# Main_DIY_board.net
KiCad netlist of a schematic drawn in EAGLE
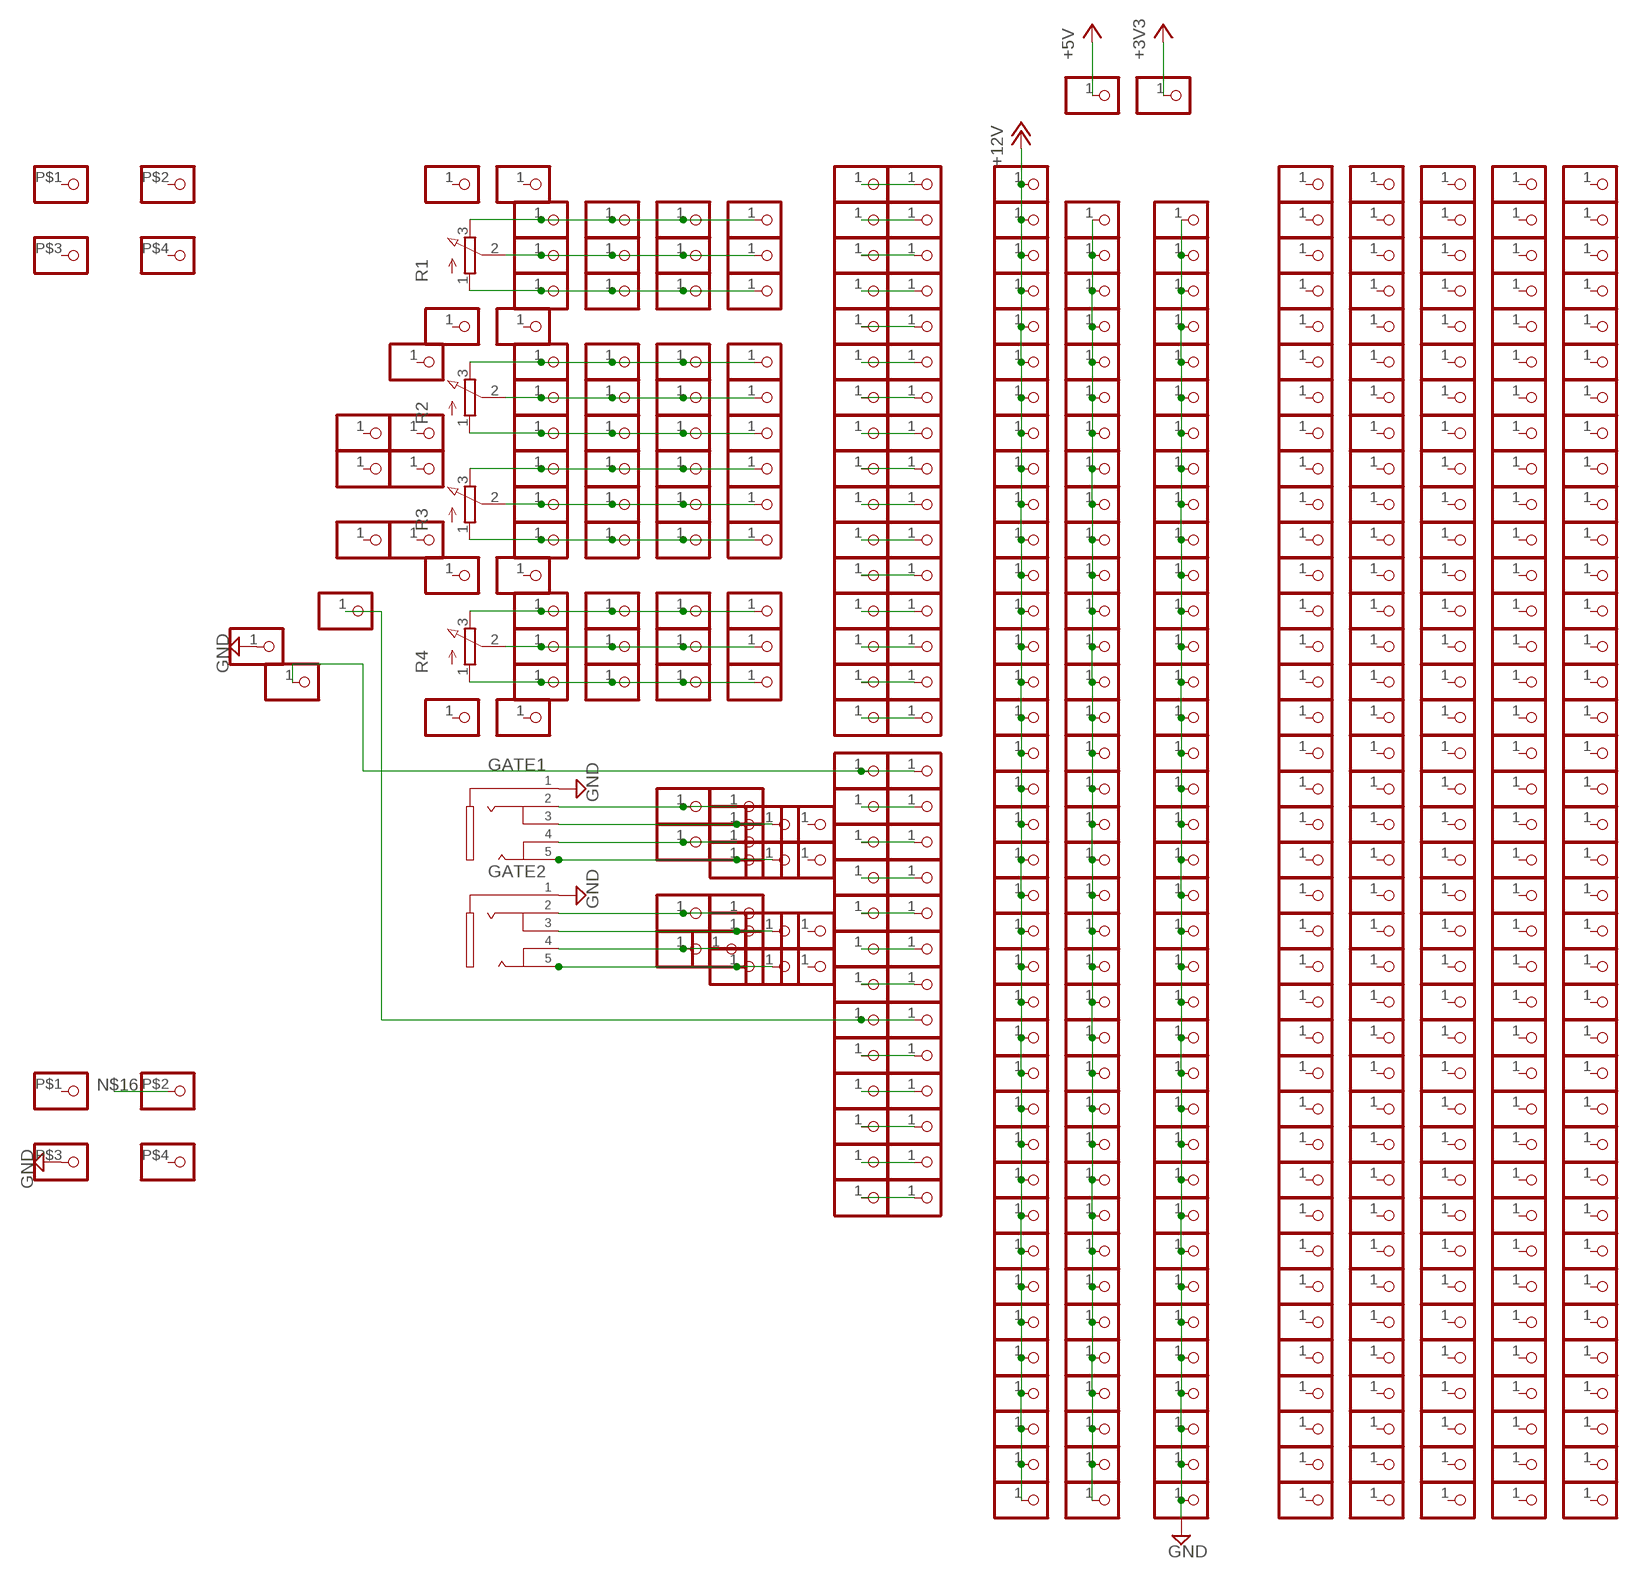
[diagram p0: schematic, sheet 1, part 1 of 2]
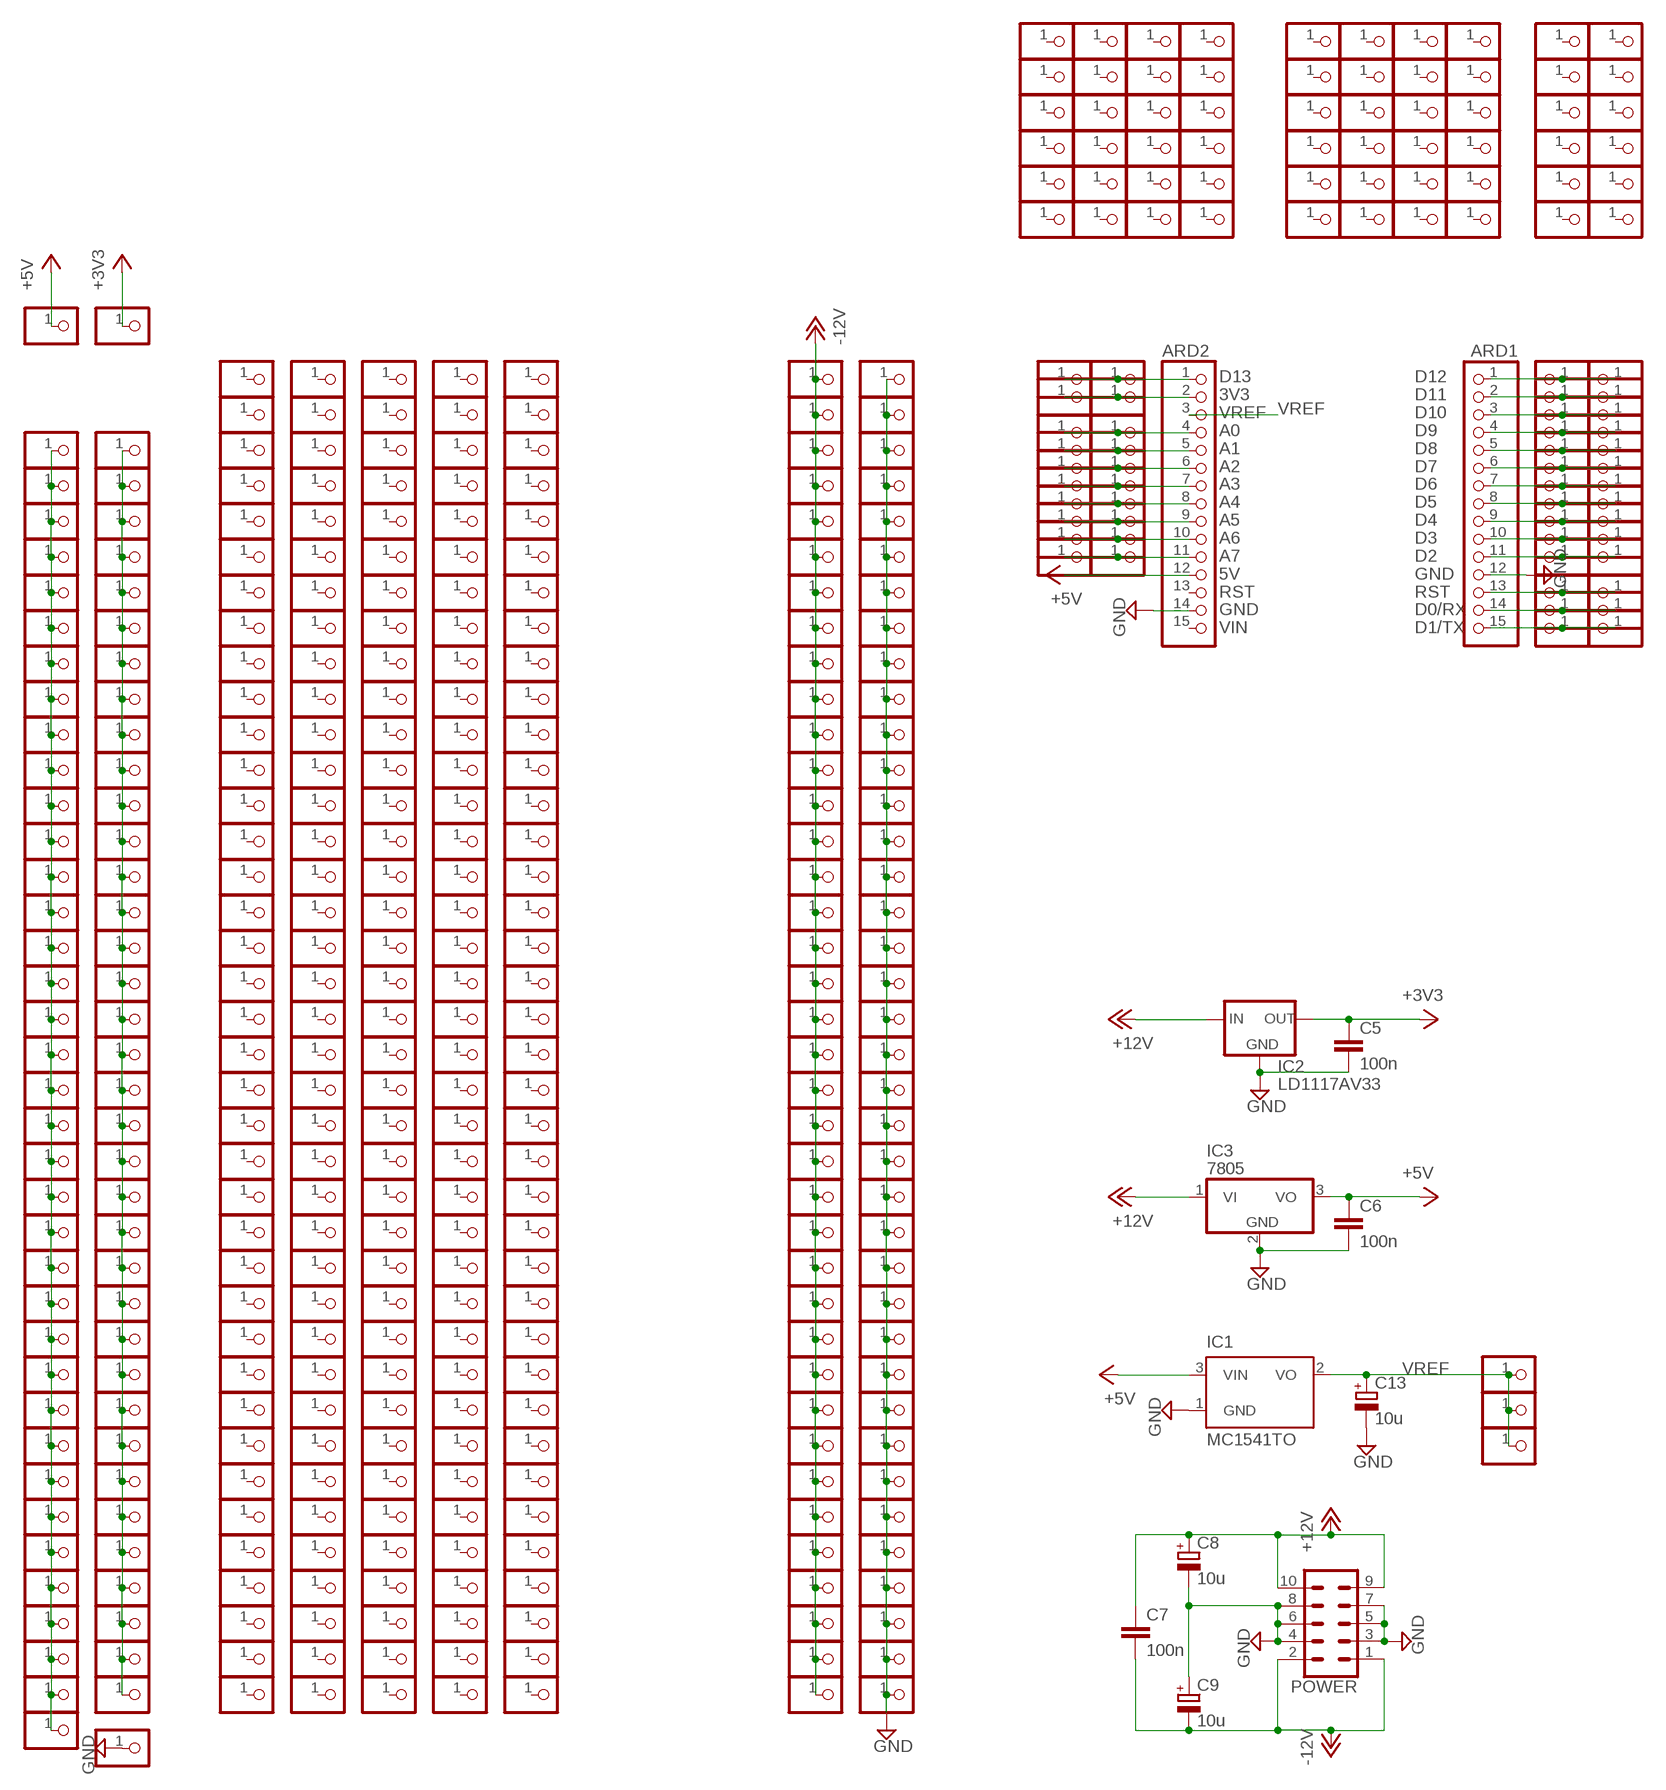
[diagram p1: schematic, sheet 1, part 2 of 2]

(export (version "E")
  (design (tool "Eeschema 10.0.6"))
  (components
    (comp (ref "ARD1")
      (value "PINHD-1X15")
      (footprint "eagle-import:1X15")
      (libsource (lib "eagle-import") (part "PINHD-1X15"))
    )
    (comp (ref "ARD2")
      (value "PINHD-1X15")
      (footprint "eagle-import:1X15")
      (libsource (lib "eagle-import") (part "PINHD-1X15"))
    )
    (comp (ref "C5")
      (value "100n")
      (footprint "eagle-import:C050-025X075")
      (libsource (lib "eagle-import") (part "C-EU050-025X075"))
    )
    (comp (ref "C6")
      (value "100n")
      (footprint "eagle-import:C050-025X075")
      (libsource (lib "eagle-import") (part "C-EU050-025X075"))
    )
    (comp (ref "C7")
      (value "100n")
      (footprint "eagle-import:C050-025X075")
      (libsource (lib "eagle-import") (part "C-EU050-025X075"))
    )
    (comp (ref "C8")
      (value "10u")
      (footprint "eagle-import:E2,5-5")
      (libsource (lib "eagle-import") (part "CPOL"))
    )
    (comp (ref "C9")
      (value "10u")
      (footprint "eagle-import:E2,5-5")
      (libsource (lib "eagle-import") (part "CPOL"))
    )
    (comp (ref "C13")
      (value "10u")
      (footprint "eagle-import:E2,5-5")
      (libsource (lib "eagle-import") (part "CPOL"))
    )
    (comp (ref "GATE1")
      (value "PJ-324MH")
      (footprint "eagle-import:PJ-324MH")
      (libsource (lib "eagle-import") (part "PJ-324MH"))
    )
    (comp (ref "GATE2")
      (value "PJ-324MH")
      (footprint "eagle-import:PJ-324MH")
      (libsource (lib "eagle-import") (part "PJ-324MH"))
    )
    (comp (ref "IC1")
      (value "MC1541TO")
      (footprint "eagle-import:TO92")
      (libsource (lib "eagle-import") (part "MC15TO41"))
    )
    (comp (ref "IC2")
      (value "LD1117AV33")
      (footprint "eagle-import:78XXL")
      (libsource (lib "eagle-import") (part "V_REG_LD1117VXX"))
    )
    (comp (ref "IC3")
      (value "7805")
      (footprint "eagle-import:TO220H")
      (libsource (lib "eagle-import") (part "78T05"))
    )
    (comp (ref "JP1")
      (value "1X01")
      (footprint "eagle-import:1X01")
      (libsource (lib "eagle-import") (part "1X01"))
    )
    (comp (ref "JP2")
      (value "1X01")
      (footprint "eagle-import:1X01")
      (libsource (lib "eagle-import") (part "1X01"))
    )
    (comp (ref "JP3")
      (value "1X01")
      (footprint "eagle-import:1X01")
      (libsource (lib "eagle-import") (part "1X01"))
    )
    (comp (ref "JP4")
      (value "1X01")
      (footprint "eagle-import:1X01")
      (libsource (lib "eagle-import") (part "1X01"))
    )
    (comp (ref "JP5")
      (value "1X01")
      (footprint "eagle-import:1X01")
      (libsource (lib "eagle-import") (part "1X01"))
    )
    (comp (ref "JP6")
      (value "1X01")
      (footprint "eagle-import:1X01")
      (libsource (lib "eagle-import") (part "1X01"))
    )
    (comp (ref "JP7")
      (value "1X01")
      (footprint "eagle-import:1X01")
      (libsource (lib "eagle-import") (part "1X01"))
    )
    (comp (ref "JP8")
      (value "1X01")
      (footprint "eagle-import:1X01")
      (libsource (lib "eagle-import") (part "1X01"))
    )
    (comp (ref "JP9")
      (value "1X01")
      (footprint "eagle-import:1X01")
      (libsource (lib "eagle-import") (part "1X01"))
    )
    (comp (ref "JP10")
      (value "1X01")
      (footprint "eagle-import:1X01")
      (libsource (lib "eagle-import") (part "1X01"))
    )
    (comp (ref "JP11")
      (value "1X01")
      (footprint "eagle-import:1X01")
      (libsource (lib "eagle-import") (part "1X01"))
    )
    (comp (ref "JP12")
      (value "1X01")
      (footprint "eagle-import:1X01")
      (libsource (lib "eagle-import") (part "1X01"))
    )
    (comp (ref "JP13")
      (value "1X01")
      (footprint "eagle-import:1X01")
      (libsource (lib "eagle-import") (part "1X01"))
    )
    (comp (ref "JP14")
      (value "1X01")
      (footprint "eagle-import:1X01")
      (libsource (lib "eagle-import") (part "1X01"))
    )
    (comp (ref "JP15")
      (value "1X01")
      (footprint "eagle-import:1X01")
      (libsource (lib "eagle-import") (part "1X01"))
    )
    (comp (ref "JP16")
      (value "1X01")
      (footprint "eagle-import:1X01")
      (libsource (lib "eagle-import") (part "1X01"))
    )
    (comp (ref "JP17")
      (value "1X01")
      (footprint "eagle-import:1X01")
      (libsource (lib "eagle-import") (part "1X01"))
    )
    (comp (ref "JP18")
      (value "1X01")
      (footprint "eagle-import:1X01")
      (libsource (lib "eagle-import") (part "1X01"))
    )
    (comp (ref "JP19")
      (value "1X01")
      (footprint "eagle-import:1X01")
      (libsource (lib "eagle-import") (part "1X01"))
    )
    (comp (ref "JP20")
      (value "1X01")
      (footprint "eagle-import:1X01")
      (libsource (lib "eagle-import") (part "1X01"))
    )
    (comp (ref "JP21")
      (value "1X01")
      (footprint "eagle-import:1X01")
      (libsource (lib "eagle-import") (part "1X01"))
    )
    (comp (ref "JP22")
      (value "1X01")
      (footprint "eagle-import:1X01")
      (libsource (lib "eagle-import") (part "1X01"))
    )
    (comp (ref "JP23")
      (value "1X01")
      (footprint "eagle-import:1X01")
      (libsource (lib "eagle-import") (part "1X01"))
    )
    (comp (ref "JP24")
      (value "1X01")
      (footprint "eagle-import:1X01")
      (libsource (lib "eagle-import") (part "1X01"))
    )
    (comp (ref "JP25")
      (value "1X01")
      (footprint "eagle-import:1X01")
      (libsource (lib "eagle-import") (part "1X01"))
    )
    (comp (ref "JP26")
      (value "1X01")
      (footprint "eagle-import:1X01")
      (libsource (lib "eagle-import") (part "1X01"))
    )
    (comp (ref "JP27")
      (value "1X01")
      (footprint "eagle-import:1X01")
      (libsource (lib "eagle-import") (part "1X01"))
    )
    (comp (ref "JP28")
      (value "1X01")
      (footprint "eagle-import:1X01")
      (libsource (lib "eagle-import") (part "1X01"))
    )
    (comp (ref "JP29")
      (value "1X01")
      (footprint "eagle-import:1X01")
      (libsource (lib "eagle-import") (part "1X01"))
    )
    (comp (ref "JP30")
      (value "1X01")
      (footprint "eagle-import:1X01")
      (libsource (lib "eagle-import") (part "1X01"))
    )
    (comp (ref "JP31")
      (value "1X01")
      (footprint "eagle-import:1X01")
      (libsource (lib "eagle-import") (part "1X01"))
    )
    (comp (ref "JP32")
      (value "1X01")
      (footprint "eagle-import:1X01")
      (libsource (lib "eagle-import") (part "1X01"))
    )
    (comp (ref "JP33")
      (value "1X01")
      (footprint "eagle-import:1X01")
      (libsource (lib "eagle-import") (part "1X01"))
    )
    (comp (ref "JP34")
      (value "1X01")
      (footprint "eagle-import:1X01")
      (libsource (lib "eagle-import") (part "1X01"))
    )
    (comp (ref "JP35")
      (value "1X01")
      (footprint "eagle-import:1X01")
      (libsource (lib "eagle-import") (part "1X01"))
    )
    (comp (ref "JP36")
      (value "1X01")
      (footprint "eagle-import:1X01")
      (libsource (lib "eagle-import") (part "1X01"))
    )
    (comp (ref "JP37")
      (value "1X01")
      (footprint "eagle-import:1X01")
      (libsource (lib "eagle-import") (part "1X01"))
    )
    (comp (ref "JP38")
      (value "1X01")
      (footprint "eagle-import:1X01")
      (libsource (lib "eagle-import") (part "1X01"))
    )
    (comp (ref "JP39")
      (value "1X01")
      (footprint "eagle-import:1X01")
      (libsource (lib "eagle-import") (part "1X01"))
    )
    (comp (ref "JP40")
      (value "1X01")
      (footprint "eagle-import:1X01")
      (libsource (lib "eagle-import") (part "1X01"))
    )
    (comp (ref "JP41")
      (value "1X01")
      (footprint "eagle-import:1X01")
      (libsource (lib "eagle-import") (part "1X01"))
    )
    (comp (ref "JP42")
      (value "1X01")
      (footprint "eagle-import:1X01")
      (libsource (lib "eagle-import") (part "1X01"))
    )
    (comp (ref "JP43")
      (value "1X01")
      (footprint "eagle-import:1X01")
      (libsource (lib "eagle-import") (part "1X01"))
    )
    (comp (ref "JP44")
      (value "1X01")
      (footprint "eagle-import:1X01")
      (libsource (lib "eagle-import") (part "1X01"))
    )
    (comp (ref "JP45")
      (value "1X01")
      (footprint "eagle-import:1X01")
      (libsource (lib "eagle-import") (part "1X01"))
    )
    (comp (ref "JP46")
      (value "1X01")
      (footprint "eagle-import:1X01")
      (libsource (lib "eagle-import") (part "1X01"))
    )
    (comp (ref "JP47")
      (value "1X01")
      (footprint "eagle-import:1X01")
      (libsource (lib "eagle-import") (part "1X01"))
    )
    (comp (ref "JP48")
      (value "1X01")
      (footprint "eagle-import:1X01")
      (libsource (lib "eagle-import") (part "1X01"))
    )
    (comp (ref "JP49")
      (value "1X01")
      (footprint "eagle-import:1X01")
      (libsource (lib "eagle-import") (part "1X01"))
    )
    (comp (ref "JP50")
      (value "1X01")
      (footprint "eagle-import:1X01")
      (libsource (lib "eagle-import") (part "1X01"))
    )
    (comp (ref "JP51")
      (value "1X01")
      (footprint "eagle-import:1X01")
      (libsource (lib "eagle-import") (part "1X01"))
    )
    (comp (ref "JP52")
      (value "1X01")
      (footprint "eagle-import:1X01")
      (libsource (lib "eagle-import") (part "1X01"))
    )
    (comp (ref "JP53")
      (value "1X01")
      (footprint "eagle-import:1X01")
      (libsource (lib "eagle-import") (part "1X01"))
    )
    (comp (ref "JP54")
      (value "1X01")
      (footprint "eagle-import:1X01")
      (libsource (lib "eagle-import") (part "1X01"))
    )
    (comp (ref "JP55")
      (value "1X01")
      (footprint "eagle-import:1X01")
      (libsource (lib "eagle-import") (part "1X01"))
    )
    (comp (ref "JP56")
      (value "1X01")
      (footprint "eagle-import:1X01")
      (libsource (lib "eagle-import") (part "1X01"))
    )
    (comp (ref "JP57")
      (value "1X01")
      (footprint "eagle-import:1X01")
      (libsource (lib "eagle-import") (part "1X01"))
    )
    (comp (ref "JP58")
      (value "1X01")
      (footprint "eagle-import:1X01")
      (libsource (lib "eagle-import") (part "1X01"))
    )
    (comp (ref "JP59")
      (value "1X01")
      (footprint "eagle-import:1X01")
      (libsource (lib "eagle-import") (part "1X01"))
    )
    (comp (ref "JP60")
      (value "1X01")
      (footprint "eagle-import:1X01")
      (libsource (lib "eagle-import") (part "1X01"))
    )
    (comp (ref "JP61")
      (value "1X01")
      (footprint "eagle-import:1X01")
      (libsource (lib "eagle-import") (part "1X01"))
    )
    (comp (ref "JP62")
      (value "1X01")
      (footprint "eagle-import:1X01")
      (libsource (lib "eagle-import") (part "1X01"))
    )
    (comp (ref "JP63")
      (value "1X01")
      (footprint "eagle-import:1X01")
      (libsource (lib "eagle-import") (part "1X01"))
    )
    (comp (ref "JP64")
      (value "1X01")
      (footprint "eagle-import:1X01")
      (libsource (lib "eagle-import") (part "1X01"))
    )
    (comp (ref "JP65")
      (value "1X01")
      (footprint "eagle-import:1X01")
      (libsource (lib "eagle-import") (part "1X01"))
    )
    (comp (ref "JP66")
      (value "1X01")
      (footprint "eagle-import:1X01")
      (libsource (lib "eagle-import") (part "1X01"))
    )
    (comp (ref "JP67")
      (value "1X01")
      (footprint "eagle-import:1X01")
      (libsource (lib "eagle-import") (part "1X01"))
    )
    (comp (ref "JP68")
      (value "1X01")
      (footprint "eagle-import:1X01")
      (libsource (lib "eagle-import") (part "1X01"))
    )
    (comp (ref "JP69")
      (value "1X01")
      (footprint "eagle-import:1X01")
      (libsource (lib "eagle-import") (part "1X01"))
    )
    (comp (ref "JP70")
      (value "1X01")
      (footprint "eagle-import:1X01")
      (libsource (lib "eagle-import") (part "1X01"))
    )
    (comp (ref "JP71")
      (value "1X01")
      (footprint "eagle-import:1X01")
      (libsource (lib "eagle-import") (part "1X01"))
    )
    (comp (ref "JP72")
      (value "1X01")
      (footprint "eagle-import:1X01")
      (libsource (lib "eagle-import") (part "1X01"))
    )
    (comp (ref "JP73")
      (value "1X01")
      (footprint "eagle-import:1X01")
      (libsource (lib "eagle-import") (part "1X01"))
    )
    (comp (ref "JP74")
      (value "1X01")
      (footprint "eagle-import:1X01")
      (libsource (lib "eagle-import") (part "1X01"))
    )
    (comp (ref "JP75")
      (value "1X01")
      (footprint "eagle-import:1X01")
      (libsource (lib "eagle-import") (part "1X01"))
    )
    (comp (ref "JP76")
      (value "1X01")
      (footprint "eagle-import:1X01")
      (libsource (lib "eagle-import") (part "1X01"))
    )
    (comp (ref "JP77")
      (value "1X01")
      (footprint "eagle-import:1X01")
      (libsource (lib "eagle-import") (part "1X01"))
    )
    (comp (ref "JP78")
      (value "1X01")
      (footprint "eagle-import:1X01")
      (libsource (lib "eagle-import") (part "1X01"))
    )
    (comp (ref "JP79")
      (value "1X01")
      (footprint "eagle-import:1X01")
      (libsource (lib "eagle-import") (part "1X01"))
    )
    (comp (ref "JP80")
      (value "1X01")
      (footprint "eagle-import:1X01")
      (libsource (lib "eagle-import") (part "1X01"))
    )
    (comp (ref "JP81")
      (value "1X01")
      (footprint "eagle-import:1X01")
      (libsource (lib "eagle-import") (part "1X01"))
    )
    (comp (ref "JP82")
      (value "1X01")
      (footprint "eagle-import:1X01")
      (libsource (lib "eagle-import") (part "1X01"))
    )
    (comp (ref "JP83")
      (value "1X01")
      (footprint "eagle-import:1X01")
      (libsource (lib "eagle-import") (part "1X01"))
    )
    (comp (ref "JP84")
      (value "1X01")
      (footprint "eagle-import:1X01")
      (libsource (lib "eagle-import") (part "1X01"))
    )
    (comp (ref "JP85")
      (value "1X01")
      (footprint "eagle-import:1X01")
      (libsource (lib "eagle-import") (part "1X01"))
    )
    (comp (ref "JP86")
      (value "1X01")
      (footprint "eagle-import:1X01")
      (libsource (lib "eagle-import") (part "1X01"))
    )
    (comp (ref "JP87")
      (value "1X01")
      (footprint "eagle-import:1X01")
      (libsource (lib "eagle-import") (part "1X01"))
    )
    (comp (ref "JP88")
      (value "1X01")
      (footprint "eagle-import:1X01")
      (libsource (lib "eagle-import") (part "1X01"))
    )
    (comp (ref "JP89")
      (value "1X01")
      (footprint "eagle-import:1X01")
      (libsource (lib "eagle-import") (part "1X01"))
    )
    (comp (ref "JP90")
      (value "1X01")
      (footprint "eagle-import:1X01")
      (libsource (lib "eagle-import") (part "1X01"))
    )
    (comp (ref "JP91")
      (value "1X01")
      (footprint "eagle-import:1X01")
      (libsource (lib "eagle-import") (part "1X01"))
    )
    (comp (ref "JP92")
      (value "1X01")
      (footprint "eagle-import:1X01")
      (libsource (lib "eagle-import") (part "1X01"))
    )
    (comp (ref "JP93")
      (value "1X01")
      (footprint "eagle-import:1X01")
      (libsource (lib "eagle-import") (part "1X01"))
    )
    (comp (ref "JP94")
      (value "1X01")
      (footprint "eagle-import:1X01")
      (libsource (lib "eagle-import") (part "1X01"))
    )
    (comp (ref "JP95")
      (value "1X01")
      (footprint "eagle-import:1X01")
      (libsource (lib "eagle-import") (part "1X01"))
    )
    (comp (ref "JP96")
      (value "1X01")
      (footprint "eagle-import:1X01")
      (libsource (lib "eagle-import") (part "1X01"))
    )
    (comp (ref "JP97")
      (value "1X01")
      (footprint "eagle-import:1X01")
      (libsource (lib "eagle-import") (part "1X01"))
    )
    (comp (ref "JP98")
      (value "1X01")
      (footprint "eagle-import:1X01")
      (libsource (lib "eagle-import") (part "1X01"))
    )
    (comp (ref "JP99")
      (value "1X01")
      (footprint "eagle-import:1X01")
      (libsource (lib "eagle-import") (part "1X01"))
    )
    (comp (ref "JP100")
      (value "1X01")
      (footprint "eagle-import:1X01")
      (libsource (lib "eagle-import") (part "1X01"))
    )
    (comp (ref "JP101")
      (value "1X01")
      (footprint "eagle-import:1X01")
      (libsource (lib "eagle-import") (part "1X01"))
    )
    (comp (ref "JP102")
      (value "1X01")
      (footprint "eagle-import:1X01")
      (libsource (lib "eagle-import") (part "1X01"))
    )
    (comp (ref "JP103")
      (value "1X01")
      (footprint "eagle-import:1X01")
      (libsource (lib "eagle-import") (part "1X01"))
    )
    (comp (ref "JP104")
      (value "1X01")
      (footprint "eagle-import:1X01")
      (libsource (lib "eagle-import") (part "1X01"))
    )
    (comp (ref "JP105")
      (value "1X01")
      (footprint "eagle-import:1X01")
      (libsource (lib "eagle-import") (part "1X01"))
    )
    (comp (ref "JP106")
      (value "1X01")
      (footprint "eagle-import:1X01")
      (libsource (lib "eagle-import") (part "1X01"))
    )
    (comp (ref "JP107")
      (value "1X01")
      (footprint "eagle-import:1X01")
      (libsource (lib "eagle-import") (part "1X01"))
    )
    (comp (ref "JP108")
      (value "1X01")
      (footprint "eagle-import:1X01")
      (libsource (lib "eagle-import") (part "1X01"))
    )
    (comp (ref "JP109")
      (value "1X01")
      (footprint "eagle-import:1X01")
      (libsource (lib "eagle-import") (part "1X01"))
    )
    (comp (ref "JP110")
      (value "1X01")
      (footprint "eagle-import:1X01")
      (libsource (lib "eagle-import") (part "1X01"))
    )
    (comp (ref "JP111")
      (value "1X01")
      (footprint "eagle-import:1X01")
      (libsource (lib "eagle-import") (part "1X01"))
    )
    (comp (ref "JP112")
      (value "1X01")
      (footprint "eagle-import:1X01")
      (libsource (lib "eagle-import") (part "1X01"))
    )
    (comp (ref "JP113")
      (value "1X01")
      (footprint "eagle-import:1X01")
      (libsource (lib "eagle-import") (part "1X01"))
    )
    (comp (ref "JP114")
      (value "1X01")
      (footprint "eagle-import:1X01")
      (libsource (lib "eagle-import") (part "1X01"))
    )
    (comp (ref "JP115")
      (value "1X01")
      (footprint "eagle-import:1X01")
      (libsource (lib "eagle-import") (part "1X01"))
    )
    (comp (ref "JP116")
      (value "1X01")
      (footprint "eagle-import:1X01")
      (libsource (lib "eagle-import") (part "1X01"))
    )
    (comp (ref "JP117")
      (value "1X01")
      (footprint "eagle-import:1X01")
      (libsource (lib "eagle-import") (part "1X01"))
    )
    (comp (ref "JP118")
      (value "1X01")
      (footprint "eagle-import:1X01")
      (libsource (lib "eagle-import") (part "1X01"))
    )
    (comp (ref "JP119")
      (value "1X01")
      (footprint "eagle-import:1X01")
      (libsource (lib "eagle-import") (part "1X01"))
    )
    (comp (ref "JP120")
      (value "1X01")
      (footprint "eagle-import:1X01")
      (libsource (lib "eagle-import") (part "1X01"))
    )
    (comp (ref "JP121")
      (value "1X01")
      (footprint "eagle-import:1X01")
      (libsource (lib "eagle-import") (part "1X01"))
    )
    (comp (ref "JP122")
      (value "1X01")
      (footprint "eagle-import:1X01")
      (libsource (lib "eagle-import") (part "1X01"))
    )
    (comp (ref "JP123")
      (value "1X01")
      (footprint "eagle-import:1X01")
      (libsource (lib "eagle-import") (part "1X01"))
    )
    (comp (ref "JP124")
      (value "1X01")
      (footprint "eagle-import:1X01")
      (libsource (lib "eagle-import") (part "1X01"))
    )
    (comp (ref "JP125")
      (value "1X01")
      (footprint "eagle-import:1X01")
      (libsource (lib "eagle-import") (part "1X01"))
    )
    (comp (ref "JP126")
      (value "1X01")
      (footprint "eagle-import:1X01")
      (libsource (lib "eagle-import") (part "1X01"))
    )
    (comp (ref "JP127")
      (value "1X01")
      (footprint "eagle-import:1X01")
      (libsource (lib "eagle-import") (part "1X01"))
    )
    (comp (ref "JP128")
      (value "1X01")
      (footprint "eagle-import:1X01")
      (libsource (lib "eagle-import") (part "1X01"))
    )
    (comp (ref "JP129")
      (value "1X01")
      (footprint "eagle-import:1X01")
      (libsource (lib "eagle-import") (part "1X01"))
    )
    (comp (ref "JP130")
      (value "1X01")
      (footprint "eagle-import:1X01")
      (libsource (lib "eagle-import") (part "1X01"))
    )
    (comp (ref "JP131")
      (value "1X01")
      (footprint "eagle-import:1X01")
      (libsource (lib "eagle-import") (part "1X01"))
    )
    (comp (ref "JP132")
      (value "1X01")
      (footprint "eagle-import:1X01")
      (libsource (lib "eagle-import") (part "1X01"))
    )
    (comp (ref "JP133")
      (value "1X01")
      (footprint "eagle-import:1X01")
      (libsource (lib "eagle-import") (part "1X01"))
    )
    (comp (ref "JP134")
      (value "1X01")
      (footprint "eagle-import:1X01")
      (libsource (lib "eagle-import") (part "1X01"))
    )
    (comp (ref "JP135")
      (value "1X01")
      (footprint "eagle-import:1X01")
      (libsource (lib "eagle-import") (part "1X01"))
    )
    (comp (ref "JP136")
      (value "1X01")
      (footprint "eagle-import:1X01")
      (libsource (lib "eagle-import") (part "1X01"))
    )
    (comp (ref "JP137")
      (value "1X01")
      (footprint "eagle-import:1X01")
      (libsource (lib "eagle-import") (part "1X01"))
    )
    (comp (ref "JP138")
      (value "1X01")
      (footprint "eagle-import:1X01")
      (libsource (lib "eagle-import") (part "1X01"))
    )
    (comp (ref "JP139")
      (value "1X01")
      (footprint "eagle-import:1X01")
      (libsource (lib "eagle-import") (part "1X01"))
    )
    (comp (ref "JP140")
      (value "1X01")
      (footprint "eagle-import:1X01")
      (libsource (lib "eagle-import") (part "1X01"))
    )
    (comp (ref "JP141")
      (value "1X01")
      (footprint "eagle-import:1X01")
      (libsource (lib "eagle-import") (part "1X01"))
    )
    (comp (ref "JP142")
      (value "1X01")
      (footprint "eagle-import:1X01")
      (libsource (lib "eagle-import") (part "1X01"))
    )
    (comp (ref "JP143")
      (value "1X01")
      (footprint "eagle-import:1X01")
      (libsource (lib "eagle-import") (part "1X01"))
    )
    (comp (ref "JP144")
      (value "1X01")
      (footprint "eagle-import:1X01")
      (libsource (lib "eagle-import") (part "1X01"))
    )
    (comp (ref "JP145")
      (value "1X01")
      (footprint "eagle-import:1X01")
      (libsource (lib "eagle-import") (part "1X01"))
    )
    (comp (ref "JP146")
      (value "1X01")
      (footprint "eagle-import:1X01")
      (libsource (lib "eagle-import") (part "1X01"))
    )
    (comp (ref "JP147")
      (value "1X01")
      (footprint "eagle-import:1X01")
      (libsource (lib "eagle-import") (part "1X01"))
    )
    (comp (ref "JP148")
      (value "1X01")
      (footprint "eagle-import:1X01")
      (libsource (lib "eagle-import") (part "1X01"))
    )
    (comp (ref "JP149")
      (value "1X01")
      (footprint "eagle-import:1X01")
      (libsource (lib "eagle-import") (part "1X01"))
    )
    (comp (ref "JP150")
      (value "1X01")
      (footprint "eagle-import:1X01")
      (libsource (lib "eagle-import") (part "1X01"))
    )
    (comp (ref "JP151")
      (value "1X01")
      (footprint "eagle-import:1X01")
      (libsource (lib "eagle-import") (part "1X01"))
    )
    (comp (ref "JP152")
      (value "1X01")
      (footprint "eagle-import:1X01")
      (libsource (lib "eagle-import") (part "1X01"))
    )
    (comp (ref "JP153")
      (value "1X01")
      (footprint "eagle-import:1X01")
      (libsource (lib "eagle-import") (part "1X01"))
    )
    (comp (ref "JP154")
      (value "1X01")
      (footprint "eagle-import:1X01")
      (libsource (lib "eagle-import") (part "1X01"))
    )
    (comp (ref "JP155")
      (value "1X01")
      (footprint "eagle-import:1X01")
      (libsource (lib "eagle-import") (part "1X01"))
    )
    (comp (ref "JP156")
      (value "1X01")
      (footprint "eagle-import:1X01")
      (libsource (lib "eagle-import") (part "1X01"))
    )
    (comp (ref "JP157")
      (value "1X01")
      (footprint "eagle-import:1X01")
      (libsource (lib "eagle-import") (part "1X01"))
    )
    (comp (ref "JP158")
      (value "1X01")
      (footprint "eagle-import:1X01")
      (libsource (lib "eagle-import") (part "1X01"))
    )
    (comp (ref "JP159")
      (value "1X01")
      (footprint "eagle-import:1X01")
      (libsource (lib "eagle-import") (part "1X01"))
    )
    (comp (ref "JP160")
      (value "1X01")
      (footprint "eagle-import:1X01")
      (libsource (lib "eagle-import") (part "1X01"))
    )
    (comp (ref "JP161")
      (value "1X01")
      (footprint "eagle-import:1X01")
      (libsource (lib "eagle-import") (part "1X01"))
    )
    (comp (ref "JP162")
      (value "1X01")
      (footprint "eagle-import:1X01")
      (libsource (lib "eagle-import") (part "1X01"))
    )
    (comp (ref "JP163")
      (value "1X01")
      (footprint "eagle-import:1X01")
      (libsource (lib "eagle-import") (part "1X01"))
    )
    (comp (ref "JP164")
      (value "1X01")
      (footprint "eagle-import:1X01")
      (libsource (lib "eagle-import") (part "1X01"))
    )
    (comp (ref "JP165")
      (value "1X01")
      (footprint "eagle-import:1X01")
      (libsource (lib "eagle-import") (part "1X01"))
    )
    (comp (ref "JP166")
      (value "1X01")
      (footprint "eagle-import:1X01")
      (libsource (lib "eagle-import") (part "1X01"))
    )
    (comp (ref "JP167")
      (value "1X01")
      (footprint "eagle-import:1X01")
      (libsource (lib "eagle-import") (part "1X01"))
    )
    (comp (ref "JP168")
      (value "1X01")
      (footprint "eagle-import:1X01")
      (libsource (lib "eagle-import") (part "1X01"))
    )
    (comp (ref "JP169")
      (value "1X01")
      (footprint "eagle-import:1X01")
      (libsource (lib "eagle-import") (part "1X01"))
    )
    (comp (ref "JP170")
      (value "1X01")
      (footprint "eagle-import:1X01")
      (libsource (lib "eagle-import") (part "1X01"))
    )
    (comp (ref "JP171")
      (value "1X01")
      (footprint "eagle-import:1X01")
      (libsource (lib "eagle-import") (part "1X01"))
    )
    (comp (ref "JP172")
      (value "1X01")
      (footprint "eagle-import:1X01")
      (libsource (lib "eagle-import") (part "1X01"))
    )
    (comp (ref "JP173")
      (value "1X01")
      (footprint "eagle-import:1X01")
      (libsource (lib "eagle-import") (part "1X01"))
    )
    (comp (ref "JP174")
      (value "1X01")
      (footprint "eagle-import:1X01")
      (libsource (lib "eagle-import") (part "1X01"))
    )
    (comp (ref "JP175")
      (value "1X01")
      (footprint "eagle-import:1X01")
      (libsource (lib "eagle-import") (part "1X01"))
    )
    (comp (ref "JP176")
      (value "1X01")
      (footprint "eagle-import:1X01")
      (libsource (lib "eagle-import") (part "1X01"))
    )
    (comp (ref "JP177")
      (value "1X01")
      (footprint "eagle-import:1X01")
      (libsource (lib "eagle-import") (part "1X01"))
    )
    (comp (ref "JP178")
      (value "1X01")
      (footprint "eagle-import:1X01")
      (libsource (lib "eagle-import") (part "1X01"))
    )
    (comp (ref "JP179")
      (value "1X01")
      (footprint "eagle-import:1X01")
      (libsource (lib "eagle-import") (part "1X01"))
    )
    (comp (ref "JP180")
      (value "1X01")
      (footprint "eagle-import:1X01")
      (libsource (lib "eagle-import") (part "1X01"))
    )
    (comp (ref "JP181")
      (value "1X01")
      (footprint "eagle-import:1X01")
      (libsource (lib "eagle-import") (part "1X01"))
    )
    (comp (ref "JP182")
      (value "1X01")
      (footprint "eagle-import:1X01")
      (libsource (lib "eagle-import") (part "1X01"))
    )
    (comp (ref "JP183")
      (value "1X01")
      (footprint "eagle-import:1X01")
      (libsource (lib "eagle-import") (part "1X01"))
    )
    (comp (ref "JP184")
      (value "1X01")
      (footprint "eagle-import:1X01")
      (libsource (lib "eagle-import") (part "1X01"))
    )
    (comp (ref "JP185")
      (value "1X01")
      (footprint "eagle-import:1X01")
      (libsource (lib "eagle-import") (part "1X01"))
    )
    (comp (ref "JP186")
      (value "1X01")
      (footprint "eagle-import:1X01")
      (libsource (lib "eagle-import") (part "1X01"))
    )
    (comp (ref "JP187")
      (value "1X01")
      (footprint "eagle-import:1X01")
      (libsource (lib "eagle-import") (part "1X01"))
    )
    (comp (ref "JP188")
      (value "1X01")
      (footprint "eagle-import:1X01")
      (libsource (lib "eagle-import") (part "1X01"))
    )
    (comp (ref "JP189")
      (value "1X01")
      (footprint "eagle-import:1X01")
      (libsource (lib "eagle-import") (part "1X01"))
    )
    (comp (ref "JP190")
      (value "1X01")
      (footprint "eagle-import:1X01")
      (libsource (lib "eagle-import") (part "1X01"))
    )
    (comp (ref "JP191")
      (value "1X01")
      (footprint "eagle-import:1X01")
      (libsource (lib "eagle-import") (part "1X01"))
    )
    (comp (ref "JP192")
      (value "1X01")
      (footprint "eagle-import:1X01")
      (libsource (lib "eagle-import") (part "1X01"))
    )
    (comp (ref "JP193")
      (value "1X01")
      (footprint "eagle-import:1X01")
      (libsource (lib "eagle-import") (part "1X01"))
    )
    (comp (ref "JP194")
      (value "1X01")
      (footprint "eagle-import:1X01")
      (libsource (lib "eagle-import") (part "1X01"))
    )
    (comp (ref "JP195")
      (value "1X01")
      (footprint "eagle-import:1X01")
      (libsource (lib "eagle-import") (part "1X01"))
    )
    (comp (ref "JP196")
      (value "1X01")
      (footprint "eagle-import:1X01")
      (libsource (lib "eagle-import") (part "1X01"))
    )
    (comp (ref "JP197")
      (value "1X01")
      (footprint "eagle-import:1X01")
      (libsource (lib "eagle-import") (part "1X01"))
    )
    (comp (ref "JP198")
      (value "1X01")
      (footprint "eagle-import:1X01")
      (libsource (lib "eagle-import") (part "1X01"))
    )
    (comp (ref "JP199")
      (value "1X01")
      (footprint "eagle-import:1X01")
      (libsource (lib "eagle-import") (part "1X01"))
    )
    (comp (ref "JP200")
      (value "1X01")
      (footprint "eagle-import:1X01")
      (libsource (lib "eagle-import") (part "1X01"))
    )
    (comp (ref "JP201")
      (value "1X01")
      (footprint "eagle-import:1X01")
      (libsource (lib "eagle-import") (part "1X01"))
    )
    (comp (ref "JP202")
      (value "1X01")
      (footprint "eagle-import:1X01")
      (libsource (lib "eagle-import") (part "1X01"))
    )
    (comp (ref "JP203")
      (value "1X01")
      (footprint "eagle-import:1X01")
      (libsource (lib "eagle-import") (part "1X01"))
    )
    (comp (ref "JP204")
      (value "1X01")
      (footprint "eagle-import:1X01")
      (libsource (lib "eagle-import") (part "1X01"))
    )
    (comp (ref "JP205")
      (value "1X01")
      (footprint "eagle-import:1X01")
      (libsource (lib "eagle-import") (part "1X01"))
    )
    (comp (ref "JP206")
      (value "1X01")
      (footprint "eagle-import:1X01")
      (libsource (lib "eagle-import") (part "1X01"))
    )
    (comp (ref "JP207")
      (value "1X01")
      (footprint "eagle-import:1X01")
      (libsource (lib "eagle-import") (part "1X01"))
    )
    (comp (ref "JP208")
      (value "1X01")
      (footprint "eagle-import:1X01")
      (libsource (lib "eagle-import") (part "1X01"))
    )
    (comp (ref "JP209")
      (value "1X01")
      (footprint "eagle-import:1X01")
      (libsource (lib "eagle-import") (part "1X01"))
    )
    (comp (ref "JP210")
      (value "1X01")
      (footprint "eagle-import:1X01")
      (libsource (lib "eagle-import") (part "1X01"))
    )
    (comp (ref "JP211")
      (value "1X01")
      (footprint "eagle-import:1X01")
      (libsource (lib "eagle-import") (part "1X01"))
    )
    (comp (ref "JP212")
      (value "1X01")
      (footprint "eagle-import:1X01")
      (libsource (lib "eagle-import") (part "1X01"))
    )
    (comp (ref "JP213")
      (value "1X01")
      (footprint "eagle-import:1X01")
      (libsource (lib "eagle-import") (part "1X01"))
    )
    (comp (ref "JP214")
      (value "1X01")
      (footprint "eagle-import:1X01")
      (libsource (lib "eagle-import") (part "1X01"))
    )
    (comp (ref "JP215")
      (value "1X01")
      (footprint "eagle-import:1X01")
      (libsource (lib "eagle-import") (part "1X01"))
    )
    (comp (ref "JP216")
      (value "1X01")
      (footprint "eagle-import:1X01")
      (libsource (lib "eagle-import") (part "1X01"))
    )
    (comp (ref "JP217")
      (value "1X01")
      (footprint "eagle-import:1X01")
      (libsource (lib "eagle-import") (part "1X01"))
    )
    (comp (ref "JP218")
      (value "1X01")
      (footprint "eagle-import:1X01")
      (libsource (lib "eagle-import") (part "1X01"))
    )
    (comp (ref "JP219")
      (value "1X01")
      (footprint "eagle-import:1X01")
      (libsource (lib "eagle-import") (part "1X01"))
    )
    (comp (ref "JP220")
      (value "1X01")
      (footprint "eagle-import:1X01")
      (libsource (lib "eagle-import") (part "1X01"))
    )
    (comp (ref "JP221")
      (value "1X01")
      (footprint "eagle-import:1X01")
      (libsource (lib "eagle-import") (part "1X01"))
    )
    (comp (ref "JP222")
      (value "1X01")
      (footprint "eagle-import:1X01")
      (libsource (lib "eagle-import") (part "1X01"))
    )
    (comp (ref "JP223")
      (value "1X01")
      (footprint "eagle-import:1X01")
      (libsource (lib "eagle-import") (part "1X01"))
    )
    (comp (ref "JP224")
      (value "1X01")
      (footprint "eagle-import:1X01")
      (libsource (lib "eagle-import") (part "1X01"))
    )
    (comp (ref "JP225")
      (value "1X01")
      (footprint "eagle-import:1X01")
      (libsource (lib "eagle-import") (part "1X01"))
    )
    (comp (ref "JP226")
      (value "1X01")
      (footprint "eagle-import:1X01")
      (libsource (lib "eagle-import") (part "1X01"))
    )
    (comp (ref "JP227")
      (value "1X01")
      (footprint "eagle-import:1X01")
      (libsource (lib "eagle-import") (part "1X01"))
    )
    (comp (ref "JP228")
      (value "1X01")
      (footprint "eagle-import:1X01")
      (libsource (lib "eagle-import") (part "1X01"))
    )
    (comp (ref "JP229")
      (value "1X01")
      (footprint "eagle-import:1X01")
      (libsource (lib "eagle-import") (part "1X01"))
    )
    (comp (ref "JP230")
      (value "1X01")
      (footprint "eagle-import:1X01")
      (libsource (lib "eagle-import") (part "1X01"))
    )
    (comp (ref "JP231")
      (value "1X01")
      (footprint "eagle-import:1X01")
      (libsource (lib "eagle-import") (part "1X01"))
    )
    (comp (ref "JP232")
      (value "1X01")
      (footprint "eagle-import:1X01")
      (libsource (lib "eagle-import") (part "1X01"))
    )
    (comp (ref "JP233")
      (value "1X01")
      (footprint "eagle-import:1X01")
      (libsource (lib "eagle-import") (part "1X01"))
    )
    (comp (ref "JP234")
      (value "1X01")
      (footprint "eagle-import:1X01")
      (libsource (lib "eagle-import") (part "1X01"))
    )
    (comp (ref "JP235")
      (value "1X01")
      (footprint "eagle-import:1X01")
      (libsource (lib "eagle-import") (part "1X01"))
    )
    (comp (ref "JP236")
      (value "1X01")
      (footprint "eagle-import:1X01")
      (libsource (lib "eagle-import") (part "1X01"))
    )
    (comp (ref "JP237")
      (value "1X01")
      (footprint "eagle-import:1X01")
      (libsource (lib "eagle-import") (part "1X01"))
    )
    (comp (ref "JP238")
      (value "1X01")
      (footprint "eagle-import:1X01")
      (libsource (lib "eagle-import") (part "1X01"))
    )
    (comp (ref "JP239")
      (value "1X01")
      (footprint "eagle-import:1X01")
      (libsource (lib "eagle-import") (part "1X01"))
    )
    (comp (ref "JP240")
      (value "1X01")
      (footprint "eagle-import:1X01")
      (libsource (lib "eagle-import") (part "1X01"))
    )
    (comp (ref "JP241")
      (value "1X01")
      (footprint "eagle-import:1X01")
      (libsource (lib "eagle-import") (part "1X01"))
    )
    (comp (ref "JP242")
      (value "1X01")
      (footprint "eagle-import:1X01")
      (libsource (lib "eagle-import") (part "1X01"))
    )
    (comp (ref "JP243")
      (value "1X01")
      (footprint "eagle-import:1X01")
      (libsource (lib "eagle-import") (part "1X01"))
    )
    (comp (ref "JP244")
      (value "1X01")
      (footprint "eagle-import:1X01")
      (libsource (lib "eagle-import") (part "1X01"))
    )
    (comp (ref "JP245")
      (value "1X01")
      (footprint "eagle-import:1X01")
      (libsource (lib "eagle-import") (part "1X01"))
    )
    (comp (ref "JP246")
      (value "1X01")
      (footprint "eagle-import:1X01")
      (libsource (lib "eagle-import") (part "1X01"))
    )
    (comp (ref "JP247")
      (value "1X01")
      (footprint "eagle-import:1X01")
      (libsource (lib "eagle-import") (part "1X01"))
    )
    (comp (ref "JP248")
      (value "1X01")
      (footprint "eagle-import:1X01")
      (libsource (lib "eagle-import") (part "1X01"))
    )
    (comp (ref "JP249")
      (value "1X01")
      (footprint "eagle-import:1X01")
      (libsource (lib "eagle-import") (part "1X01"))
    )
    (comp (ref "JP250")
      (value "1X01")
      (footprint "eagle-import:1X01")
      (libsource (lib "eagle-import") (part "1X01"))
    )
    (comp (ref "JP251")
      (value "1X01")
      (footprint "eagle-import:1X01")
      (libsource (lib "eagle-import") (part "1X01"))
    )
    (comp (ref "JP252")
      (value "1X01")
      (footprint "eagle-import:1X01")
      (libsource (lib "eagle-import") (part "1X01"))
    )
    (comp (ref "JP253")
      (value "1X01")
      (footprint "eagle-import:1X01")
      (libsource (lib "eagle-import") (part "1X01"))
    )
    (comp (ref "JP254")
      (value "1X01")
      (footprint "eagle-import:1X01")
      (libsource (lib "eagle-import") (part "1X01"))
    )
    (comp (ref "JP255")
      (value "1X01")
      (footprint "eagle-import:1X01")
      (libsource (lib "eagle-import") (part "1X01"))
    )
    (comp (ref "JP256")
      (value "1X01")
      (footprint "eagle-import:1X01")
      (libsource (lib "eagle-import") (part "1X01"))
    )
    (comp (ref "JP257")
      (value "1X01")
      (footprint "eagle-import:1X01")
      (libsource (lib "eagle-import") (part "1X01"))
    )
    (comp (ref "JP258")
      (value "1X01")
      (footprint "eagle-import:1X01")
      (libsource (lib "eagle-import") (part "1X01"))
    )
    (comp (ref "JP259")
      (value "1X01")
      (footprint "eagle-import:1X01")
      (libsource (lib "eagle-import") (part "1X01"))
    )
    (comp (ref "JP260")
      (value "1X01")
      (footprint "eagle-import:1X01")
      (libsource (lib "eagle-import") (part "1X01"))
    )
    (comp (ref "JP261")
      (value "1X01")
      (footprint "eagle-import:1X01")
      (libsource (lib "eagle-import") (part "1X01"))
    )
    (comp (ref "JP262")
      (value "1X01")
      (footprint "eagle-import:1X01")
      (libsource (lib "eagle-import") (part "1X01"))
    )
    (comp (ref "JP263")
      (value "1X01")
      (footprint "eagle-import:1X01")
      (libsource (lib "eagle-import") (part "1X01"))
    )
    (comp (ref "JP264")
      (value "1X01")
      (footprint "eagle-import:1X01")
      (libsource (lib "eagle-import") (part "1X01"))
    )
    (comp (ref "JP265")
      (value "1X01")
      (footprint "eagle-import:1X01")
      (libsource (lib "eagle-import") (part "1X01"))
    )
    (comp (ref "JP266")
      (value "1X01")
      (footprint "eagle-import:1X01")
      (libsource (lib "eagle-import") (part "1X01"))
    )
    (comp (ref "JP267")
      (value "1X01")
      (footprint "eagle-import:1X01")
      (libsource (lib "eagle-import") (part "1X01"))
    )
    (comp (ref "JP268")
      (value "1X01")
      (footprint "eagle-import:1X01")
      (libsource (lib "eagle-import") (part "1X01"))
    )
    (comp (ref "JP269")
      (value "1X01")
      (footprint "eagle-import:1X01")
      (libsource (lib "eagle-import") (part "1X01"))
    )
    (comp (ref "JP270")
      (value "1X01")
      (footprint "eagle-import:1X01")
      (libsource (lib "eagle-import") (part "1X01"))
    )
    (comp (ref "JP271")
      (value "1X01")
      (footprint "eagle-import:1X01")
      (libsource (lib "eagle-import") (part "1X01"))
    )
    (comp (ref "JP272")
      (value "1X01")
      (footprint "eagle-import:1X01")
      (libsource (lib "eagle-import") (part "1X01"))
    )
    (comp (ref "JP273")
      (value "1X01")
      (footprint "eagle-import:1X01")
      (libsource (lib "eagle-import") (part "1X01"))
    )
    (comp (ref "JP274")
      (value "1X01")
      (footprint "eagle-import:1X01")
      (libsource (lib "eagle-import") (part "1X01"))
    )
    (comp (ref "JP275")
      (value "1X01")
      (footprint "eagle-import:1X01")
      (libsource (lib "eagle-import") (part "1X01"))
    )
    (comp (ref "JP276")
      (value "1X01")
      (footprint "eagle-import:1X01")
      (libsource (lib "eagle-import") (part "1X01"))
    )
    (comp (ref "JP277")
      (value "1X01")
      (footprint "eagle-import:1X01")
      (libsource (lib "eagle-import") (part "1X01"))
    )
    (comp (ref "JP278")
      (value "1X01")
      (footprint "eagle-import:1X01")
      (libsource (lib "eagle-import") (part "1X01"))
    )
    (comp (ref "JP279")
      (value "1X01")
      (footprint "eagle-import:1X01")
      (libsource (lib "eagle-import") (part "1X01"))
    )
    (comp (ref "JP280")
      (value "1X01")
      (footprint "eagle-import:1X01")
      (libsource (lib "eagle-import") (part "1X01"))
    )
    (comp (ref "JP281")
      (value "1X01")
      (footprint "eagle-import:1X01")
      (libsource (lib "eagle-import") (part "1X01"))
    )
    (comp (ref "JP282")
      (value "1X01")
      (footprint "eagle-import:1X01")
      (libsource (lib "eagle-import") (part "1X01"))
    )
    (comp (ref "JP283")
      (value "1X01")
      (footprint "eagle-import:1X01")
      (libsource (lib "eagle-import") (part "1X01"))
    )
    (comp (ref "JP284")
      (value "1X01")
      (footprint "eagle-import:1X01")
      (libsource (lib "eagle-import") (part "1X01"))
    )
    (comp (ref "JP285")
      (value "1X01")
      (footprint "eagle-import:1X01")
      (libsource (lib "eagle-import") (part "1X01"))
    )
    (comp (ref "JP286")
      (value "1X01")
      (footprint "eagle-import:1X01")
      (libsource (lib "eagle-import") (part "1X01"))
    )
    (comp (ref "JP287")
      (value "1X01")
      (footprint "eagle-import:1X01")
      (libsource (lib "eagle-import") (part "1X01"))
    )
    (comp (ref "JP288")
      (value "1X01")
      (footprint "eagle-import:1X01")
      (libsource (lib "eagle-import") (part "1X01"))
    )
    (comp (ref "JP289")
      (value "1X01")
      (footprint "eagle-import:1X01")
      (libsource (lib "eagle-import") (part "1X01"))
    )
    (comp (ref "JP290")
      (value "1X01")
      (footprint "eagle-import:1X01")
      (libsource (lib "eagle-import") (part "1X01"))
    )
    (comp (ref "JP291")
      (value "1X01")
      (footprint "eagle-import:1X01")
      (libsource (lib "eagle-import") (part "1X01"))
    )
    (comp (ref "JP292")
      (value "1X01")
      (footprint "eagle-import:1X01")
      (libsource (lib "eagle-import") (part "1X01"))
    )
    (comp (ref "JP293")
      (value "1X01")
      (footprint "eagle-import:1X01")
      (libsource (lib "eagle-import") (part "1X01"))
    )
    (comp (ref "JP294")
      (value "1X01")
      (footprint "eagle-import:1X01")
      (libsource (lib "eagle-import") (part "1X01"))
    )
    (comp (ref "JP295")
      (value "1X01")
      (footprint "eagle-import:1X01")
      (libsource (lib "eagle-import") (part "1X01"))
    )
    (comp (ref "JP296")
      (value "1X01")
      (footprint "eagle-import:1X01")
      (libsource (lib "eagle-import") (part "1X01"))
    )
    (comp (ref "JP297")
      (value "1X01")
      (footprint "eagle-import:1X01")
      (libsource (lib "eagle-import") (part "1X01"))
    )
    (comp (ref "JP298")
      (value "1X01")
      (footprint "eagle-import:1X01")
      (libsource (lib "eagle-import") (part "1X01"))
    )
    (comp (ref "JP299")
      (value "1X01")
      (footprint "eagle-import:1X01")
      (libsource (lib "eagle-import") (part "1X01"))
    )
    (comp (ref "JP300")
      (value "1X01")
      (footprint "eagle-import:1X01")
      (libsource (lib "eagle-import") (part "1X01"))
    )
    (comp (ref "JP301")
      (value "1X01")
      (footprint "eagle-import:1X01")
      (libsource (lib "eagle-import") (part "1X01"))
    )
    (comp (ref "JP302")
      (value "1X01")
      (footprint "eagle-import:1X01")
      (libsource (lib "eagle-import") (part "1X01"))
    )
    (comp (ref "JP303")
      (value "1X01")
      (footprint "eagle-import:1X01")
      (libsource (lib "eagle-import") (part "1X01"))
    )
    (comp (ref "JP304")
      (value "1X01")
      (footprint "eagle-import:1X01")
      (libsource (lib "eagle-import") (part "1X01"))
    )
    (comp (ref "JP305")
      (value "1X01")
      (footprint "eagle-import:1X01")
      (libsource (lib "eagle-import") (part "1X01"))
    )
    (comp (ref "JP306")
      (value "1X01")
      (footprint "eagle-import:1X01")
      (libsource (lib "eagle-import") (part "1X01"))
    )
    (comp (ref "JP307")
      (value "1X01")
      (footprint "eagle-import:1X01")
      (libsource (lib "eagle-import") (part "1X01"))
    )
    (comp (ref "JP308")
      (value "1X01")
      (footprint "eagle-import:1X01")
      (libsource (lib "eagle-import") (part "1X01"))
    )
    (comp (ref "JP309")
      (value "1X01")
      (footprint "eagle-import:1X01")
      (libsource (lib "eagle-import") (part "1X01"))
    )
    (comp (ref "JP310")
      (value "1X01")
      (footprint "eagle-import:1X01")
      (libsource (lib "eagle-import") (part "1X01"))
    )
    (comp (ref "JP311")
      (value "1X01")
      (footprint "eagle-import:1X01")
      (libsource (lib "eagle-import") (part "1X01"))
    )
    (comp (ref "JP312")
      (value "1X01")
      (footprint "eagle-import:1X01")
      (libsource (lib "eagle-import") (part "1X01"))
    )
    (comp (ref "JP313")
      (value "1X01")
      (footprint "eagle-import:1X01")
      (libsource (lib "eagle-import") (part "1X01"))
    )
    (comp (ref "JP314")
      (value "1X01")
      (footprint "eagle-import:1X01")
      (libsource (lib "eagle-import") (part "1X01"))
    )
    (comp (ref "JP315")
      (value "1X01")
      (footprint "eagle-import:1X01")
      (libsource (lib "eagle-import") (part "1X01"))
    )
    (comp (ref "JP316")
      (value "1X01")
      (footprint "eagle-import:1X01")
      (libsource (lib "eagle-import") (part "1X01"))
    )
    (comp (ref "JP317")
      (value "1X01")
      (footprint "eagle-import:1X01")
      (libsource (lib "eagle-import") (part "1X01"))
    )
    (comp (ref "JP318")
      (value "1X01")
      (footprint "eagle-import:1X01")
      (libsource (lib "eagle-import") (part "1X01"))
    )
    (comp (ref "JP319")
      (value "1X01")
      (footprint "eagle-import:1X01")
      (libsource (lib "eagle-import") (part "1X01"))
    )
    (comp (ref "JP320")
      (value "1X01")
      (footprint "eagle-import:1X01")
      (libsource (lib "eagle-import") (part "1X01"))
    )
    (comp (ref "JP321")
      (value "1X01")
      (footprint "eagle-import:1X01")
      (libsource (lib "eagle-import") (part "1X01"))
    )
    (comp (ref "JP322")
      (value "1X01")
      (footprint "eagle-import:1X01")
      (libsource (lib "eagle-import") (part "1X01"))
    )
    (comp (ref "JP323")
      (value "1X01")
      (footprint "eagle-import:1X01")
      (libsource (lib "eagle-import") (part "1X01"))
    )
    (comp (ref "JP324")
      (value "1X01")
      (footprint "eagle-import:1X01")
      (libsource (lib "eagle-import") (part "1X01"))
    )
    (comp (ref "JP325")
      (value "1X01")
      (footprint "eagle-import:1X01")
      (libsource (lib "eagle-import") (part "1X01"))
    )
    (comp (ref "JP326")
      (value "1X01")
      (footprint "eagle-import:1X01")
      (libsource (lib "eagle-import") (part "1X01"))
    )
    (comp (ref "JP327")
      (value "1X01")
      (footprint "eagle-import:1X01")
      (libsource (lib "eagle-import") (part "1X01"))
    )
    (comp (ref "JP328")
      (value "1X01")
      (footprint "eagle-import:1X01")
      (libsource (lib "eagle-import") (part "1X01"))
    )
    (comp (ref "JP329")
      (value "1X01")
      (footprint "eagle-import:1X01")
      (libsource (lib "eagle-import") (part "1X01"))
    )
    (comp (ref "JP330")
      (value "1X01")
      (footprint "eagle-import:1X01")
      (libsource (lib "eagle-import") (part "1X01"))
    )
    (comp (ref "JP331")
      (value "1X01")
      (footprint "eagle-import:1X01")
      (libsource (lib "eagle-import") (part "1X01"))
    )
    (comp (ref "JP332")
      (value "1X01")
      (footprint "eagle-import:1X01")
      (libsource (lib "eagle-import") (part "1X01"))
    )
    (comp (ref "JP333")
      (value "1X01")
      (footprint "eagle-import:1X01")
      (libsource (lib "eagle-import") (part "1X01"))
    )
    (comp (ref "JP334")
      (value "1X01")
      (footprint "eagle-import:1X01")
      (libsource (lib "eagle-import") (part "1X01"))
    )
    (comp (ref "JP335")
      (value "1X01")
      (footprint "eagle-import:1X01")
      (libsource (lib "eagle-import") (part "1X01"))
    )
    (comp (ref "JP336")
      (value "1X01")
      (footprint "eagle-import:1X01")
      (libsource (lib "eagle-import") (part "1X01"))
    )
    (comp (ref "JP337")
      (value "1X01")
      (footprint "eagle-import:1X01")
      (libsource (lib "eagle-import") (part "1X01"))
    )
    (comp (ref "JP338")
      (value "1X01")
      (footprint "eagle-import:1X01")
      (libsource (lib "eagle-import") (part "1X01"))
    )
    (comp (ref "JP339")
      (value "1X01")
      (footprint "eagle-import:1X01")
      (libsource (lib "eagle-import") (part "1X01"))
    )
    (comp (ref "JP340")
      (value "1X01")
      (footprint "eagle-import:1X01")
      (libsource (lib "eagle-import") (part "1X01"))
    )
    (comp (ref "JP341")
      (value "1X01")
      (footprint "eagle-import:1X01")
      (libsource (lib "eagle-import") (part "1X01"))
    )
    (comp (ref "JP342")
      (value "1X01")
      (footprint "eagle-import:1X01")
      (libsource (lib "eagle-import") (part "1X01"))
    )
    (comp (ref "JP343")
      (value "1X01")
      (footprint "eagle-import:1X01")
      (libsource (lib "eagle-import") (part "1X01"))
    )
    (comp (ref "JP344")
      (value "1X01")
      (footprint "eagle-import:1X01")
      (libsource (lib "eagle-import") (part "1X01"))
    )
    (comp (ref "JP345")
      (value "1X01")
      (footprint "eagle-import:1X01")
      (libsource (lib "eagle-import") (part "1X01"))
    )
    (comp (ref "JP346")
      (value "1X01")
      (footprint "eagle-import:1X01")
      (libsource (lib "eagle-import") (part "1X01"))
    )
    (comp (ref "JP347")
      (value "1X01")
      (footprint "eagle-import:1X01")
      (libsource (lib "eagle-import") (part "1X01"))
    )
    (comp (ref "JP348")
      (value "1X01")
      (footprint "eagle-import:1X01")
      (libsource (lib "eagle-import") (part "1X01"))
    )
    (comp (ref "JP349")
      (value "1X01")
      (footprint "eagle-import:1X01")
      (libsource (lib "eagle-import") (part "1X01"))
    )
    (comp (ref "JP350")
      (value "1X01")
      (footprint "eagle-import:1X01")
      (libsource (lib "eagle-import") (part "1X01"))
    )
    (comp (ref "JP351")
      (value "1X01")
      (footprint "eagle-import:1X01")
      (libsource (lib "eagle-import") (part "1X01"))
    )
    (comp (ref "JP352")
      (value "1X01")
      (footprint "eagle-import:1X01")
      (libsource (lib "eagle-import") (part "1X01"))
    )
    (comp (ref "JP353")
      (value "1X01")
      (footprint "eagle-import:1X01")
      (libsource (lib "eagle-import") (part "1X01"))
    )
    (comp (ref "JP354")
      (value "1X01")
      (footprint "eagle-import:1X01")
      (libsource (lib "eagle-import") (part "1X01"))
    )
    (comp (ref "JP355")
      (value "1X01")
      (footprint "eagle-import:1X01")
      (libsource (lib "eagle-import") (part "1X01"))
    )
    (comp (ref "JP356")
      (value "1X01")
      (footprint "eagle-import:1X01")
      (libsource (lib "eagle-import") (part "1X01"))
    )
    (comp (ref "JP357")
      (value "1X01")
      (footprint "eagle-import:1X01")
      (libsource (lib "eagle-import") (part "1X01"))
    )
    (comp (ref "JP358")
      (value "1X01")
      (footprint "eagle-import:1X01")
      (libsource (lib "eagle-import") (part "1X01"))
    )
    (comp (ref "JP359")
      (value "1X01")
      (footprint "eagle-import:1X01")
      (libsource (lib "eagle-import") (part "1X01"))
    )
    (comp (ref "JP360")
      (value "1X01")
      (footprint "eagle-import:1X01")
      (libsource (lib "eagle-import") (part "1X01"))
    )
    (comp (ref "JP361")
      (value "1X01")
      (footprint "eagle-import:1X01")
      (libsource (lib "eagle-import") (part "1X01"))
    )
    (comp (ref "JP362")
      (value "1X01")
      (footprint "eagle-import:1X01")
      (libsource (lib "eagle-import") (part "1X01"))
    )
    (comp (ref "JP363")
      (value "1X01")
      (footprint "eagle-import:1X01")
      (libsource (lib "eagle-import") (part "1X01"))
    )
    (comp (ref "JP364")
      (value "1X01")
      (footprint "eagle-import:1X01")
      (libsource (lib "eagle-import") (part "1X01"))
    )
    (comp (ref "JP365")
      (value "1X01")
      (footprint "eagle-import:1X01")
      (libsource (lib "eagle-import") (part "1X01"))
    )
    (comp (ref "JP366")
      (value "1X01")
      (footprint "eagle-import:1X01")
      (libsource (lib "eagle-import") (part "1X01"))
    )
    (comp (ref "JP367")
      (value "1X01")
      (footprint "eagle-import:1X01")
      (libsource (lib "eagle-import") (part "1X01"))
    )
    (comp (ref "JP368")
      (value "1X01")
      (footprint "eagle-import:1X01")
      (libsource (lib "eagle-import") (part "1X01"))
    )
    (comp (ref "JP369")
      (value "1X01")
      (footprint "eagle-import:1X01")
      (libsource (lib "eagle-import") (part "1X01"))
    )
    (comp (ref "JP370")
      (value "1X01")
      (footprint "eagle-import:1X01")
      (libsource (lib "eagle-import") (part "1X01"))
    )
    (comp (ref "JP371")
      (value "1X01")
      (footprint "eagle-import:1X01")
      (libsource (lib "eagle-import") (part "1X01"))
    )
    (comp (ref "JP372")
      (value "1X01")
      (footprint "eagle-import:1X01")
      (libsource (lib "eagle-import") (part "1X01"))
    )
    (comp (ref "JP373")
      (value "1X01")
      (footprint "eagle-import:1X01")
      (libsource (lib "eagle-import") (part "1X01"))
    )
    (comp (ref "JP374")
      (value "1X01")
      (footprint "eagle-import:1X01")
      (libsource (lib "eagle-import") (part "1X01"))
    )
    (comp (ref "JP375")
      (value "1X01")
      (footprint "eagle-import:1X01")
      (libsource (lib "eagle-import") (part "1X01"))
    )
    (comp (ref "JP376")
      (value "1X01")
      (footprint "eagle-import:1X01")
      (libsource (lib "eagle-import") (part "1X01"))
    )
    (comp (ref "JP377")
      (value "1X01")
      (footprint "eagle-import:1X01")
      (libsource (lib "eagle-import") (part "1X01"))
    )
    (comp (ref "JP378")
      (value "1X01")
      (footprint "eagle-import:1X01")
      (libsource (lib "eagle-import") (part "1X01"))
    )
    (comp (ref "JP379")
      (value "1X01")
      (footprint "eagle-import:1X01")
      (libsource (lib "eagle-import") (part "1X01"))
    )
    (comp (ref "JP380")
      (value "1X01")
      (footprint "eagle-import:1X01")
      (libsource (lib "eagle-import") (part "1X01"))
    )
    (comp (ref "JP381")
      (value "1X01")
      (footprint "eagle-import:1X01")
      (libsource (lib "eagle-import") (part "1X01"))
    )
    (comp (ref "JP382")
      (value "1X01")
      (footprint "eagle-import:1X01")
      (libsource (lib "eagle-import") (part "1X01"))
    )
    (comp (ref "JP383")
      (value "1X01")
      (footprint "eagle-import:1X01")
      (libsource (lib "eagle-import") (part "1X01"))
    )
    (comp (ref "JP384")
      (value "1X01")
      (footprint "eagle-import:1X01")
      (libsource (lib "eagle-import") (part "1X01"))
    )
    (comp (ref "JP385")
      (value "1X01")
      (footprint "eagle-import:1X01")
      (libsource (lib "eagle-import") (part "1X01"))
    )
    (comp (ref "JP386")
      (value "1X01")
      (footprint "eagle-import:1X01")
      (libsource (lib "eagle-import") (part "1X01"))
    )
    (comp (ref "JP387")
      (value "1X01")
      (footprint "eagle-import:1X01")
      (libsource (lib "eagle-import") (part "1X01"))
    )
    (comp (ref "JP388")
      (value "1X01")
      (footprint "eagle-import:1X01")
      (libsource (lib "eagle-import") (part "1X01"))
    )
    (comp (ref "JP389")
      (value "1X01")
      (footprint "eagle-import:1X01")
      (libsource (lib "eagle-import") (part "1X01"))
    )
    (comp (ref "JP390")
      (value "1X01")
      (footprint "eagle-import:1X01")
      (libsource (lib "eagle-import") (part "1X01"))
    )
    (comp (ref "JP391")
      (value "1X01")
      (footprint "eagle-import:1X01")
      (libsource (lib "eagle-import") (part "1X01"))
    )
    (comp (ref "JP392")
      (value "1X01")
      (footprint "eagle-import:1X01")
      (libsource (lib "eagle-import") (part "1X01"))
    )
    (comp (ref "JP393")
      (value "1X01")
      (footprint "eagle-import:1X01")
      (libsource (lib "eagle-import") (part "1X01"))
    )
    (comp (ref "JP394")
      (value "1X01")
      (footprint "eagle-import:1X01")
      (libsource (lib "eagle-import") (part "1X01"))
    )
    (comp (ref "JP395")
      (value "1X01")
      (footprint "eagle-import:1X01")
      (libsource (lib "eagle-import") (part "1X01"))
    )
    (comp (ref "JP396")
      (value "1X01")
      (footprint "eagle-import:1X01")
      (libsource (lib "eagle-import") (part "1X01"))
    )
    (comp (ref "JP397")
      (value "1X01")
      (footprint "eagle-import:1X01")
      (libsource (lib "eagle-import") (part "1X01"))
    )
    (comp (ref "JP398")
      (value "1X01")
      (footprint "eagle-import:1X01")
      (libsource (lib "eagle-import") (part "1X01"))
    )
    (comp (ref "JP399")
      (value "1X01")
      (footprint "eagle-import:1X01")
      (libsource (lib "eagle-import") (part "1X01"))
    )
    (comp (ref "JP400")
      (value "1X01")
      (footprint "eagle-import:1X01")
      (libsource (lib "eagle-import") (part "1X01"))
    )
    (comp (ref "JP401")
      (value "1X01")
      (footprint "eagle-import:1X01")
      (libsource (lib "eagle-import") (part "1X01"))
    )
    (comp (ref "JP402")
      (value "1X01")
      (footprint "eagle-import:1X01")
      (libsource (lib "eagle-import") (part "1X01"))
    )
    (comp (ref "JP403")
      (value "1X01")
      (footprint "eagle-import:1X01")
      (libsource (lib "eagle-import") (part "1X01"))
    )
    (comp (ref "JP404")
      (value "1X01")
      (footprint "eagle-import:1X01")
      (libsource (lib "eagle-import") (part "1X01"))
    )
    (comp (ref "JP405")
      (value "1X01")
      (footprint "eagle-import:1X01")
      (libsource (lib "eagle-import") (part "1X01"))
    )
    (comp (ref "JP406")
      (value "1X01")
      (footprint "eagle-import:1X01")
      (libsource (lib "eagle-import") (part "1X01"))
    )
    (comp (ref "JP407")
      (value "1X01")
      (footprint "eagle-import:1X01")
      (libsource (lib "eagle-import") (part "1X01"))
    )
    (comp (ref "JP408")
      (value "1X01")
      (footprint "eagle-import:1X01")
      (libsource (lib "eagle-import") (part "1X01"))
    )
    (comp (ref "JP409")
      (value "1X01")
      (footprint "eagle-import:1X01")
      (libsource (lib "eagle-import") (part "1X01"))
    )
    (comp (ref "JP410")
      (value "1X01")
      (footprint "eagle-import:1X01")
      (libsource (lib "eagle-import") (part "1X01"))
    )
    (comp (ref "JP411")
      (value "1X01")
      (footprint "eagle-import:1X01")
      (libsource (lib "eagle-import") (part "1X01"))
    )
    (comp (ref "JP412")
      (value "1X01")
      (footprint "eagle-import:1X01")
      (libsource (lib "eagle-import") (part "1X01"))
    )
    (comp (ref "JP413")
      (value "1X01")
      (footprint "eagle-import:1X01")
      (libsource (lib "eagle-import") (part "1X01"))
    )
    (comp (ref "JP414")
      (value "1X01")
      (footprint "eagle-import:1X01")
      (libsource (lib "eagle-import") (part "1X01"))
    )
    (comp (ref "JP415")
      (value "1X01")
      (footprint "eagle-import:1X01")
      (libsource (lib "eagle-import") (part "1X01"))
    )
    (comp (ref "JP416")
      (value "1X01")
      (footprint "eagle-import:1X01")
      (libsource (lib "eagle-import") (part "1X01"))
    )
    (comp (ref "JP417")
      (value "1X01")
      (footprint "eagle-import:1X01")
      (libsource (lib "eagle-import") (part "1X01"))
    )
    (comp (ref "JP418")
      (value "1X01")
      (footprint "eagle-import:1X01")
      (libsource (lib "eagle-import") (part "1X01"))
    )
    (comp (ref "JP419")
      (value "1X01")
      (footprint "eagle-import:1X01")
      (libsource (lib "eagle-import") (part "1X01"))
    )
    (comp (ref "JP420")
      (value "1X01")
      (footprint "eagle-import:1X01")
      (libsource (lib "eagle-import") (part "1X01"))
    )
    (comp (ref "JP421")
      (value "1X01")
      (footprint "eagle-import:1X01")
      (libsource (lib "eagle-import") (part "1X01"))
    )
    (comp (ref "JP422")
      (value "1X01")
      (footprint "eagle-import:1X01")
      (libsource (lib "eagle-import") (part "1X01"))
    )
    (comp (ref "JP423")
      (value "1X01")
      (footprint "eagle-import:1X01")
      (libsource (lib "eagle-import") (part "1X01"))
    )
    (comp (ref "JP424")
      (value "1X01")
      (footprint "eagle-import:1X01")
      (libsource (lib "eagle-import") (part "1X01"))
    )
    (comp (ref "JP425")
      (value "1X01")
      (footprint "eagle-import:1X01")
      (libsource (lib "eagle-import") (part "1X01"))
    )
    (comp (ref "JP426")
      (value "1X01")
      (footprint "eagle-import:1X01")
      (libsource (lib "eagle-import") (part "1X01"))
    )
    (comp (ref "JP427")
      (value "1X01")
      (footprint "eagle-import:1X01")
      (libsource (lib "eagle-import") (part "1X01"))
    )
    (comp (ref "JP428")
      (value "1X01")
      (footprint "eagle-import:1X01")
      (libsource (lib "eagle-import") (part "1X01"))
    )
    (comp (ref "JP429")
      (value "1X01")
      (footprint "eagle-import:1X01")
      (libsource (lib "eagle-import") (part "1X01"))
    )
    (comp (ref "JP430")
      (value "1X01")
      (footprint "eagle-import:1X01")
      (libsource (lib "eagle-import") (part "1X01"))
    )
    (comp (ref "JP431")
      (value "1X01")
      (footprint "eagle-import:1X01")
      (libsource (lib "eagle-import") (part "1X01"))
    )
    (comp (ref "JP432")
      (value "1X01")
      (footprint "eagle-import:1X01")
      (libsource (lib "eagle-import") (part "1X01"))
    )
    (comp (ref "JP433")
      (value "1X01")
      (footprint "eagle-import:1X01")
      (libsource (lib "eagle-import") (part "1X01"))
    )
    (comp (ref "JP434")
      (value "1X01")
      (footprint "eagle-import:1X01")
      (libsource (lib "eagle-import") (part "1X01"))
    )
    (comp (ref "JP435")
      (value "1X01")
      (footprint "eagle-import:1X01")
      (libsource (lib "eagle-import") (part "1X01"))
    )
    (comp (ref "JP436")
      (value "1X01")
      (footprint "eagle-import:1X01")
      (libsource (lib "eagle-import") (part "1X01"))
    )
    (comp (ref "JP437")
      (value "1X01")
      (footprint "eagle-import:1X01")
      (libsource (lib "eagle-import") (part "1X01"))
    )
    (comp (ref "JP438")
      (value "1X01")
      (footprint "eagle-import:1X01")
      (libsource (lib "eagle-import") (part "1X01"))
    )
    (comp (ref "JP439")
      (value "1X01")
      (footprint "eagle-import:1X01")
      (libsource (lib "eagle-import") (part "1X01"))
    )
    (comp (ref "JP440")
      (value "1X01")
      (footprint "eagle-import:1X01")
      (libsource (lib "eagle-import") (part "1X01"))
    )
    (comp (ref "JP441")
      (value "1X01")
      (footprint "eagle-import:1X01")
      (libsource (lib "eagle-import") (part "1X01"))
    )
    (comp (ref "JP442")
      (value "1X01")
      (footprint "eagle-import:1X01")
      (libsource (lib "eagle-import") (part "1X01"))
    )
    (comp (ref "JP443")
      (value "1X01")
      (footprint "eagle-import:1X01")
      (libsource (lib "eagle-import") (part "1X01"))
    )
    (comp (ref "JP444")
      (value "1X01")
      (footprint "eagle-import:1X01")
      (libsource (lib "eagle-import") (part "1X01"))
    )
    (comp (ref "JP445")
      (value "1X01")
      (footprint "eagle-import:1X01")
      (libsource (lib "eagle-import") (part "1X01"))
    )
    (comp (ref "JP446")
      (value "1X01")
      (footprint "eagle-import:1X01")
      (libsource (lib "eagle-import") (part "1X01"))
    )
    (comp (ref "JP447")
      (value "1X01")
      (footprint "eagle-import:1X01")
      (libsource (lib "eagle-import") (part "1X01"))
    )
    (comp (ref "JP448")
      (value "1X01")
      (footprint "eagle-import:1X01")
      (libsource (lib "eagle-import") (part "1X01"))
    )
    (comp (ref "JP449")
      (value "1X01")
      (footprint "eagle-import:1X01")
      (libsource (lib "eagle-import") (part "1X01"))
    )
    (comp (ref "JP450")
      (value "1X01")
      (footprint "eagle-import:1X01")
      (libsource (lib "eagle-import") (part "1X01"))
    )
    (comp (ref "JP451")
      (value "1X01")
      (footprint "eagle-import:1X01")
      (libsource (lib "eagle-import") (part "1X01"))
    )
    (comp (ref "JP452")
      (value "1X01")
      (footprint "eagle-import:1X01")
      (libsource (lib "eagle-import") (part "1X01"))
    )
    (comp (ref "JP453")
      (value "1X01")
      (footprint "eagle-import:1X01")
      (libsource (lib "eagle-import") (part "1X01"))
    )
    (comp (ref "JP454")
      (value "1X01")
      (footprint "eagle-import:1X01")
      (libsource (lib "eagle-import") (part "1X01"))
    )
    (comp (ref "JP455")
      (value "1X01")
      (footprint "eagle-import:1X01")
      (libsource (lib "eagle-import") (part "1X01"))
    )
    (comp (ref "JP456")
      (value "1X01")
      (footprint "eagle-import:1X01")
      (libsource (lib "eagle-import") (part "1X01"))
    )
    (comp (ref "JP457")
      (value "1X01")
      (footprint "eagle-import:1X01")
      (libsource (lib "eagle-import") (part "1X01"))
    )
    (comp (ref "JP458")
      (value "1X01")
      (footprint "eagle-import:1X01")
      (libsource (lib "eagle-import") (part "1X01"))
    )
    (comp (ref "JP459")
      (value "1X01")
      (footprint "eagle-import:1X01")
      (libsource (lib "eagle-import") (part "1X01"))
    )
    (comp (ref "JP460")
      (value "1X01")
      (footprint "eagle-import:1X01")
      (libsource (lib "eagle-import") (part "1X01"))
    )
    (comp (ref "JP461")
      (value "1X01")
      (footprint "eagle-import:1X01")
      (libsource (lib "eagle-import") (part "1X01"))
    )
    (comp (ref "JP462")
      (value "1X01")
      (footprint "eagle-import:1X01")
      (libsource (lib "eagle-import") (part "1X01"))
    )
    (comp (ref "JP463")
      (value "1X01")
      (footprint "eagle-import:1X01")
      (libsource (lib "eagle-import") (part "1X01"))
    )
    (comp (ref "JP464")
      (value "1X01")
      (footprint "eagle-import:1X01")
      (libsource (lib "eagle-import") (part "1X01"))
    )
    (comp (ref "JP465")
      (value "1X01")
      (footprint "eagle-import:1X01")
      (libsource (lib "eagle-import") (part "1X01"))
    )
    (comp (ref "JP466")
      (value "1X01")
      (footprint "eagle-import:1X01")
      (libsource (lib "eagle-import") (part "1X01"))
    )
    (comp (ref "JP467")
      (value "1X01")
      (footprint "eagle-import:1X01")
      (libsource (lib "eagle-import") (part "1X01"))
    )
    (comp (ref "JP468")
      (value "1X01")
      (footprint "eagle-import:1X01")
      (libsource (lib "eagle-import") (part "1X01"))
    )
    (comp (ref "JP469")
      (value "1X01")
      (footprint "eagle-import:1X01")
      (libsource (lib "eagle-import") (part "1X01"))
    )
    (comp (ref "JP470")
      (value "1X01")
      (footprint "eagle-import:1X01")
      (libsource (lib "eagle-import") (part "1X01"))
    )
    (comp (ref "JP471")
      (value "1X01")
      (footprint "eagle-import:1X01")
      (libsource (lib "eagle-import") (part "1X01"))
    )
    (comp (ref "JP472")
      (value "1X01")
      (footprint "eagle-import:1X01")
      (libsource (lib "eagle-import") (part "1X01"))
    )
    (comp (ref "JP473")
      (value "1X01")
      (footprint "eagle-import:1X01")
      (libsource (lib "eagle-import") (part "1X01"))
    )
    (comp (ref "JP474")
      (value "1X01")
      (footprint "eagle-import:1X01")
      (libsource (lib "eagle-import") (part "1X01"))
    )
    (comp (ref "JP475")
      (value "1X01")
      (footprint "eagle-import:1X01")
      (libsource (lib "eagle-import") (part "1X01"))
    )
    (comp (ref "JP476")
      (value "1X01")
      (footprint "eagle-import:1X01")
      (libsource (lib "eagle-import") (part "1X01"))
    )
    (comp (ref "JP477")
      (value "1X01")
      (footprint "eagle-import:1X01")
      (libsource (lib "eagle-import") (part "1X01"))
    )
    (comp (ref "JP478")
      (value "1X01")
      (footprint "eagle-import:1X01")
      (libsource (lib "eagle-import") (part "1X01"))
    )
    (comp (ref "JP479")
      (value "1X01")
      (footprint "eagle-import:1X01")
      (libsource (lib "eagle-import") (part "1X01"))
    )
    (comp (ref "JP480")
      (value "1X01")
      (footprint "eagle-import:1X01")
      (libsource (lib "eagle-import") (part "1X01"))
    )
    (comp (ref "JP481")
      (value "1X01")
      (footprint "eagle-import:1X01")
      (libsource (lib "eagle-import") (part "1X01"))
    )
    (comp (ref "JP482")
      (value "1X01")
      (footprint "eagle-import:1X01")
      (libsource (lib "eagle-import") (part "1X01"))
    )
    (comp (ref "JP483")
      (value "1X01")
      (footprint "eagle-import:1X01")
      (libsource (lib "eagle-import") (part "1X01"))
    )
    (comp (ref "JP484")
      (value "1X01")
      (footprint "eagle-import:1X01")
      (libsource (lib "eagle-import") (part "1X01"))
    )
    (comp (ref "JP485")
      (value "1X01")
      (footprint "eagle-import:1X01")
      (libsource (lib "eagle-import") (part "1X01"))
    )
    (comp (ref "JP486")
      (value "1X01")
      (footprint "eagle-import:1X01")
      (libsource (lib "eagle-import") (part "1X01"))
    )
    (comp (ref "JP487")
      (value "1X01")
      (footprint "eagle-import:1X01")
      (libsource (lib "eagle-import") (part "1X01"))
    )
    (comp (ref "JP488")
      (value "1X01")
      (footprint "eagle-import:1X01")
      (libsource (lib "eagle-import") (part "1X01"))
    )
    (comp (ref "JP489")
      (value "1X01")
      (footprint "eagle-import:1X01")
      (libsource (lib "eagle-import") (part "1X01"))
    )
    (comp (ref "JP490")
      (value "1X01")
      (footprint "eagle-import:1X01")
      (libsource (lib "eagle-import") (part "1X01"))
    )
    (comp (ref "JP491")
      (value "1X01")
      (footprint "eagle-import:1X01")
      (libsource (lib "eagle-import") (part "1X01"))
    )
    (comp (ref "JP492")
      (value "1X01")
      (footprint "eagle-import:1X01")
      (libsource (lib "eagle-import") (part "1X01"))
    )
    (comp (ref "JP493")
      (value "1X01")
      (footprint "eagle-import:1X01")
      (libsource (lib "eagle-import") (part "1X01"))
    )
    (comp (ref "JP494")
      (value "1X01")
      (footprint "eagle-import:1X01")
      (libsource (lib "eagle-import") (part "1X01"))
    )
    (comp (ref "JP495")
      (value "1X01")
      (footprint "eagle-import:1X01")
      (libsource (lib "eagle-import") (part "1X01"))
    )
    (comp (ref "JP496")
      (value "1X01")
      (footprint "eagle-import:1X01")
      (libsource (lib "eagle-import") (part "1X01"))
    )
    (comp (ref "JP497")
      (value "1X01")
      (footprint "eagle-import:1X01")
      (libsource (lib "eagle-import") (part "1X01"))
    )
    (comp (ref "JP498")
      (value "1X01")
      (footprint "eagle-import:1X01")
      (libsource (lib "eagle-import") (part "1X01"))
    )
    (comp (ref "JP499")
      (value "1X01")
      (footprint "eagle-import:1X01")
      (libsource (lib "eagle-import") (part "1X01"))
    )
    (comp (ref "JP500")
      (value "1X01")
      (footprint "eagle-import:1X01")
      (libsource (lib "eagle-import") (part "1X01"))
    )
    (comp (ref "JP501")
      (value "1X01")
      (footprint "eagle-import:1X01")
      (libsource (lib "eagle-import") (part "1X01"))
    )
    (comp (ref "JP502")
      (value "1X01")
      (footprint "eagle-import:1X01")
      (libsource (lib "eagle-import") (part "1X01"))
    )
    (comp (ref "JP503")
      (value "1X01")
      (footprint "eagle-import:1X01")
      (libsource (lib "eagle-import") (part "1X01"))
    )
    (comp (ref "JP504")
      (value "1X01")
      (footprint "eagle-import:1X01")
      (libsource (lib "eagle-import") (part "1X01"))
    )
    (comp (ref "JP505")
      (value "1X01")
      (footprint "eagle-import:1X01")
      (libsource (lib "eagle-import") (part "1X01"))
    )
    (comp (ref "JP506")
      (value "1X01")
      (footprint "eagle-import:1X01")
      (libsource (lib "eagle-import") (part "1X01"))
    )
    (comp (ref "JP507")
      (value "1X01")
      (footprint "eagle-import:1X01")
      (libsource (lib "eagle-import") (part "1X01"))
    )
    (comp (ref "JP508")
      (value "1X01")
      (footprint "eagle-import:1X01")
      (libsource (lib "eagle-import") (part "1X01"))
    )
    (comp (ref "JP509")
      (value "1X01")
      (footprint "eagle-import:1X01")
      (libsource (lib "eagle-import") (part "1X01"))
    )
    (comp (ref "JP510")
      (value "1X01")
      (footprint "eagle-import:1X01")
      (libsource (lib "eagle-import") (part "1X01"))
    )
    (comp (ref "JP511")
      (value "1X01")
      (footprint "eagle-import:1X01")
      (libsource (lib "eagle-import") (part "1X01"))
    )
    (comp (ref "JP512")
      (value "1X01")
      (footprint "eagle-import:1X01")
      (libsource (lib "eagle-import") (part "1X01"))
    )
    (comp (ref "JP513")
      (value "1X01")
      (footprint "eagle-import:1X01")
      (libsource (lib "eagle-import") (part "1X01"))
    )
    (comp (ref "JP514")
      (value "1X01")
      (footprint "eagle-import:1X01")
      (libsource (lib "eagle-import") (part "1X01"))
    )
    (comp (ref "JP515")
      (value "1X01")
      (footprint "eagle-import:1X01")
      (libsource (lib "eagle-import") (part "1X01"))
    )
    (comp (ref "JP516")
      (value "1X01")
      (footprint "eagle-import:1X01")
      (libsource (lib "eagle-import") (part "1X01"))
    )
    (comp (ref "JP517")
      (value "1X01")
      (footprint "eagle-import:1X01")
      (libsource (lib "eagle-import") (part "1X01"))
    )
    (comp (ref "JP518")
      (value "1X01")
      (footprint "eagle-import:1X01")
      (libsource (lib "eagle-import") (part "1X01"))
    )
    (comp (ref "JP519")
      (value "1X01")
      (footprint "eagle-import:1X01")
      (libsource (lib "eagle-import") (part "1X01"))
    )
    (comp (ref "JP520")
      (value "1X01")
      (footprint "eagle-import:1X01")
      (libsource (lib "eagle-import") (part "1X01"))
    )
    (comp (ref "JP521")
      (value "1X01")
      (footprint "eagle-import:1X01")
      (libsource (lib "eagle-import") (part "1X01"))
    )
    (comp (ref "JP522")
      (value "1X01")
      (footprint "eagle-import:1X01")
      (libsource (lib "eagle-import") (part "1X01"))
    )
    (comp (ref "JP523")
      (value "1X01")
      (footprint "eagle-import:1X01")
      (libsource (lib "eagle-import") (part "1X01"))
    )
    (comp (ref "JP524")
      (value "1X01")
      (footprint "eagle-import:1X01")
      (libsource (lib "eagle-import") (part "1X01"))
    )
    (comp (ref "JP525")
      (value "1X01")
      (footprint "eagle-import:1X01")
      (libsource (lib "eagle-import") (part "1X01"))
    )
    (comp (ref "JP526")
      (value "1X01")
      (footprint "eagle-import:1X01")
      (libsource (lib "eagle-import") (part "1X01"))
    )
    (comp (ref "JP527")
      (value "1X01")
      (footprint "eagle-import:1X01")
      (libsource (lib "eagle-import") (part "1X01"))
    )
    (comp (ref "JP528")
      (value "1X01")
      (footprint "eagle-import:1X01")
      (libsource (lib "eagle-import") (part "1X01"))
    )
    (comp (ref "JP529")
      (value "1X01")
      (footprint "eagle-import:1X01")
      (libsource (lib "eagle-import") (part "1X01"))
    )
    (comp (ref "JP530")
      (value "1X01")
      (footprint "eagle-import:1X01")
      (libsource (lib "eagle-import") (part "1X01"))
    )
    (comp (ref "JP531")
      (value "1X01")
      (footprint "eagle-import:1X01")
      (libsource (lib "eagle-import") (part "1X01"))
    )
    (comp (ref "JP532")
      (value "1X01")
      (footprint "eagle-import:1X01")
      (libsource (lib "eagle-import") (part "1X01"))
    )
    (comp (ref "JP533")
      (value "1X01")
      (footprint "eagle-import:1X01")
      (libsource (lib "eagle-import") (part "1X01"))
    )
    (comp (ref "JP534")
      (value "1X01")
      (footprint "eagle-import:1X01")
      (libsource (lib "eagle-import") (part "1X01"))
    )
    (comp (ref "JP535")
      (value "1X01")
      (footprint "eagle-import:1X01")
      (libsource (lib "eagle-import") (part "1X01"))
    )
    (comp (ref "JP536")
      (value "1X01")
      (footprint "eagle-import:1X01")
      (libsource (lib "eagle-import") (part "1X01"))
    )
    (comp (ref "JP537")
      (value "1X01")
      (footprint "eagle-import:1X01")
      (libsource (lib "eagle-import") (part "1X01"))
    )
    (comp (ref "JP538")
      (value "1X01")
      (footprint "eagle-import:1X01")
      (libsource (lib "eagle-import") (part "1X01"))
    )
    (comp (ref "JP539")
      (value "1X01")
      (footprint "eagle-import:1X01")
      (libsource (lib "eagle-import") (part "1X01"))
    )
    (comp (ref "JP540")
      (value "1X01")
      (footprint "eagle-import:1X01")
      (libsource (lib "eagle-import") (part "1X01"))
    )
    (comp (ref "JP541")
      (value "1X01")
      (footprint "eagle-import:1X01")
      (libsource (lib "eagle-import") (part "1X01"))
    )
    (comp (ref "JP542")
      (value "1X01")
      (footprint "eagle-import:1X01")
      (libsource (lib "eagle-import") (part "1X01"))
    )
    (comp (ref "JP543")
      (value "1X01")
      (footprint "eagle-import:1X01")
      (libsource (lib "eagle-import") (part "1X01"))
    )
    (comp (ref "JP544")
      (value "1X01")
      (footprint "eagle-import:1X01")
      (libsource (lib "eagle-import") (part "1X01"))
    )
    (comp (ref "JP545")
      (value "1X01")
      (footprint "eagle-import:1X01")
      (libsource (lib "eagle-import") (part "1X01"))
    )
    (comp (ref "JP546")
      (value "1X01")
      (footprint "eagle-import:1X01")
      (libsource (lib "eagle-import") (part "1X01"))
    )
    (comp (ref "JP547")
      (value "1X01")
      (footprint "eagle-import:1X01")
      (libsource (lib "eagle-import") (part "1X01"))
    )
    (comp (ref "JP548")
      (value "1X01")
      (footprint "eagle-import:1X01")
      (libsource (lib "eagle-import") (part "1X01"))
    )
    (comp (ref "JP549")
      (value "1X01")
      (footprint "eagle-import:1X01")
      (libsource (lib "eagle-import") (part "1X01"))
    )
    (comp (ref "JP550")
      (value "1X01")
      (footprint "eagle-import:1X01")
      (libsource (lib "eagle-import") (part "1X01"))
    )
    (comp (ref "JP551")
      (value "1X01")
      (footprint "eagle-import:1X01")
      (libsource (lib "eagle-import") (part "1X01"))
    )
    (comp (ref "JP552")
      (value "1X01")
      (footprint "eagle-import:1X01")
      (libsource (lib "eagle-import") (part "1X01"))
    )
    (comp (ref "JP553")
      (value "1X01")
      (footprint "eagle-import:1X01")
      (libsource (lib "eagle-import") (part "1X01"))
    )
    (comp (ref "JP554")
      (value "1X01")
      (footprint "eagle-import:1X01")
      (libsource (lib "eagle-import") (part "1X01"))
    )
    (comp (ref "JP555")
      (value "1X01")
      (footprint "eagle-import:1X01")
      (libsource (lib "eagle-import") (part "1X01"))
    )
    (comp (ref "JP556")
      (value "1X01")
      (footprint "eagle-import:1X01")
      (libsource (lib "eagle-import") (part "1X01"))
    )
    (comp (ref "JP557")
      (value "1X01")
      (footprint "eagle-import:1X01")
      (libsource (lib "eagle-import") (part "1X01"))
    )
    (comp (ref "JP558")
      (value "1X01")
      (footprint "eagle-import:1X01")
      (libsource (lib "eagle-import") (part "1X01"))
    )
    (comp (ref "JP559")
      (value "1X01")
      (footprint "eagle-import:1X01")
      (libsource (lib "eagle-import") (part "1X01"))
    )
    (comp (ref "JP560")
      (value "1X01")
      (footprint "eagle-import:1X01")
      (libsource (lib "eagle-import") (part "1X01"))
    )
    (comp (ref "JP561")
      (value "1X01")
      (footprint "eagle-import:1X01")
      (libsource (lib "eagle-import") (part "1X01"))
    )
    (comp (ref "JP562")
      (value "1X01")
      (footprint "eagle-import:1X01")
      (libsource (lib "eagle-import") (part "1X01"))
    )
    (comp (ref "JP563")
      (value "1X01")
      (footprint "eagle-import:1X01")
      (libsource (lib "eagle-import") (part "1X01"))
    )
    (comp (ref "JP564")
      (value "1X01")
      (footprint "eagle-import:1X01")
      (libsource (lib "eagle-import") (part "1X01"))
    )
    (comp (ref "JP565")
      (value "1X01")
      (footprint "eagle-import:1X01")
      (libsource (lib "eagle-import") (part "1X01"))
    )
    (comp (ref "JP566")
      (value "1X01")
      (footprint "eagle-import:1X01")
      (libsource (lib "eagle-import") (part "1X01"))
    )
    (comp (ref "JP567")
      (value "1X01")
      (footprint "eagle-import:1X01")
      (libsource (lib "eagle-import") (part "1X01"))
    )
    (comp (ref "JP568")
      (value "1X01")
      (footprint "eagle-import:1X01")
      (libsource (lib "eagle-import") (part "1X01"))
    )
    (comp (ref "JP569")
      (value "1X01")
      (footprint "eagle-import:1X01")
      (libsource (lib "eagle-import") (part "1X01"))
    )
    (comp (ref "JP570")
      (value "1X01")
      (footprint "eagle-import:1X01")
      (libsource (lib "eagle-import") (part "1X01"))
    )
    (comp (ref "JP571")
      (value "1X01")
      (footprint "eagle-import:1X01")
      (libsource (lib "eagle-import") (part "1X01"))
    )
    (comp (ref "JP572")
      (value "1X01")
      (footprint "eagle-import:1X01")
      (libsource (lib "eagle-import") (part "1X01"))
    )
    (comp (ref "JP573")
      (value "1X01")
      (footprint "eagle-import:1X01")
      (libsource (lib "eagle-import") (part "1X01"))
    )
    (comp (ref "JP574")
      (value "1X01")
      (footprint "eagle-import:1X01")
      (libsource (lib "eagle-import") (part "1X01"))
    )
    (comp (ref "JP575")
      (value "1X01")
      (footprint "eagle-import:1X01")
      (libsource (lib "eagle-import") (part "1X01"))
    )
    (comp (ref "JP576")
      (value "1X01")
      (footprint "eagle-import:1X01")
      (libsource (lib "eagle-import") (part "1X01"))
    )
    (comp (ref "JP577")
      (value "1X01")
      (footprint "eagle-import:1X01")
      (libsource (lib "eagle-import") (part "1X01"))
    )
    (comp (ref "JP578")
      (value "1X01")
      (footprint "eagle-import:1X01")
      (libsource (lib "eagle-import") (part "1X01"))
    )
    (comp (ref "JP579")
      (value "1X01")
      (footprint "eagle-import:1X01")
      (libsource (lib "eagle-import") (part "1X01"))
    )
    (comp (ref "JP580")
      (value "1X01")
      (footprint "eagle-import:1X01")
      (libsource (lib "eagle-import") (part "1X01"))
    )
    (comp (ref "JP581")
      (value "1X01")
      (footprint "eagle-import:1X01")
      (libsource (lib "eagle-import") (part "1X01"))
    )
    (comp (ref "JP582")
      (value "1X01")
      (footprint "eagle-import:1X01")
      (libsource (lib "eagle-import") (part "1X01"))
    )
    (comp (ref "JP583")
      (value "1X01")
      (footprint "eagle-import:1X01")
      (libsource (lib "eagle-import") (part "1X01"))
    )
    (comp (ref "JP584")
      (value "1X01")
      (footprint "eagle-import:1X01")
      (libsource (lib "eagle-import") (part "1X01"))
    )
    (comp (ref "JP585")
      (value "1X01")
      (footprint "eagle-import:1X01")
      (libsource (lib "eagle-import") (part "1X01"))
    )
    (comp (ref "JP586")
      (value "1X01")
      (footprint "eagle-import:1X01")
      (libsource (lib "eagle-import") (part "1X01"))
    )
    (comp (ref "JP587")
      (value "1X01")
      (footprint "eagle-import:1X01")
      (libsource (lib "eagle-import") (part "1X01"))
    )
    (comp (ref "JP588")
      (value "1X01")
      (footprint "eagle-import:1X01")
      (libsource (lib "eagle-import") (part "1X01"))
    )
    (comp (ref "JP589")
      (value "1X01")
      (footprint "eagle-import:1X01")
      (libsource (lib "eagle-import") (part "1X01"))
    )
    (comp (ref "JP590")
      (value "1X01")
      (footprint "eagle-import:1X01")
      (libsource (lib "eagle-import") (part "1X01"))
    )
    (comp (ref "JP591")
      (value "1X01")
      (footprint "eagle-import:1X01")
      (libsource (lib "eagle-import") (part "1X01"))
    )
    (comp (ref "JP592")
      (value "1X01")
      (footprint "eagle-import:1X01")
      (libsource (lib "eagle-import") (part "1X01"))
    )
    (comp (ref "JP593")
      (value "1X01")
      (footprint "eagle-import:1X01")
      (libsource (lib "eagle-import") (part "1X01"))
    )
    (comp (ref "JP594")
      (value "1X01")
      (footprint "eagle-import:1X01")
      (libsource (lib "eagle-import") (part "1X01"))
    )
    (comp (ref "JP595")
      (value "1X01")
      (footprint "eagle-import:1X01")
      (libsource (lib "eagle-import") (part "1X01"))
    )
    (comp (ref "JP596")
      (value "1X01")
      (footprint "eagle-import:1X01")
      (libsource (lib "eagle-import") (part "1X01"))
    )
    (comp (ref "JP597")
      (value "1X01")
      (footprint "eagle-import:1X01")
      (libsource (lib "eagle-import") (part "1X01"))
    )
    (comp (ref "JP598")
      (value "1X01")
      (footprint "eagle-import:1X01")
      (libsource (lib "eagle-import") (part "1X01"))
    )
    (comp (ref "JP599")
      (value "1X01")
      (footprint "eagle-import:1X01")
      (libsource (lib "eagle-import") (part "1X01"))
    )
    (comp (ref "JP600")
      (value "1X01")
      (footprint "eagle-import:1X01")
      (libsource (lib "eagle-import") (part "1X01"))
    )
    (comp (ref "JP601")
      (value "1X01")
      (footprint "eagle-import:1X01")
      (libsource (lib "eagle-import") (part "1X01"))
    )
    (comp (ref "JP602")
      (value "1X01")
      (footprint "eagle-import:1X01")
      (libsource (lib "eagle-import") (part "1X01"))
    )
    (comp (ref "JP603")
      (value "1X01")
      (footprint "eagle-import:1X01")
      (libsource (lib "eagle-import") (part "1X01"))
    )
    (comp (ref "JP604")
      (value "1X01")
      (footprint "eagle-import:1X01")
      (libsource (lib "eagle-import") (part "1X01"))
    )
    (comp (ref "JP605")
      (value "1X01")
      (footprint "eagle-import:1X01")
      (libsource (lib "eagle-import") (part "1X01"))
    )
    (comp (ref "JP606")
      (value "1X01")
      (footprint "eagle-import:1X01")
      (libsource (lib "eagle-import") (part "1X01"))
    )
    (comp (ref "JP607")
      (value "1X01")
      (footprint "eagle-import:1X01")
      (libsource (lib "eagle-import") (part "1X01"))
    )
    (comp (ref "JP608")
      (value "1X01")
      (footprint "eagle-import:1X01")
      (libsource (lib "eagle-import") (part "1X01"))
    )
    (comp (ref "JP609")
      (value "1X01")
      (footprint "eagle-import:1X01")
      (libsource (lib "eagle-import") (part "1X01"))
    )
    (comp (ref "JP610")
      (value "1X01")
      (footprint "eagle-import:1X01")
      (libsource (lib "eagle-import") (part "1X01"))
    )
    (comp (ref "JP611")
      (value "1X01")
      (footprint "eagle-import:1X01")
      (libsource (lib "eagle-import") (part "1X01"))
    )
    (comp (ref "JP612")
      (value "1X01")
      (footprint "eagle-import:1X01")
      (libsource (lib "eagle-import") (part "1X01"))
    )
    (comp (ref "JP613")
      (value "1X01")
      (footprint "eagle-import:1X01")
      (libsource (lib "eagle-import") (part "1X01"))
    )
    (comp (ref "JP614")
      (value "1X01")
      (footprint "eagle-import:1X01")
      (libsource (lib "eagle-import") (part "1X01"))
    )
    (comp (ref "JP615")
      (value "1X01")
      (footprint "eagle-import:1X01")
      (libsource (lib "eagle-import") (part "1X01"))
    )
    (comp (ref "JP616")
      (value "1X01")
      (footprint "eagle-import:1X01")
      (libsource (lib "eagle-import") (part "1X01"))
    )
    (comp (ref "JP617")
      (value "1X01")
      (footprint "eagle-import:1X01")
      (libsource (lib "eagle-import") (part "1X01"))
    )
    (comp (ref "JP618")
      (value "1X01")
      (footprint "eagle-import:1X01")
      (libsource (lib "eagle-import") (part "1X01"))
    )
    (comp (ref "JP619")
      (value "1X01")
      (footprint "eagle-import:1X01")
      (libsource (lib "eagle-import") (part "1X01"))
    )
    (comp (ref "JP620")
      (value "1X01")
      (footprint "eagle-import:1X01")
      (libsource (lib "eagle-import") (part "1X01"))
    )
    (comp (ref "JP621")
      (value "1X01")
      (footprint "eagle-import:1X01")
      (libsource (lib "eagle-import") (part "1X01"))
    )
    (comp (ref "JP622")
      (value "1X01")
      (footprint "eagle-import:1X01")
      (libsource (lib "eagle-import") (part "1X01"))
    )
    (comp (ref "JP623")
      (value "1X01")
      (footprint "eagle-import:1X01")
      (libsource (lib "eagle-import") (part "1X01"))
    )
    (comp (ref "JP624")
      (value "1X01")
      (footprint "eagle-import:1X01")
      (libsource (lib "eagle-import") (part "1X01"))
    )
    (comp (ref "JP625")
      (value "1X01")
      (footprint "eagle-import:1X01")
      (libsource (lib "eagle-import") (part "1X01"))
    )
    (comp (ref "JP626")
      (value "1X01")
      (footprint "eagle-import:1X01")
      (libsource (lib "eagle-import") (part "1X01"))
    )
    (comp (ref "JP627")
      (value "1X01")
      (footprint "eagle-import:1X01")
      (libsource (lib "eagle-import") (part "1X01"))
    )
    (comp (ref "JP628")
      (value "1X01")
      (footprint "eagle-import:1X01")
      (libsource (lib "eagle-import") (part "1X01"))
    )
    (comp (ref "JP629")
      (value "1X01")
      (footprint "eagle-import:1X01")
      (libsource (lib "eagle-import") (part "1X01"))
    )
    (comp (ref "JP630")
      (value "1X01")
      (footprint "eagle-import:1X01")
      (libsource (lib "eagle-import") (part "1X01"))
    )
    (comp (ref "JP631")
      (value "1X01")
      (footprint "eagle-import:1X01")
      (libsource (lib "eagle-import") (part "1X01"))
    )
    (comp (ref "JP632")
      (value "1X01")
      (footprint "eagle-import:1X01")
      (libsource (lib "eagle-import") (part "1X01"))
    )
    (comp (ref "JP633")
      (value "1X01")
      (footprint "eagle-import:1X01")
      (libsource (lib "eagle-import") (part "1X01"))
    )
    (comp (ref "JP634")
      (value "1X01")
      (footprint "eagle-import:1X01")
      (libsource (lib "eagle-import") (part "1X01"))
    )
    (comp (ref "JP635")
      (value "1X01")
      (footprint "eagle-import:1X01")
      (libsource (lib "eagle-import") (part "1X01"))
    )
    (comp (ref "JP636")
      (value "1X01")
      (footprint "eagle-import:1X01")
      (libsource (lib "eagle-import") (part "1X01"))
    )
    (comp (ref "JP637")
      (value "1X01")
      (footprint "eagle-import:1X01")
      (libsource (lib "eagle-import") (part "1X01"))
    )
    (comp (ref "JP638")
      (value "1X01")
      (footprint "eagle-import:1X01")
      (libsource (lib "eagle-import") (part "1X01"))
    )
    (comp (ref "JP639")
      (value "1X01")
      (footprint "eagle-import:1X01")
      (libsource (lib "eagle-import") (part "1X01"))
    )
    (comp (ref "JP640")
      (value "1X01")
      (footprint "eagle-import:1X01")
      (libsource (lib "eagle-import") (part "1X01"))
    )
    (comp (ref "JP641")
      (value "1X01")
      (footprint "eagle-import:1X01")
      (libsource (lib "eagle-import") (part "1X01"))
    )
    (comp (ref "JP642")
      (value "1X01")
      (footprint "eagle-import:1X01")
      (libsource (lib "eagle-import") (part "1X01"))
    )
    (comp (ref "JP643")
      (value "1X01")
      (footprint "eagle-import:1X01")
      (libsource (lib "eagle-import") (part "1X01"))
    )
    (comp (ref "JP644")
      (value "1X01")
      (footprint "eagle-import:1X01")
      (libsource (lib "eagle-import") (part "1X01"))
    )
    (comp (ref "JP645")
      (value "1X01")
      (footprint "eagle-import:1X01")
      (libsource (lib "eagle-import") (part "1X01"))
    )
    (comp (ref "JP646")
      (value "1X01")
      (footprint "eagle-import:1X01")
      (libsource (lib "eagle-import") (part "1X01"))
    )
    (comp (ref "JP647")
      (value "1X01")
      (footprint "eagle-import:1X01")
      (libsource (lib "eagle-import") (part "1X01"))
    )
    (comp (ref "JP648")
      (value "1X01")
      (footprint "eagle-import:1X01")
      (libsource (lib "eagle-import") (part "1X01"))
    )
    (comp (ref "JP649")
      (value "1X01")
      (footprint "eagle-import:1X01")
      (libsource (lib "eagle-import") (part "1X01"))
    )
    (comp (ref "JP650")
      (value "1X01")
      (footprint "eagle-import:1X01")
      (libsource (lib "eagle-import") (part "1X01"))
    )
    (comp (ref "JP651")
      (value "1X01")
      (footprint "eagle-import:1X01")
      (libsource (lib "eagle-import") (part "1X01"))
    )
    (comp (ref "JP652")
      (value "1X01")
      (footprint "eagle-import:1X01")
      (libsource (lib "eagle-import") (part "1X01"))
    )
    (comp (ref "JP653")
      (value "1X01")
      (footprint "eagle-import:1X01")
      (libsource (lib "eagle-import") (part "1X01"))
    )
    (comp (ref "JP654")
      (value "1X01")
      (footprint "eagle-import:1X01")
      (libsource (lib "eagle-import") (part "1X01"))
    )
    (comp (ref "JP655")
      (value "1X01")
      (footprint "eagle-import:1X01")
      (libsource (lib "eagle-import") (part "1X01"))
    )
    (comp (ref "JP656")
      (value "1X01")
      (footprint "eagle-import:1X01")
      (libsource (lib "eagle-import") (part "1X01"))
    )
    (comp (ref "JP657")
      (value "1X01")
      (footprint "eagle-import:1X01")
      (libsource (lib "eagle-import") (part "1X01"))
    )
    (comp (ref "JP658")
      (value "1X01")
      (footprint "eagle-import:1X01")
      (libsource (lib "eagle-import") (part "1X01"))
    )
    (comp (ref "JP659")
      (value "1X01")
      (footprint "eagle-import:1X01")
      (libsource (lib "eagle-import") (part "1X01"))
    )
    (comp (ref "JP660")
      (value "1X01")
      (footprint "eagle-import:1X01")
      (libsource (lib "eagle-import") (part "1X01"))
    )
    (comp (ref "JP661")
      (value "1X01")
      (footprint "eagle-import:1X01")
      (libsource (lib "eagle-import") (part "1X01"))
    )
    (comp (ref "JP662")
      (value "1X01")
      (footprint "eagle-import:1X01")
      (libsource (lib "eagle-import") (part "1X01"))
    )
    (comp (ref "JP663")
      (value "1X01")
      (footprint "eagle-import:1X01")
      (libsource (lib "eagle-import") (part "1X01"))
    )
    (comp (ref "JP664")
      (value "1X01")
      (footprint "eagle-import:1X01")
      (libsource (lib "eagle-import") (part "1X01"))
    )
    (comp (ref "JP665")
      (value "1X01")
      (footprint "eagle-import:1X01")
      (libsource (lib "eagle-import") (part "1X01"))
    )
    (comp (ref "JP666")
      (value "1X01")
      (footprint "eagle-import:1X01")
      (libsource (lib "eagle-import") (part "1X01"))
    )
    (comp (ref "JP667")
      (value "1X01")
      (footprint "eagle-import:1X01")
      (libsource (lib "eagle-import") (part "1X01"))
    )
    (comp (ref "JP668")
      (value "1X01")
      (footprint "eagle-import:1X01")
      (libsource (lib "eagle-import") (part "1X01"))
    )
    (comp (ref "JP669")
      (value "1X01")
      (footprint "eagle-import:1X01")
      (libsource (lib "eagle-import") (part "1X01"))
    )
    (comp (ref "JP670")
      (value "1X01")
      (footprint "eagle-import:1X01")
      (libsource (lib "eagle-import") (part "1X01"))
    )
    (comp (ref "JP671")
      (value "1X01")
      (footprint "eagle-import:1X01")
      (libsource (lib "eagle-import") (part "1X01"))
    )
    (comp (ref "JP672")
      (value "1X01")
      (footprint "eagle-import:1X01")
      (libsource (lib "eagle-import") (part "1X01"))
    )
    (comp (ref "JP673")
      (value "1X01")
      (footprint "eagle-import:1X01")
      (libsource (lib "eagle-import") (part "1X01"))
    )
    (comp (ref "JP674")
      (value "1X01")
      (footprint "eagle-import:1X01")
      (libsource (lib "eagle-import") (part "1X01"))
    )
    (comp (ref "JP675")
      (value "1X01")
      (footprint "eagle-import:1X01")
      (libsource (lib "eagle-import") (part "1X01"))
    )
    (comp (ref "JP676")
      (value "1X01")
      (footprint "eagle-import:1X01")
      (libsource (lib "eagle-import") (part "1X01"))
    )
    (comp (ref "JP677")
      (value "1X01")
      (footprint "eagle-import:1X01")
      (libsource (lib "eagle-import") (part "1X01"))
    )
    (comp (ref "JP678")
      (value "1X01")
      (footprint "eagle-import:1X01")
      (libsource (lib "eagle-import") (part "1X01"))
    )
    (comp (ref "JP679")
      (value "1X01")
      (footprint "eagle-import:1X01")
      (libsource (lib "eagle-import") (part "1X01"))
    )
    (comp (ref "JP680")
      (value "1X01")
      (footprint "eagle-import:1X01")
      (libsource (lib "eagle-import") (part "1X01"))
    )
    (comp (ref "JP681")
      (value "1X01")
      (footprint "eagle-import:1X01")
      (libsource (lib "eagle-import") (part "1X01"))
    )
    (comp (ref "JP682")
      (value "1X01")
      (footprint "eagle-import:1X01")
      (libsource (lib "eagle-import") (part "1X01"))
    )
    (comp (ref "JP683")
      (value "1X01")
      (footprint "eagle-import:1X01")
      (libsource (lib "eagle-import") (part "1X01"))
    )
    (comp (ref "JP684")
      (value "1X01")
      (footprint "eagle-import:1X01")
      (libsource (lib "eagle-import") (part "1X01"))
    )
    (comp (ref "JP685")
      (value "1X01")
      (footprint "eagle-import:1X01")
      (libsource (lib "eagle-import") (part "1X01"))
    )
    (comp (ref "JP686")
      (value "1X01")
      (footprint "eagle-import:1X01")
      (libsource (lib "eagle-import") (part "1X01"))
    )
    (comp (ref "JP687")
      (value "1X01")
      (footprint "eagle-import:1X01")
      (libsource (lib "eagle-import") (part "1X01"))
    )
    (comp (ref "JP688")
      (value "1X01")
      (footprint "eagle-import:1X01")
      (libsource (lib "eagle-import") (part "1X01"))
    )
    (comp (ref "JP689")
      (value "1X01")
      (footprint "eagle-import:1X01")
      (libsource (lib "eagle-import") (part "1X01"))
    )
    (comp (ref "JP690")
      (value "1X01")
      (footprint "eagle-import:1X01")
      (libsource (lib "eagle-import") (part "1X01"))
    )
    (comp (ref "JP691")
      (value "1X01")
      (footprint "eagle-import:1X01")
      (libsource (lib "eagle-import") (part "1X01"))
    )
    (comp (ref "JP692")
      (value "1X01")
      (footprint "eagle-import:1X01")
      (libsource (lib "eagle-import") (part "1X01"))
    )
    (comp (ref "JP693")
      (value "1X01")
      (footprint "eagle-import:1X01")
      (libsource (lib "eagle-import") (part "1X01"))
    )
    (comp (ref "JP694")
      (value "1X01")
      (footprint "eagle-import:1X01")
      (libsource (lib "eagle-import") (part "1X01"))
    )
    (comp (ref "JP695")
      (value "1X01")
      (footprint "eagle-import:1X01")
      (libsource (lib "eagle-import") (part "1X01"))
    )
    (comp (ref "JP696")
      (value "1X01")
      (footprint "eagle-import:1X01")
      (libsource (lib "eagle-import") (part "1X01"))
    )
    (comp (ref "JP697")
      (value "1X01")
      (footprint "eagle-import:1X01")
      (libsource (lib "eagle-import") (part "1X01"))
    )
    (comp (ref "JP698")
      (value "1X01")
      (footprint "eagle-import:1X01")
      (libsource (lib "eagle-import") (part "1X01"))
    )
    (comp (ref "JP699")
      (value "1X01")
      (footprint "eagle-import:1X01")
      (libsource (lib "eagle-import") (part "1X01"))
    )
    (comp (ref "JP700")
      (value "1X01")
      (footprint "eagle-import:1X01")
      (libsource (lib "eagle-import") (part "1X01"))
    )
    (comp (ref "JP701")
      (value "1X01")
      (footprint "eagle-import:1X01")
      (libsource (lib "eagle-import") (part "1X01"))
    )
    (comp (ref "JP702")
      (value "1X01")
      (footprint "eagle-import:1X01")
      (libsource (lib "eagle-import") (part "1X01"))
    )
    (comp (ref "JP703")
      (value "1X01")
      (footprint "eagle-import:1X01")
      (libsource (lib "eagle-import") (part "1X01"))
    )
    (comp (ref "JP704")
      (value "1X01")
      (footprint "eagle-import:1X01")
      (libsource (lib "eagle-import") (part "1X01"))
    )
    (comp (ref "JP705")
      (value "1X01")
      (footprint "eagle-import:1X01")
      (libsource (lib "eagle-import") (part "1X01"))
    )
    (comp (ref "JP706")
      (value "1X01")
      (footprint "eagle-import:1X01")
      (libsource (lib "eagle-import") (part "1X01"))
    )
    (comp (ref "JP707")
      (value "1X01")
      (footprint "eagle-import:1X01")
      (libsource (lib "eagle-import") (part "1X01"))
    )
    (comp (ref "JP708")
      (value "1X01")
      (footprint "eagle-import:1X01")
      (libsource (lib "eagle-import") (part "1X01"))
    )
    (comp (ref "JP709")
      (value "1X01")
      (footprint "eagle-import:1X01")
      (libsource (lib "eagle-import") (part "1X01"))
    )
    (comp (ref "JP710")
      (value "1X01")
      (footprint "eagle-import:1X01")
      (libsource (lib "eagle-import") (part "1X01"))
    )
    (comp (ref "JP711")
      (value "1X01")
      (footprint "eagle-import:1X01")
      (libsource (lib "eagle-import") (part "1X01"))
    )
    (comp (ref "JP712")
      (value "1X01")
      (footprint "eagle-import:1X01")
      (libsource (lib "eagle-import") (part "1X01"))
    )
    (comp (ref "JP713")
      (value "1X01")
      (footprint "eagle-import:1X01")
      (libsource (lib "eagle-import") (part "1X01"))
    )
    (comp (ref "JP714")
      (value "1X01")
      (footprint "eagle-import:1X01")
      (libsource (lib "eagle-import") (part "1X01"))
    )
    (comp (ref "JP715")
      (value "1X01")
      (footprint "eagle-import:1X01")
      (libsource (lib "eagle-import") (part "1X01"))
    )
    (comp (ref "JP716")
      (value "1X01")
      (footprint "eagle-import:1X01")
      (libsource (lib "eagle-import") (part "1X01"))
    )
    (comp (ref "JP717")
      (value "1X01")
      (footprint "eagle-import:1X01")
      (libsource (lib "eagle-import") (part "1X01"))
    )
    (comp (ref "JP718")
      (value "1X01")
      (footprint "eagle-import:1X01")
      (libsource (lib "eagle-import") (part "1X01"))
    )
    (comp (ref "JP719")
      (value "1X01")
      (footprint "eagle-import:1X01")
      (libsource (lib "eagle-import") (part "1X01"))
    )
    (comp (ref "JP720")
      (value "1X01")
      (footprint "eagle-import:1X01")
      (libsource (lib "eagle-import") (part "1X01"))
    )
    (comp (ref "JP721")
      (value "1X01")
      (footprint "eagle-import:1X01")
      (libsource (lib "eagle-import") (part "1X01"))
    )
    (comp (ref "JP722")
      (value "1X01")
      (footprint "eagle-import:1X01")
      (libsource (lib "eagle-import") (part "1X01"))
    )
    (comp (ref "JP723")
      (value "1X01")
      (footprint "eagle-import:1X01")
      (libsource (lib "eagle-import") (part "1X01"))
    )
    (comp (ref "JP724")
      (value "1X01")
      (footprint "eagle-import:1X01")
      (libsource (lib "eagle-import") (part "1X01"))
    )
    (comp (ref "JP725")
      (value "1X01")
      (footprint "eagle-import:1X01")
      (libsource (lib "eagle-import") (part "1X01"))
    )
    (comp (ref "JP726")
      (value "1X01")
      (footprint "eagle-import:1X01")
      (libsource (lib "eagle-import") (part "1X01"))
    )
    (comp (ref "JP727")
      (value "1X01")
      (footprint "eagle-import:1X01")
      (libsource (lib "eagle-import") (part "1X01"))
    )
    (comp (ref "JP728")
      (value "1X01")
      (footprint "eagle-import:1X01")
      (libsource (lib "eagle-import") (part "1X01"))
    )
    (comp (ref "JP729")
      (value "1X01")
      (footprint "eagle-import:1X01")
      (libsource (lib "eagle-import") (part "1X01"))
    )
    (comp (ref "JP730")
      (value "1X01")
      (footprint "eagle-import:1X01")
      (libsource (lib "eagle-import") (part "1X01"))
    )
    (comp (ref "JP731")
      (value "1X01")
      (footprint "eagle-import:1X01")
      (libsource (lib "eagle-import") (part "1X01"))
    )
    (comp (ref "JP732")
      (value "1X01")
      (footprint "eagle-import:1X01")
      (libsource (lib "eagle-import") (part "1X01"))
    )
    (comp (ref "JP733")
      (value "1X01")
      (footprint "eagle-import:1X01")
      (libsource (lib "eagle-import") (part "1X01"))
    )
    (comp (ref "JP734")
      (value "1X01")
      (footprint "eagle-import:1X01")
      (libsource (lib "eagle-import") (part "1X01"))
    )
    (comp (ref "JP735")
      (value "1X01")
      (footprint "eagle-import:1X01")
      (libsource (lib "eagle-import") (part "1X01"))
    )
    (comp (ref "JP736")
      (value "1X01")
      (footprint "eagle-import:1X01")
      (libsource (lib "eagle-import") (part "1X01"))
    )
    (comp (ref "JP737")
      (value "1X01")
      (footprint "eagle-import:1X01")
      (libsource (lib "eagle-import") (part "1X01"))
    )
    (comp (ref "JP738")
      (value "1X01")
      (footprint "eagle-import:1X01")
      (libsource (lib "eagle-import") (part "1X01"))
    )
    (comp (ref "JP739")
      (value "1X01")
      (footprint "eagle-import:1X01")
      (libsource (lib "eagle-import") (part "1X01"))
    )
    (comp (ref "JP740")
      (value "1X01")
      (footprint "eagle-import:1X01")
      (libsource (lib "eagle-import") (part "1X01"))
    )
    (comp (ref "JP741")
      (value "1X01")
      (footprint "eagle-import:1X01")
      (libsource (lib "eagle-import") (part "1X01"))
    )
    (comp (ref "JP742")
      (value "1X01")
      (footprint "eagle-import:1X01")
      (libsource (lib "eagle-import") (part "1X01"))
    )
    (comp (ref "JP743")
      (value "1X01")
      (footprint "eagle-import:1X01")
      (libsource (lib "eagle-import") (part "1X01"))
    )
    (comp (ref "JP744")
      (value "1X01")
      (footprint "eagle-import:1X01")
      (libsource (lib "eagle-import") (part "1X01"))
    )
    (comp (ref "JP745")
      (value "1X01")
      (footprint "eagle-import:1X01")
      (libsource (lib "eagle-import") (part "1X01"))
    )
    (comp (ref "JP746")
      (value "1X01")
      (footprint "eagle-import:1X01")
      (libsource (lib "eagle-import") (part "1X01"))
    )
    (comp (ref "JP747")
      (value "1X01")
      (footprint "eagle-import:1X01")
      (libsource (lib "eagle-import") (part "1X01"))
    )
    (comp (ref "JP748")
      (value "1X01")
      (footprint "eagle-import:1X01")
      (libsource (lib "eagle-import") (part "1X01"))
    )
    (comp (ref "JP749")
      (value "1X01")
      (footprint "eagle-import:1X01")
      (libsource (lib "eagle-import") (part "1X01"))
    )
    (comp (ref "JP750")
      (value "1X01")
      (footprint "eagle-import:1X01")
      (libsource (lib "eagle-import") (part "1X01"))
    )
    (comp (ref "JP751")
      (value "1X01")
      (footprint "eagle-import:1X01")
      (libsource (lib "eagle-import") (part "1X01"))
    )
    (comp (ref "JP752")
      (value "1X01")
      (footprint "eagle-import:1X01")
      (libsource (lib "eagle-import") (part "1X01"))
    )
    (comp (ref "JP753")
      (value "1X01")
      (footprint "eagle-import:1X01")
      (libsource (lib "eagle-import") (part "1X01"))
    )
    (comp (ref "JP754")
      (value "1X01")
      (footprint "eagle-import:1X01")
      (libsource (lib "eagle-import") (part "1X01"))
    )
    (comp (ref "JP755")
      (value "1X01")
      (footprint "eagle-import:1X01")
      (libsource (lib "eagle-import") (part "1X01"))
    )
    (comp (ref "JP756")
      (value "1X01")
      (footprint "eagle-import:1X01")
      (libsource (lib "eagle-import") (part "1X01"))
    )
    (comp (ref "JP757")
      (value "1X01")
      (footprint "eagle-import:1X01")
      (libsource (lib "eagle-import") (part "1X01"))
    )
    (comp (ref "JP758")
      (value "1X01")
      (footprint "eagle-import:1X01")
      (libsource (lib "eagle-import") (part "1X01"))
    )
    (comp (ref "JP759")
      (value "1X01")
      (footprint "eagle-import:1X01")
      (libsource (lib "eagle-import") (part "1X01"))
    )
    (comp (ref "JP760")
      (value "1X01")
      (footprint "eagle-import:1X01")
      (libsource (lib "eagle-import") (part "1X01"))
    )
    (comp (ref "JP761")
      (value "1X01")
      (footprint "eagle-import:1X01")
      (libsource (lib "eagle-import") (part "1X01"))
    )
    (comp (ref "JP762")
      (value "1X01")
      (footprint "eagle-import:1X01")
      (libsource (lib "eagle-import") (part "1X01"))
    )
    (comp (ref "JP763")
      (value "1X01")
      (footprint "eagle-import:1X01")
      (libsource (lib "eagle-import") (part "1X01"))
    )
    (comp (ref "JP764")
      (value "1X01")
      (footprint "eagle-import:1X01")
      (libsource (lib "eagle-import") (part "1X01"))
    )
    (comp (ref "JP765")
      (value "1X01")
      (footprint "eagle-import:1X01")
      (libsource (lib "eagle-import") (part "1X01"))
    )
    (comp (ref "JP766")
      (value "1X01")
      (footprint "eagle-import:1X01")
      (libsource (lib "eagle-import") (part "1X01"))
    )
    (comp (ref "JP767")
      (value "1X01")
      (footprint "eagle-import:1X01")
      (libsource (lib "eagle-import") (part "1X01"))
    )
    (comp (ref "JP768")
      (value "1X01")
      (footprint "eagle-import:1X01")
      (libsource (lib "eagle-import") (part "1X01"))
    )
    (comp (ref "JP769")
      (value "1X01")
      (footprint "eagle-import:1X01")
      (libsource (lib "eagle-import") (part "1X01"))
    )
    (comp (ref "JP770")
      (value "1X01")
      (footprint "eagle-import:1X01")
      (libsource (lib "eagle-import") (part "1X01"))
    )
    (comp (ref "JP771")
      (value "1X01")
      (footprint "eagle-import:1X01")
      (libsource (lib "eagle-import") (part "1X01"))
    )
    (comp (ref "JP772")
      (value "1X01")
      (footprint "eagle-import:1X01")
      (libsource (lib "eagle-import") (part "1X01"))
    )
    (comp (ref "JP773")
      (value "1X01")
      (footprint "eagle-import:1X01")
      (libsource (lib "eagle-import") (part "1X01"))
    )
    (comp (ref "JP774")
      (value "1X01")
      (footprint "eagle-import:1X01")
      (libsource (lib "eagle-import") (part "1X01"))
    )
    (comp (ref "JP775")
      (value "1X01")
      (footprint "eagle-import:1X01")
      (libsource (lib "eagle-import") (part "1X01"))
    )
    (comp (ref "JP776")
      (value "1X01")
      (footprint "eagle-import:1X01")
      (libsource (lib "eagle-import") (part "1X01"))
    )
    (comp (ref "JP777")
      (value "1X01")
      (footprint "eagle-import:1X01")
      (libsource (lib "eagle-import") (part "1X01"))
    )
    (comp (ref "JP778")
      (value "1X01")
      (footprint "eagle-import:1X01")
      (libsource (lib "eagle-import") (part "1X01"))
    )
    (comp (ref "JP779")
      (value "1X01")
      (footprint "eagle-import:1X01")
      (libsource (lib "eagle-import") (part "1X01"))
    )
    (comp (ref "JP780")
      (value "1X01")
      (footprint "eagle-import:1X01")
      (libsource (lib "eagle-import") (part "1X01"))
    )
    (comp (ref "JP781")
      (value "1X01")
      (footprint "eagle-import:1X01")
      (libsource (lib "eagle-import") (part "1X01"))
    )
    (comp (ref "JP782")
      (value "1X01")
      (footprint "eagle-import:1X01")
      (libsource (lib "eagle-import") (part "1X01"))
    )
    (comp (ref "JP783")
      (value "1X01")
      (footprint "eagle-import:1X01")
      (libsource (lib "eagle-import") (part "1X01"))
    )
    (comp (ref "JP785")
      (value "1X01")
      (footprint "eagle-import:1X01")
      (libsource (lib "eagle-import") (part "1X01"))
    )
    (comp (ref "JP786")
      (value "1X01")
      (footprint "eagle-import:1X01")
      (libsource (lib "eagle-import") (part "1X01"))
    )
    (comp (ref "JP787")
      (value "1X01")
      (footprint "eagle-import:1X01")
      (libsource (lib "eagle-import") (part "1X01"))
    )
    (comp (ref "JP788")
      (value "1X01-WIDE")
      (footprint "eagle-import:1X01-WIDE")
      (libsource (lib "eagle-import") (part "1X01-WIDE"))
    )
    (comp (ref "JP789")
      (value "1X01-WIDE")
      (footprint "eagle-import:1X01-WIDE")
      (libsource (lib "eagle-import") (part "1X01-WIDE"))
    )
    (comp (ref "JP790")
      (value "1X01-WIDE")
      (footprint "eagle-import:1X01-WIDE")
      (libsource (lib "eagle-import") (part "1X01-WIDE"))
    )
    (comp (ref "JP791")
      (value "1X01")
      (footprint "eagle-import:1X01")
      (libsource (lib "eagle-import") (part "1X01"))
    )
    (comp (ref "JP792")
      (value "1X01")
      (footprint "eagle-import:1X01")
      (libsource (lib "eagle-import") (part "1X01"))
    )
    (comp (ref "JP793")
      (value "1X01")
      (footprint "eagle-import:1X01")
      (libsource (lib "eagle-import") (part "1X01"))
    )
    (comp (ref "JP794")
      (value "1X01")
      (footprint "eagle-import:1X01")
      (libsource (lib "eagle-import") (part "1X01"))
    )
    (comp (ref "JP795")
      (value "1X01")
      (footprint "eagle-import:1X01")
      (libsource (lib "eagle-import") (part "1X01"))
    )
    (comp (ref "JP796")
      (value "1X01")
      (footprint "eagle-import:1X01")
      (libsource (lib "eagle-import") (part "1X01"))
    )
    (comp (ref "JP797")
      (value "1X01")
      (footprint "eagle-import:1X01")
      (libsource (lib "eagle-import") (part "1X01"))
    )
    (comp (ref "JP798")
      (value "1X01")
      (footprint "eagle-import:1X01")
      (libsource (lib "eagle-import") (part "1X01"))
    )
    (comp (ref "JP799")
      (value "1X01")
      (footprint "eagle-import:1X01")
      (libsource (lib "eagle-import") (part "1X01"))
    )
    (comp (ref "JP800")
      (value "1X01")
      (footprint "eagle-import:1X01")
      (libsource (lib "eagle-import") (part "1X01"))
    )
    (comp (ref "JP801")
      (value "1X01")
      (footprint "eagle-import:1X01")
      (libsource (lib "eagle-import") (part "1X01"))
    )
    (comp (ref "JP802")
      (value "1X01")
      (footprint "eagle-import:1X01")
      (libsource (lib "eagle-import") (part "1X01"))
    )
    (comp (ref "JP803")
      (value "1X01")
      (footprint "eagle-import:1X01")
      (libsource (lib "eagle-import") (part "1X01"))
    )
    (comp (ref "JP804")
      (value "1X01")
      (footprint "eagle-import:1X01")
      (libsource (lib "eagle-import") (part "1X01"))
    )
    (comp (ref "JP805")
      (value "1X01")
      (footprint "eagle-import:1X01")
      (libsource (lib "eagle-import") (part "1X01"))
    )
    (comp (ref "JP806")
      (value "1X01")
      (footprint "eagle-import:1X01")
      (libsource (lib "eagle-import") (part "1X01"))
    )
    (comp (ref "JP807")
      (value "1X01")
      (footprint "eagle-import:1X01")
      (libsource (lib "eagle-import") (part "1X01"))
    )
    (comp (ref "JP808")
      (value "1X01")
      (footprint "eagle-import:1X01")
      (libsource (lib "eagle-import") (part "1X01"))
    )
    (comp (ref "JP809")
      (value "1X01")
      (footprint "eagle-import:1X01")
      (libsource (lib "eagle-import") (part "1X01"))
    )
    (comp (ref "JP810")
      (value "1X01")
      (footprint "eagle-import:1X01")
      (libsource (lib "eagle-import") (part "1X01"))
    )
    (comp (ref "JP811")
      (value "1X01")
      (footprint "eagle-import:1X01")
      (libsource (lib "eagle-import") (part "1X01"))
    )
    (comp (ref "JP812")
      (value "1X01")
      (footprint "eagle-import:1X01")
      (libsource (lib "eagle-import") (part "1X01"))
    )
    (comp (ref "JP813")
      (value "1X01")
      (footprint "eagle-import:1X01")
      (libsource (lib "eagle-import") (part "1X01"))
    )
    (comp (ref "JP814")
      (value "1X01")
      (footprint "eagle-import:1X01")
      (libsource (lib "eagle-import") (part "1X01"))
    )
    (comp (ref "JP815")
      (value "1X01")
      (footprint "eagle-import:1X01")
      (libsource (lib "eagle-import") (part "1X01"))
    )
    (comp (ref "JP816")
      (value "1X01")
      (footprint "eagle-import:1X01")
      (libsource (lib "eagle-import") (part "1X01"))
    )
    (comp (ref "JP817")
      (value "1X01")
      (footprint "eagle-import:1X01")
      (libsource (lib "eagle-import") (part "1X01"))
    )
    (comp (ref "JP818")
      (value "1X01")
      (footprint "eagle-import:1X01")
      (libsource (lib "eagle-import") (part "1X01"))
    )
    (comp (ref "JP819")
      (value "1X01")
      (footprint "eagle-import:1X01")
      (libsource (lib "eagle-import") (part "1X01"))
    )
    (comp (ref "JP820")
      (value "1X01")
      (footprint "eagle-import:1X01")
      (libsource (lib "eagle-import") (part "1X01"))
    )
    (comp (ref "JP821")
      (value "1X01")
      (footprint "eagle-import:1X01")
      (libsource (lib "eagle-import") (part "1X01"))
    )
    (comp (ref "JP822")
      (value "1X01")
      (footprint "eagle-import:1X01")
      (libsource (lib "eagle-import") (part "1X01"))
    )
    (comp (ref "JP823")
      (value "1X01")
      (footprint "eagle-import:1X01")
      (libsource (lib "eagle-import") (part "1X01"))
    )
    (comp (ref "JP824")
      (value "1X01")
      (footprint "eagle-import:1X01")
      (libsource (lib "eagle-import") (part "1X01"))
    )
    (comp (ref "JP825")
      (value "1X01")
      (footprint "eagle-import:1X01")
      (libsource (lib "eagle-import") (part "1X01"))
    )
    (comp (ref "JP826")
      (value "1X01")
      (footprint "eagle-import:1X01")
      (libsource (lib "eagle-import") (part "1X01"))
    )
    (comp (ref "JP827")
      (value "1X01")
      (footprint "eagle-import:1X01")
      (libsource (lib "eagle-import") (part "1X01"))
    )
    (comp (ref "JP828")
      (value "1X01")
      (footprint "eagle-import:1X01")
      (libsource (lib "eagle-import") (part "1X01"))
    )
    (comp (ref "JP829")
      (value "1X01")
      (footprint "eagle-import:1X01")
      (libsource (lib "eagle-import") (part "1X01"))
    )
    (comp (ref "JP830")
      (value "1X01")
      (footprint "eagle-import:1X01")
      (libsource (lib "eagle-import") (part "1X01"))
    )
    (comp (ref "JP831")
      (value "1X01")
      (footprint "eagle-import:1X01")
      (libsource (lib "eagle-import") (part "1X01"))
    )
    (comp (ref "JP832")
      (value "1X01")
      (footprint "eagle-import:1X01")
      (libsource (lib "eagle-import") (part "1X01"))
    )
    (comp (ref "JP833")
      (value "1X01")
      (footprint "eagle-import:1X01")
      (libsource (lib "eagle-import") (part "1X01"))
    )
    (comp (ref "JP834")
      (value "1X01")
      (footprint "eagle-import:1X01")
      (libsource (lib "eagle-import") (part "1X01"))
    )
    (comp (ref "JP835")
      (value "1X01")
      (footprint "eagle-import:1X01")
      (libsource (lib "eagle-import") (part "1X01"))
    )
    (comp (ref "JP836")
      (value "1X01")
      (footprint "eagle-import:1X01")
      (libsource (lib "eagle-import") (part "1X01"))
    )
    (comp (ref "JP837")
      (value "1X01")
      (footprint "eagle-import:1X01")
      (libsource (lib "eagle-import") (part "1X01"))
    )
    (comp (ref "JP838")
      (value "1X01")
      (footprint "eagle-import:1X01")
      (libsource (lib "eagle-import") (part "1X01"))
    )
    (comp (ref "JP839")
      (value "1X01")
      (footprint "eagle-import:1X01")
      (libsource (lib "eagle-import") (part "1X01"))
    )
    (comp (ref "JP840")
      (value "1X01")
      (footprint "eagle-import:1X01")
      (libsource (lib "eagle-import") (part "1X01"))
    )
    (comp (ref "JP841")
      (value "1X01")
      (footprint "eagle-import:1X01")
      (libsource (lib "eagle-import") (part "1X01"))
    )
    (comp (ref "JP842")
      (value "1X01")
      (footprint "eagle-import:1X01")
      (libsource (lib "eagle-import") (part "1X01"))
    )
    (comp (ref "JP843")
      (value "1X01")
      (footprint "eagle-import:1X01")
      (libsource (lib "eagle-import") (part "1X01"))
    )
    (comp (ref "JP844")
      (value "1X01")
      (footprint "eagle-import:1X01")
      (libsource (lib "eagle-import") (part "1X01"))
    )
    (comp (ref "JP845")
      (value "1X01")
      (footprint "eagle-import:1X01")
      (libsource (lib "eagle-import") (part "1X01"))
    )
    (comp (ref "JP846")
      (value "1X01")
      (footprint "eagle-import:1X01")
      (libsource (lib "eagle-import") (part "1X01"))
    )
    (comp (ref "JP847")
      (value "1X01")
      (footprint "eagle-import:1X01")
      (libsource (lib "eagle-import") (part "1X01"))
    )
    (comp (ref "JP848")
      (value "1X01")
      (footprint "eagle-import:1X01")
      (libsource (lib "eagle-import") (part "1X01"))
    )
    (comp (ref "JP849")
      (value "1X01")
      (footprint "eagle-import:1X01")
      (libsource (lib "eagle-import") (part "1X01"))
    )
    (comp (ref "JP850")
      (value "1X01")
      (footprint "eagle-import:1X01")
      (libsource (lib "eagle-import") (part "1X01"))
    )
    (comp (ref "JP851")
      (value "1X01")
      (footprint "eagle-import:1X01")
      (libsource (lib "eagle-import") (part "1X01"))
    )
    (comp (ref "JP852")
      (value "1X01")
      (footprint "eagle-import:1X01")
      (libsource (lib "eagle-import") (part "1X01"))
    )
    (comp (ref "JP853")
      (value "1X01")
      (footprint "eagle-import:1X01")
      (libsource (lib "eagle-import") (part "1X01"))
    )
    (comp (ref "JP854")
      (value "1X01")
      (footprint "eagle-import:1X01")
      (libsource (lib "eagle-import") (part "1X01"))
    )
    (comp (ref "JP855")
      (value "1X01")
      (footprint "eagle-import:1X01")
      (libsource (lib "eagle-import") (part "1X01"))
    )
    (comp (ref "JP856")
      (value "1X01")
      (footprint "eagle-import:1X01")
      (libsource (lib "eagle-import") (part "1X01"))
    )
    (comp (ref "JP857")
      (value "1X01")
      (footprint "eagle-import:1X01")
      (libsource (lib "eagle-import") (part "1X01"))
    )
    (comp (ref "JP858")
      (value "1X01")
      (footprint "eagle-import:1X01")
      (libsource (lib "eagle-import") (part "1X01"))
    )
    (comp (ref "JP859")
      (value "1X01")
      (footprint "eagle-import:1X01")
      (libsource (lib "eagle-import") (part "1X01"))
    )
    (comp (ref "JP860")
      (value "1X01")
      (footprint "eagle-import:1X01")
      (libsource (lib "eagle-import") (part "1X01"))
    )
    (comp (ref "JP861")
      (value "1X01")
      (footprint "eagle-import:1X01")
      (libsource (lib "eagle-import") (part "1X01"))
    )
    (comp (ref "JP862")
      (value "1X01")
      (footprint "eagle-import:1X01")
      (libsource (lib "eagle-import") (part "1X01"))
    )
    (comp (ref "JP863")
      (value "1X01")
      (footprint "eagle-import:1X01")
      (libsource (lib "eagle-import") (part "1X01"))
    )
    (comp (ref "JP864")
      (value "1X01")
      (footprint "eagle-import:1X01")
      (libsource (lib "eagle-import") (part "1X01"))
    )
    (comp (ref "JP865")
      (value "1X01")
      (footprint "eagle-import:1X01")
      (libsource (lib "eagle-import") (part "1X01"))
    )
    (comp (ref "JP866")
      (value "1X01")
      (footprint "eagle-import:1X01")
      (libsource (lib "eagle-import") (part "1X01"))
    )
    (comp (ref "JP867")
      (value "1X01")
      (footprint "eagle-import:1X01")
      (libsource (lib "eagle-import") (part "1X01"))
    )
    (comp (ref "JP868")
      (value "1X01")
      (footprint "eagle-import:1X01")
      (libsource (lib "eagle-import") (part "1X01"))
    )
    (comp (ref "JP869")
      (value "1X01")
      (footprint "eagle-import:1X01")
      (libsource (lib "eagle-import") (part "1X01"))
    )
    (comp (ref "JP870")
      (value "1X01")
      (footprint "eagle-import:1X01")
      (libsource (lib "eagle-import") (part "1X01"))
    )
    (comp (ref "JP871")
      (value "1X01")
      (footprint "eagle-import:1X01")
      (libsource (lib "eagle-import") (part "1X01"))
    )
    (comp (ref "JP872")
      (value "1X01")
      (footprint "eagle-import:1X01")
      (libsource (lib "eagle-import") (part "1X01"))
    )
    (comp (ref "JP873")
      (value "1X01")
      (footprint "eagle-import:1X01")
      (libsource (lib "eagle-import") (part "1X01"))
    )
    (comp (ref "JP874")
      (value "1X01")
      (footprint "eagle-import:1X01")
      (libsource (lib "eagle-import") (part "1X01"))
    )
    (comp (ref "JP875")
      (value "1X01")
      (footprint "eagle-import:1X01")
      (libsource (lib "eagle-import") (part "1X01"))
    )
    (comp (ref "JP876")
      (value "1X01")
      (footprint "eagle-import:1X01")
      (libsource (lib "eagle-import") (part "1X01"))
    )
    (comp (ref "JP877")
      (value "1X01")
      (footprint "eagle-import:1X01")
      (libsource (lib "eagle-import") (part "1X01"))
    )
    (comp (ref "JP878")
      (value "1X01")
      (footprint "eagle-import:1X01")
      (libsource (lib "eagle-import") (part "1X01"))
    )
    (comp (ref "JP879")
      (value "1X01")
      (footprint "eagle-import:1X01")
      (libsource (lib "eagle-import") (part "1X01"))
    )
    (comp (ref "JP880")
      (value "1X01")
      (footprint "eagle-import:1X01")
      (libsource (lib "eagle-import") (part "1X01"))
    )
    (comp (ref "JP881")
      (value "1X01")
      (footprint "eagle-import:1X01")
      (libsource (lib "eagle-import") (part "1X01"))
    )
    (comp (ref "JP882")
      (value "1X01")
      (footprint "eagle-import:1X01")
      (libsource (lib "eagle-import") (part "1X01"))
    )
    (comp (ref "JP883")
      (value "1X01")
      (footprint "eagle-import:1X01")
      (libsource (lib "eagle-import") (part "1X01"))
    )
    (comp (ref "JP884")
      (value "1X01")
      (footprint "eagle-import:1X01")
      (libsource (lib "eagle-import") (part "1X01"))
    )
    (comp (ref "JP885")
      (value "1X01")
      (footprint "eagle-import:1X01")
      (libsource (lib "eagle-import") (part "1X01"))
    )
    (comp (ref "JP886")
      (value "1X01")
      (footprint "eagle-import:1X01")
      (libsource (lib "eagle-import") (part "1X01"))
    )
    (comp (ref "JP887")
      (value "1X01")
      (footprint "eagle-import:1X01")
      (libsource (lib "eagle-import") (part "1X01"))
    )
    (comp (ref "JP888")
      (value "1X01")
      (footprint "eagle-import:1X01")
      (libsource (lib "eagle-import") (part "1X01"))
    )
    (comp (ref "JP889")
      (value "1X01")
      (footprint "eagle-import:1X01")
      (libsource (lib "eagle-import") (part "1X01"))
    )
    (comp (ref "JP890")
      (value "1X01")
      (footprint "eagle-import:1X01")
      (libsource (lib "eagle-import") (part "1X01"))
    )
    (comp (ref "JP891")
      (value "1X01")
      (footprint "eagle-import:1X01")
      (libsource (lib "eagle-import") (part "1X01"))
    )
    (comp (ref "JP892")
      (value "1X01")
      (footprint "eagle-import:1X01")
      (libsource (lib "eagle-import") (part "1X01"))
    )
    (comp (ref "JP893")
      (value "1X01")
      (footprint "eagle-import:1X01")
      (libsource (lib "eagle-import") (part "1X01"))
    )
    (comp (ref "JP894")
      (value "1X01")
      (footprint "eagle-import:1X01")
      (libsource (lib "eagle-import") (part "1X01"))
    )
    (comp (ref "JP895")
      (value "1X01")
      (footprint "eagle-import:1X01")
      (libsource (lib "eagle-import") (part "1X01"))
    )
    (comp (ref "JP896")
      (value "1X01")
      (footprint "eagle-import:1X01")
      (libsource (lib "eagle-import") (part "1X01"))
    )
    (comp (ref "JP897")
      (value "1X01")
      (footprint "eagle-import:1X01")
      (libsource (lib "eagle-import") (part "1X01"))
    )
    (comp (ref "JP898")
      (value "1X01")
      (footprint "eagle-import:1X01")
      (libsource (lib "eagle-import") (part "1X01"))
    )
    (comp (ref "JP899")
      (value "1X01")
      (footprint "eagle-import:1X01")
      (libsource (lib "eagle-import") (part "1X01"))
    )
    (comp (ref "JP900")
      (value "1X01")
      (footprint "eagle-import:1X01")
      (libsource (lib "eagle-import") (part "1X01"))
    )
    (comp (ref "JP901")
      (value "1X01")
      (footprint "eagle-import:1X01")
      (libsource (lib "eagle-import") (part "1X01"))
    )
    (comp (ref "JP902")
      (value "1X01")
      (footprint "eagle-import:1X01")
      (libsource (lib "eagle-import") (part "1X01"))
    )
    (comp (ref "POWER")
      (value "CONN_05X2SHD")
      (footprint "eagle-import:2X5-SHROUDED")
      (libsource (lib "eagle-import") (part "CONN_05X2SHD"))
    )
    (comp (ref "R1")
      (value "3RP/1610N")
      (footprint "eagle-import:3RP_1610N")
      (libsource (lib "eagle-import") (part "3RP/1610N"))
    )
    (comp (ref "R2")
      (value "3RP/1610N")
      (footprint "eagle-import:3RP_1610N")
      (libsource (lib "eagle-import") (part "3RP/1610N"))
    )
    (comp (ref "R3")
      (value "3RP/1610N")
      (footprint "eagle-import:3RP_1610N")
      (libsource (lib "eagle-import") (part "3RP/1610N"))
    )
    (comp (ref "R4")
      (value "3RP/1610N")
      (footprint "eagle-import:3RP_1610N")
      (libsource (lib "eagle-import") (part "3RP/1610N"))
    )
    (comp (ref "U$1")
      (value "RIGHTANGLE")
      (footprint "eagle-import:RIGHTANGLE")
      (libsource (lib "eagle-import") (part "RIGHTANGLE"))
    )
    (comp (ref "U$2")
      (value "RIGHTANGLE")
      (footprint "eagle-import:RIGHTANGLE")
      (libsource (lib "eagle-import") (part "RIGHTANGLE"))
    )
  )
  (nets
    (net (code "1") (name "+3V3") (class "Default")
      (node (ref "C5") (pin "1") (pinfunction "1_1") (pintype "passive"))
      (node (ref "IC2") (pin "GND") (pinfunction "OUT_GND") (pintype "passive"))
      (node (ref "JP345") (pin "1") (pinfunction "1_1") (pintype "passive"))
      (node (ref "JP779") (pin "1") (pinfunction "1_1") (pintype "passive"))
    )
    (net (code "2") (name "+5V") (class "Default")
      (node (ref "ARD2") (pin "12") (pinfunction "12_12") (pintype "passive"))
      (node (ref "C6") (pin "1") (pinfunction "1_1") (pintype "passive"))
      (node (ref "IC1") (pin "3") (pinfunction "VIN_3") (pintype "input"))
      (node (ref "IC3") (pin "3") (pinfunction "VO_3") (pintype "passive"))
      (node (ref "JP344") (pin "1") (pinfunction "1_1") (pintype "passive"))
      (node (ref "JP778") (pin "1") (pinfunction "1_1") (pintype "passive"))
    )
    (net (code "3") (name "+12V") (class "Default")
      (node (ref "C7") (pin "1") (pinfunction "1_1") (pintype "passive"))
      (node (ref "C8") (pin "+") (pinfunction "+_+") (pintype "passive"))
      (node (ref "IC2") (pin "OUT") (pinfunction "IN_OUT") (pintype "input"))
      (node (ref "IC3") (pin "1") (pinfunction "VI_1") (pintype "input"))
      (node (ref "JP114") (pin "1") (pinfunction "1_1") (pintype "passive"))
      (node (ref "JP115") (pin "1") (pinfunction "1_1") (pintype "passive"))
      (node (ref "JP117") (pin "1") (pinfunction "1_1") (pintype "passive"))
      (node (ref "JP118") (pin "1") (pinfunction "1_1") (pintype "passive"))
      (node (ref "JP119") (pin "1") (pinfunction "1_1") (pintype "passive"))
      (node (ref "JP120") (pin "1") (pinfunction "1_1") (pintype "passive"))
      (node (ref "JP121") (pin "1") (pinfunction "1_1") (pintype "passive"))
      (node (ref "JP122") (pin "1") (pinfunction "1_1") (pintype "passive"))
      (node (ref "JP123") (pin "1") (pinfunction "1_1") (pintype "passive"))
      (node (ref "JP124") (pin "1") (pinfunction "1_1") (pintype "passive"))
      (node (ref "JP125") (pin "1") (pinfunction "1_1") (pintype "passive"))
      (node (ref "JP126") (pin "1") (pinfunction "1_1") (pintype "passive"))
      (node (ref "JP127") (pin "1") (pinfunction "1_1") (pintype "passive"))
      (node (ref "JP128") (pin "1") (pinfunction "1_1") (pintype "passive"))
      (node (ref "JP129") (pin "1") (pinfunction "1_1") (pintype "passive"))
      (node (ref "JP130") (pin "1") (pinfunction "1_1") (pintype "passive"))
      (node (ref "JP131") (pin "1") (pinfunction "1_1") (pintype "passive"))
      (node (ref "JP132") (pin "1") (pinfunction "1_1") (pintype "passive"))
      (node (ref "JP133") (pin "1") (pinfunction "1_1") (pintype "passive"))
      (node (ref "JP134") (pin "1") (pinfunction "1_1") (pintype "passive"))
      (node (ref "JP135") (pin "1") (pinfunction "1_1") (pintype "passive"))
      (node (ref "JP136") (pin "1") (pinfunction "1_1") (pintype "passive"))
      (node (ref "JP137") (pin "1") (pinfunction "1_1") (pintype "passive"))
      (node (ref "JP138") (pin "1") (pinfunction "1_1") (pintype "passive"))
      (node (ref "JP139") (pin "1") (pinfunction "1_1") (pintype "passive"))
      (node (ref "JP140") (pin "1") (pinfunction "1_1") (pintype "passive"))
      (node (ref "JP141") (pin "1") (pinfunction "1_1") (pintype "passive"))
      (node (ref "JP142") (pin "1") (pinfunction "1_1") (pintype "passive"))
      (node (ref "JP143") (pin "1") (pinfunction "1_1") (pintype "passive"))
      (node (ref "JP144") (pin "1") (pinfunction "1_1") (pintype "passive"))
      (node (ref "JP145") (pin "1") (pinfunction "1_1") (pintype "passive"))
      (node (ref "JP146") (pin "1") (pinfunction "1_1") (pintype "passive"))
      (node (ref "JP147") (pin "1") (pinfunction "1_1") (pintype "passive"))
      (node (ref "JP148") (pin "1") (pinfunction "1_1") (pintype "passive"))
      (node (ref "JP149") (pin "1") (pinfunction "1_1") (pintype "passive"))
      (node (ref "JP150") (pin "1") (pinfunction "1_1") (pintype "passive"))
      (node (ref "JP151") (pin "1") (pinfunction "1_1") (pintype "passive"))
      (node (ref "JP152") (pin "1") (pinfunction "1_1") (pintype "passive"))
      (node (ref "POWER") (pin "10") (pinfunction "10_10") (pintype "passive"))
      (node (ref "POWER") (pin "9") (pinfunction "9_9") (pintype "passive"))
    )
    (net (code "4") (name "-12V") (class "Default")
      (node (ref "C7") (pin "2") (pinfunction "2_2") (pintype "passive"))
      (node (ref "C9") (pin "-") (pinfunction "-_-") (pintype "passive"))
      (node (ref "JP267") (pin "1") (pinfunction "1_1") (pintype "passive"))
      (node (ref "JP268") (pin "1") (pinfunction "1_1") (pintype "passive"))
      (node (ref "JP269") (pin "1") (pinfunction "1_1") (pintype "passive"))
      (node (ref "JP270") (pin "1") (pinfunction "1_1") (pintype "passive"))
      (node (ref "JP271") (pin "1") (pinfunction "1_1") (pintype "passive"))
      (node (ref "JP272") (pin "1") (pinfunction "1_1") (pintype "passive"))
      (node (ref "JP273") (pin "1") (pinfunction "1_1") (pintype "passive"))
      (node (ref "JP274") (pin "1") (pinfunction "1_1") (pintype "passive"))
      (node (ref "JP275") (pin "1") (pinfunction "1_1") (pintype "passive"))
      (node (ref "JP276") (pin "1") (pinfunction "1_1") (pintype "passive"))
      (node (ref "JP277") (pin "1") (pinfunction "1_1") (pintype "passive"))
      (node (ref "JP278") (pin "1") (pinfunction "1_1") (pintype "passive"))
      (node (ref "JP279") (pin "1") (pinfunction "1_1") (pintype "passive"))
      (node (ref "JP280") (pin "1") (pinfunction "1_1") (pintype "passive"))
      (node (ref "JP281") (pin "1") (pinfunction "1_1") (pintype "passive"))
      (node (ref "JP282") (pin "1") (pinfunction "1_1") (pintype "passive"))
      (node (ref "JP283") (pin "1") (pinfunction "1_1") (pintype "passive"))
      (node (ref "JP284") (pin "1") (pinfunction "1_1") (pintype "passive"))
      (node (ref "JP285") (pin "1") (pinfunction "1_1") (pintype "passive"))
      (node (ref "JP286") (pin "1") (pinfunction "1_1") (pintype "passive"))
      (node (ref "JP287") (pin "1") (pinfunction "1_1") (pintype "passive"))
      (node (ref "JP288") (pin "1") (pinfunction "1_1") (pintype "passive"))
      (node (ref "JP289") (pin "1") (pinfunction "1_1") (pintype "passive"))
      (node (ref "JP290") (pin "1") (pinfunction "1_1") (pintype "passive"))
      (node (ref "JP291") (pin "1") (pinfunction "1_1") (pintype "passive"))
      (node (ref "JP292") (pin "1") (pinfunction "1_1") (pintype "passive"))
      (node (ref "JP293") (pin "1") (pinfunction "1_1") (pintype "passive"))
      (node (ref "JP294") (pin "1") (pinfunction "1_1") (pintype "passive"))
      (node (ref "JP295") (pin "1") (pinfunction "1_1") (pintype "passive"))
      (node (ref "JP296") (pin "1") (pinfunction "1_1") (pintype "passive"))
      (node (ref "JP297") (pin "1") (pinfunction "1_1") (pintype "passive"))
      (node (ref "JP298") (pin "1") (pinfunction "1_1") (pintype "passive"))
      (node (ref "JP299") (pin "1") (pinfunction "1_1") (pintype "passive"))
      (node (ref "JP300") (pin "1") (pinfunction "1_1") (pintype "passive"))
      (node (ref "JP301") (pin "1") (pinfunction "1_1") (pintype "passive"))
      (node (ref "JP302") (pin "1") (pinfunction "1_1") (pintype "passive"))
      (node (ref "JP303") (pin "1") (pinfunction "1_1") (pintype "passive"))
      (node (ref "JP304") (pin "1") (pinfunction "1_1") (pintype "passive"))
      (node (ref "POWER") (pin "1") (pinfunction "1_1") (pintype "passive"))
      (node (ref "POWER") (pin "2") (pinfunction "2_2") (pintype "passive"))
    )
    (net (code "5") (name "/N$16") (class "Default")
      (node (ref "GATE1") (pin "2") (pinfunction "2_2") (pintype "passive"))
      (node (ref "JP725") (pin "1") (pinfunction "1_1") (pintype "passive"))
      (node (ref "JP733") (pin "1") (pinfunction "1_1") (pintype "passive"))
      (node (ref "U$2") (pin "P$2") (pinfunction "1_P$2") (pintype "passive"))
    )
    (net (code "6") (name "/VREF") (class "Default")
      (node (ref "ARD2") (pin "3") (pinfunction "3_3") (pintype "passive"))
      (node (ref "C13") (pin "+") (pinfunction "+_+") (pintype "passive"))
      (node (ref "IC1") (pin "2") (pinfunction "VO_2") (pintype "output"))
      (node (ref "JP781") (pin "1") (pinfunction "1_1") (pintype "passive"))
      (node (ref "JP782") (pin "1") (pinfunction "1_1") (pintype "passive"))
      (node (ref "JP783") (pin "1") (pinfunction "1_1") (pintype "passive"))
    )
    (net (code "7") (name "GND") (class "Default")
      (node (ref "ARD1") (pin "12") (pinfunction "12_12") (pintype "passive"))
      (node (ref "ARD2") (pin "14") (pinfunction "14_14") (pintype "passive"))
      (node (ref "C13") (pin "-") (pinfunction "-_-") (pintype "passive"))
      (node (ref "C5") (pin "2") (pinfunction "2_2") (pintype "passive"))
      (node (ref "C6") (pin "2") (pinfunction "2_2") (pintype "passive"))
      (node (ref "C8") (pin "-") (pinfunction "-_-") (pintype "passive"))
      (node (ref "C9") (pin "+") (pinfunction "+_+") (pintype "passive"))
      (node (ref "GATE1") (pin "1") (pinfunction "1_1") (pintype "passive"))
      (node (ref "GATE2") (pin "1") (pinfunction "1_1") (pintype "passive"))
      (node (ref "IC1") (pin "1") (pinfunction "GND_1") (pintype "passive"))
      (node (ref "IC2") (pin "IN") (pinfunction "GND_IN") (pintype "input"))
      (node (ref "IC3") (pin "2") (pinfunction "GND_2") (pintype "passive"))
      (node (ref "JP154") (pin "1") (pinfunction "1_1") (pintype "passive"))
      (node (ref "JP155") (pin "1") (pinfunction "1_1") (pintype "passive"))
      (node (ref "JP156") (pin "1") (pinfunction "1_1") (pintype "passive"))
      (node (ref "JP157") (pin "1") (pinfunction "1_1") (pintype "passive"))
      (node (ref "JP158") (pin "1") (pinfunction "1_1") (pintype "passive"))
      (node (ref "JP159") (pin "1") (pinfunction "1_1") (pintype "passive"))
      (node (ref "JP160") (pin "1") (pinfunction "1_1") (pintype "passive"))
      (node (ref "JP161") (pin "1") (pinfunction "1_1") (pintype "passive"))
      (node (ref "JP162") (pin "1") (pinfunction "1_1") (pintype "passive"))
      (node (ref "JP163") (pin "1") (pinfunction "1_1") (pintype "passive"))
      (node (ref "JP164") (pin "1") (pinfunction "1_1") (pintype "passive"))
      (node (ref "JP165") (pin "1") (pinfunction "1_1") (pintype "passive"))
      (node (ref "JP166") (pin "1") (pinfunction "1_1") (pintype "passive"))
      (node (ref "JP167") (pin "1") (pinfunction "1_1") (pintype "passive"))
      (node (ref "JP168") (pin "1") (pinfunction "1_1") (pintype "passive"))
      (node (ref "JP169") (pin "1") (pinfunction "1_1") (pintype "passive"))
      (node (ref "JP170") (pin "1") (pinfunction "1_1") (pintype "passive"))
      (node (ref "JP171") (pin "1") (pinfunction "1_1") (pintype "passive"))
      (node (ref "JP172") (pin "1") (pinfunction "1_1") (pintype "passive"))
      (node (ref "JP173") (pin "1") (pinfunction "1_1") (pintype "passive"))
      (node (ref "JP174") (pin "1") (pinfunction "1_1") (pintype "passive"))
      (node (ref "JP175") (pin "1") (pinfunction "1_1") (pintype "passive"))
      (node (ref "JP176") (pin "1") (pinfunction "1_1") (pintype "passive"))
      (node (ref "JP177") (pin "1") (pinfunction "1_1") (pintype "passive"))
      (node (ref "JP178") (pin "1") (pinfunction "1_1") (pintype "passive"))
      (node (ref "JP179") (pin "1") (pinfunction "1_1") (pintype "passive"))
      (node (ref "JP180") (pin "1") (pinfunction "1_1") (pintype "passive"))
      (node (ref "JP181") (pin "1") (pinfunction "1_1") (pintype "passive"))
      (node (ref "JP182") (pin "1") (pinfunction "1_1") (pintype "passive"))
      (node (ref "JP183") (pin "1") (pinfunction "1_1") (pintype "passive"))
      (node (ref "JP184") (pin "1") (pinfunction "1_1") (pintype "passive"))
      (node (ref "JP185") (pin "1") (pinfunction "1_1") (pintype "passive"))
      (node (ref "JP186") (pin "1") (pinfunction "1_1") (pintype "passive"))
      (node (ref "JP187") (pin "1") (pinfunction "1_1") (pintype "passive"))
      (node (ref "JP188") (pin "1") (pinfunction "1_1") (pintype "passive"))
      (node (ref "JP189") (pin "1") (pinfunction "1_1") (pintype "passive"))
      (node (ref "JP190") (pin "1") (pinfunction "1_1") (pintype "passive"))
      (node (ref "JP305") (pin "1") (pinfunction "1_1") (pintype "passive"))
      (node (ref "JP306") (pin "1") (pinfunction "1_1") (pintype "passive"))
      (node (ref "JP307") (pin "1") (pinfunction "1_1") (pintype "passive"))
      (node (ref "JP308") (pin "1") (pinfunction "1_1") (pintype "passive"))
      (node (ref "JP309") (pin "1") (pinfunction "1_1") (pintype "passive"))
      (node (ref "JP310") (pin "1") (pinfunction "1_1") (pintype "passive"))
      (node (ref "JP311") (pin "1") (pinfunction "1_1") (pintype "passive"))
      (node (ref "JP312") (pin "1") (pinfunction "1_1") (pintype "passive"))
      (node (ref "JP313") (pin "1") (pinfunction "1_1") (pintype "passive"))
      (node (ref "JP314") (pin "1") (pinfunction "1_1") (pintype "passive"))
      (node (ref "JP315") (pin "1") (pinfunction "1_1") (pintype "passive"))
      (node (ref "JP316") (pin "1") (pinfunction "1_1") (pintype "passive"))
      (node (ref "JP317") (pin "1") (pinfunction "1_1") (pintype "passive"))
      (node (ref "JP318") (pin "1") (pinfunction "1_1") (pintype "passive"))
      (node (ref "JP319") (pin "1") (pinfunction "1_1") (pintype "passive"))
      (node (ref "JP320") (pin "1") (pinfunction "1_1") (pintype "passive"))
      (node (ref "JP321") (pin "1") (pinfunction "1_1") (pintype "passive"))
      (node (ref "JP322") (pin "1") (pinfunction "1_1") (pintype "passive"))
      (node (ref "JP323") (pin "1") (pinfunction "1_1") (pintype "passive"))
      (node (ref "JP324") (pin "1") (pinfunction "1_1") (pintype "passive"))
      (node (ref "JP325") (pin "1") (pinfunction "1_1") (pintype "passive"))
      (node (ref "JP326") (pin "1") (pinfunction "1_1") (pintype "passive"))
      (node (ref "JP327") (pin "1") (pinfunction "1_1") (pintype "passive"))
      (node (ref "JP328") (pin "1") (pinfunction "1_1") (pintype "passive"))
      (node (ref "JP329") (pin "1") (pinfunction "1_1") (pintype "passive"))
      (node (ref "JP330") (pin "1") (pinfunction "1_1") (pintype "passive"))
      (node (ref "JP331") (pin "1") (pinfunction "1_1") (pintype "passive"))
      (node (ref "JP332") (pin "1") (pinfunction "1_1") (pintype "passive"))
      (node (ref "JP333") (pin "1") (pinfunction "1_1") (pintype "passive"))
      (node (ref "JP334") (pin "1") (pinfunction "1_1") (pintype "passive"))
      (node (ref "JP335") (pin "1") (pinfunction "1_1") (pintype "passive"))
      (node (ref "JP336") (pin "1") (pinfunction "1_1") (pintype "passive"))
      (node (ref "JP337") (pin "1") (pinfunction "1_1") (pintype "passive"))
      (node (ref "JP338") (pin "1") (pinfunction "1_1") (pintype "passive"))
      (node (ref "JP339") (pin "1") (pinfunction "1_1") (pintype "passive"))
      (node (ref "JP340") (pin "1") (pinfunction "1_1") (pintype "passive"))
      (node (ref "JP341") (pin "1") (pinfunction "1_1") (pintype "passive"))
      (node (ref "JP342") (pin "1") (pinfunction "1_1") (pintype "passive"))
      (node (ref "JP343") (pin "1") (pinfunction "1_1") (pintype "passive"))
      (node (ref "JP788") (pin "1") (pinfunction "1_1") (pintype "passive"))
      (node (ref "POWER") (pin "3") (pinfunction "3_3") (pintype "passive"))
      (node (ref "POWER") (pin "4") (pinfunction "4_4") (pintype "passive"))
      (node (ref "POWER") (pin "5") (pinfunction "5_5") (pintype "passive"))
      (node (ref "POWER") (pin "6") (pinfunction "6_6") (pintype "passive"))
      (node (ref "POWER") (pin "7") (pinfunction "7_7") (pintype "passive"))
      (node (ref "POWER") (pin "8") (pinfunction "8_8") (pintype "passive"))
      (node (ref "U$2") (pin "P$3") (pinfunction "1_P$3") (pintype "passive"))
    )
    (net (code "8") (name "Net-(ARD1-Pad1)") (class "Default")
      (node (ref "ARD1") (pin "1") (pinfunction "1_1") (pintype "passive"))
      (node (ref "JP833") (pin "1") (pinfunction "1_1") (pintype "passive"))
      (node (ref "JP834") (pin "1") (pinfunction "1_1") (pintype "passive"))
    )
    (net (code "9") (name "Net-(ARD1-Pad2)") (class "Default")
      (node (ref "ARD1") (pin "2") (pinfunction "2_2") (pintype "passive"))
      (node (ref "JP831") (pin "1") (pinfunction "1_1") (pintype "passive"))
      (node (ref "JP832") (pin "1") (pinfunction "1_1") (pintype "passive"))
    )
    (net (code "10") (name "Net-(ARD1-Pad3)") (class "Default")
      (node (ref "ARD1") (pin "3") (pinfunction "3_3") (pintype "passive"))
      (node (ref "JP829") (pin "1") (pinfunction "1_1") (pintype "passive"))
      (node (ref "JP830") (pin "1") (pinfunction "1_1") (pintype "passive"))
    )
    (net (code "11") (name "Net-(ARD1-Pad4)") (class "Default")
      (node (ref "ARD1") (pin "4") (pinfunction "4_4") (pintype "passive"))
      (node (ref "JP827") (pin "1") (pinfunction "1_1") (pintype "passive"))
      (node (ref "JP828") (pin "1") (pinfunction "1_1") (pintype "passive"))
    )
    (net (code "12") (name "Net-(ARD1-Pad5)") (class "Default")
      (node (ref "ARD1") (pin "5") (pinfunction "5_5") (pintype "passive"))
      (node (ref "JP825") (pin "1") (pinfunction "1_1") (pintype "passive"))
      (node (ref "JP826") (pin "1") (pinfunction "1_1") (pintype "passive"))
    )
    (net (code "13") (name "Net-(ARD1-Pad6)") (class "Default")
      (node (ref "ARD1") (pin "6") (pinfunction "6_6") (pintype "passive"))
      (node (ref "JP823") (pin "1") (pinfunction "1_1") (pintype "passive"))
      (node (ref "JP824") (pin "1") (pinfunction "1_1") (pintype "passive"))
    )
    (net (code "14") (name "Net-(ARD1-Pad7)") (class "Default")
      (node (ref "ARD1") (pin "7") (pinfunction "7_7") (pintype "passive"))
      (node (ref "JP821") (pin "1") (pinfunction "1_1") (pintype "passive"))
      (node (ref "JP822") (pin "1") (pinfunction "1_1") (pintype "passive"))
    )
    (net (code "15") (name "Net-(ARD1-Pad8)") (class "Default")
      (node (ref "ARD1") (pin "8") (pinfunction "8_8") (pintype "passive"))
      (node (ref "JP819") (pin "1") (pinfunction "1_1") (pintype "passive"))
      (node (ref "JP820") (pin "1") (pinfunction "1_1") (pintype "passive"))
    )
    (net (code "16") (name "Net-(ARD1-Pad9)") (class "Default")
      (node (ref "ARD1") (pin "9") (pinfunction "9_9") (pintype "passive"))
      (node (ref "JP835") (pin "1") (pinfunction "1_1") (pintype "passive"))
      (node (ref "JP836") (pin "1") (pinfunction "1_1") (pintype "passive"))
    )
    (net (code "17") (name "Net-(ARD1-Pad10)") (class "Default")
      (node (ref "ARD1") (pin "10") (pinfunction "10_10") (pintype "passive"))
      (node (ref "JP817") (pin "1") (pinfunction "1_1") (pintype "passive"))
      (node (ref "JP818") (pin "1") (pinfunction "1_1") (pintype "passive"))
    )
    (net (code "18") (name "Net-(ARD1-Pad11)") (class "Default")
      (node (ref "ARD1") (pin "11") (pinfunction "11_11") (pintype "passive"))
      (node (ref "JP799") (pin "1") (pinfunction "1_1") (pintype "passive"))
      (node (ref "JP800") (pin "1") (pinfunction "1_1") (pintype "passive"))
    )
    (net (code "19") (name "Net-(ARD1-Pad13)") (class "Default")
      (node (ref "ARD1") (pin "13") (pinfunction "13_13") (pintype "passive"))
      (node (ref "JP841") (pin "1") (pinfunction "1_1") (pintype "passive"))
      (node (ref "JP842") (pin "1") (pinfunction "1_1") (pintype "passive"))
    )
    (net (code "20") (name "Net-(ARD1-Pad14)") (class "Default")
      (node (ref "ARD1") (pin "14") (pinfunction "14_14") (pintype "passive"))
      (node (ref "JP837") (pin "1") (pinfunction "1_1") (pintype "passive"))
      (node (ref "JP838") (pin "1") (pinfunction "1_1") (pintype "passive"))
    )
    (net (code "21") (name "Net-(ARD1-Pad15)") (class "Default")
      (node (ref "ARD1") (pin "15") (pinfunction "15_15") (pintype "passive"))
      (node (ref "JP839") (pin "1") (pinfunction "1_1") (pintype "passive"))
      (node (ref "JP840") (pin "1") (pinfunction "1_1") (pintype "passive"))
    )
    (net (code "22") (name "Net-(ARD2-Pad1)") (class "Default")
      (node (ref "ARD2") (pin "1") (pinfunction "1_1") (pintype "passive"))
      (node (ref "JP795") (pin "1") (pinfunction "1_1") (pintype "passive"))
      (node (ref "JP796") (pin "1") (pinfunction "1_1") (pintype "passive"))
    )
    (net (code "23") (name "Net-(ARD2-Pad2)") (class "Default")
      (node (ref "ARD2") (pin "2") (pinfunction "2_2") (pintype "passive"))
      (node (ref "JP797") (pin "1") (pinfunction "1_1") (pintype "passive"))
      (node (ref "JP798") (pin "1") (pinfunction "1_1") (pintype "passive"))
    )
    (net (code "24") (name "Net-(ARD2-Pad4)") (class "Default")
      (node (ref "ARD2") (pin "4") (pinfunction "4_4") (pintype "passive"))
      (node (ref "JP801") (pin "1") (pinfunction "1_1") (pintype "passive"))
      (node (ref "JP802") (pin "1") (pinfunction "1_1") (pintype "passive"))
    )
    (net (code "25") (name "Net-(ARD2-Pad5)") (class "Default")
      (node (ref "ARD2") (pin "5") (pinfunction "5_5") (pintype "passive"))
      (node (ref "JP803") (pin "1") (pinfunction "1_1") (pintype "passive"))
      (node (ref "JP804") (pin "1") (pinfunction "1_1") (pintype "passive"))
    )
    (net (code "26") (name "Net-(ARD2-Pad6)") (class "Default")
      (node (ref "ARD2") (pin "6") (pinfunction "6_6") (pintype "passive"))
      (node (ref "JP805") (pin "1") (pinfunction "1_1") (pintype "passive"))
      (node (ref "JP806") (pin "1") (pinfunction "1_1") (pintype "passive"))
    )
    (net (code "27") (name "Net-(ARD2-Pad7)") (class "Default")
      (node (ref "ARD2") (pin "7") (pinfunction "7_7") (pintype "passive"))
      (node (ref "JP807") (pin "1") (pinfunction "1_1") (pintype "passive"))
      (node (ref "JP808") (pin "1") (pinfunction "1_1") (pintype "passive"))
    )
    (net (code "28") (name "Net-(ARD2-Pad8)") (class "Default")
      (node (ref "ARD2") (pin "8") (pinfunction "8_8") (pintype "passive"))
      (node (ref "JP809") (pin "1") (pinfunction "1_1") (pintype "passive"))
      (node (ref "JP810") (pin "1") (pinfunction "1_1") (pintype "passive"))
    )
    (net (code "29") (name "Net-(ARD2-Pad9)") (class "Default")
      (node (ref "ARD2") (pin "9") (pinfunction "9_9") (pintype "passive"))
      (node (ref "JP811") (pin "1") (pinfunction "1_1") (pintype "passive"))
      (node (ref "JP812") (pin "1") (pinfunction "1_1") (pintype "passive"))
    )
    (net (code "30") (name "Net-(ARD2-Pad10)") (class "Default")
      (node (ref "ARD2") (pin "10") (pinfunction "10_10") (pintype "passive"))
      (node (ref "JP813") (pin "1") (pinfunction "1_1") (pintype "passive"))
      (node (ref "JP814") (pin "1") (pinfunction "1_1") (pintype "passive"))
    )
    (net (code "31") (name "Net-(ARD2-Pad11)") (class "Default")
      (node (ref "ARD2") (pin "11") (pinfunction "11_11") (pintype "passive"))
      (node (ref "JP815") (pin "1") (pinfunction "1_1") (pintype "passive"))
      (node (ref "JP816") (pin "1") (pinfunction "1_1") (pintype "passive"))
    )
    (net (code "32") (name "Net-(GATE1-Pad3)") (class "Default")
      (node (ref "GATE1") (pin "3") (pinfunction "3_3") (pintype "passive"))
      (node (ref "JP726") (pin "1") (pinfunction "1_1") (pintype "passive"))
      (node (ref "JP734") (pin "1") (pinfunction "1_1") (pintype "passive"))
    )
    (net (code "33") (name "Net-(GATE1-Pad4)") (class "Default")
      (node (ref "GATE1") (pin "4") (pinfunction "4_4") (pintype "passive"))
      (node (ref "JP727") (pin "1") (pinfunction "1_1") (pintype "passive"))
      (node (ref "JP736") (pin "1") (pinfunction "1_1") (pintype "passive"))
    )
    (net (code "34") (name "Net-(GATE1-Pad5)") (class "Default")
      (node (ref "GATE1") (pin "5") (pinfunction "5_5") (pintype "passive"))
      (node (ref "JP728") (pin "1") (pinfunction "1_1") (pintype "passive"))
      (node (ref "JP735") (pin "1") (pinfunction "1_1") (pintype "passive"))
    )
    (net (code "35") (name "Net-(GATE2-Pad2)") (class "Default")
      (node (ref "GATE2") (pin "2") (pinfunction "2_2") (pintype "passive"))
      (node (ref "JP729") (pin "1") (pinfunction "1_1") (pintype "passive"))
      (node (ref "JP737") (pin "1") (pinfunction "1_1") (pintype "passive"))
    )
    (net (code "36") (name "Net-(GATE2-Pad3)") (class "Default")
      (node (ref "GATE2") (pin "3") (pinfunction "3_3") (pintype "passive"))
      (node (ref "JP730") (pin "1") (pinfunction "1_1") (pintype "passive"))
      (node (ref "JP738") (pin "1") (pinfunction "1_1") (pintype "passive"))
    )
    (net (code "37") (name "Net-(GATE2-Pad4)") (class "Default")
      (node (ref "GATE2") (pin "4") (pinfunction "4_4") (pintype "passive"))
      (node (ref "JP731") (pin "1") (pinfunction "1_1") (pintype "passive"))
      (node (ref "JP739") (pin "1") (pinfunction "1_1") (pintype "passive"))
    )
    (net (code "38") (name "Net-(GATE2-Pad5)") (class "Default")
      (node (ref "GATE2") (pin "5") (pinfunction "5_5") (pintype "passive"))
      (node (ref "JP732") (pin "1") (pinfunction "1_1") (pintype "passive"))
      (node (ref "JP740") (pin "1") (pinfunction "1_1") (pintype "passive"))
    )
    (net (code "39") (name "Net-(JP46-Pad1)") (class "Default")
      (node (ref "JP46") (pin "1") (pinfunction "1_1") (pintype "passive"))
      (node (ref "JP48") (pin "1") (pinfunction "1_1") (pintype "passive"))
    )
    (net (code "40") (name "Net-(JP50-Pad1)") (class "Default")
      (node (ref "JP50") (pin "1") (pinfunction "1_1") (pintype "passive"))
      (node (ref "JP52") (pin "1") (pinfunction "1_1") (pintype "passive"))
    )
    (net (code "41") (name "Net-(JP54-Pad1)") (class "Default")
      (node (ref "JP54") (pin "1") (pinfunction "1_1") (pintype "passive"))
      (node (ref "JP56") (pin "1") (pinfunction "1_1") (pintype "passive"))
    )
    (net (code "42") (name "Net-(JP58-Pad1)") (class "Default")
      (node (ref "JP58") (pin "1") (pinfunction "1_1") (pintype "passive"))
      (node (ref "JP60") (pin "1") (pinfunction "1_1") (pintype "passive"))
    )
    (net (code "43") (name "Net-(JP62-Pad1)") (class "Default")
      (node (ref "JP62") (pin "1") (pinfunction "1_1") (pintype "passive"))
      (node (ref "JP64") (pin "1") (pinfunction "1_1") (pintype "passive"))
    )
    (net (code "44") (name "Net-(JP66-Pad1)") (class "Default")
      (node (ref "JP66") (pin "1") (pinfunction "1_1") (pintype "passive"))
      (node (ref "JP68") (pin "1") (pinfunction "1_1") (pintype "passive"))
    )
    (net (code "45") (name "Net-(JP69-Pad1)") (class "Default")
      (node (ref "JP69") (pin "1") (pinfunction "1_1") (pintype "passive"))
      (node (ref "JP70") (pin "1") (pinfunction "1_1") (pintype "passive"))
    )
    (net (code "46") (name "Net-(JP71-Pad1)") (class "Default")
      (node (ref "JP71") (pin "1") (pinfunction "1_1") (pintype "passive"))
      (node (ref "JP72") (pin "1") (pinfunction "1_1") (pintype "passive"))
    )
    (net (code "47") (name "Net-(JP73-Pad1)") (class "Default")
      (node (ref "JP73") (pin "1") (pinfunction "1_1") (pintype "passive"))
      (node (ref "JP74") (pin "1") (pinfunction "1_1") (pintype "passive"))
    )
    (net (code "48") (name "Net-(JP75-Pad1)") (class "Default")
      (node (ref "JP75") (pin "1") (pinfunction "1_1") (pintype "passive"))
      (node (ref "JP76") (pin "1") (pinfunction "1_1") (pintype "passive"))
    )
    (net (code "49") (name "Net-(JP77-Pad1)") (class "Default")
      (node (ref "JP77") (pin "1") (pinfunction "1_1") (pintype "passive"))
      (node (ref "JP78") (pin "1") (pinfunction "1_1") (pintype "passive"))
    )
    (net (code "50") (name "Net-(JP79-Pad1)") (class "Default")
      (node (ref "JP79") (pin "1") (pinfunction "1_1") (pintype "passive"))
      (node (ref "JP80") (pin "1") (pinfunction "1_1") (pintype "passive"))
    )
    (net (code "51") (name "Net-(JP81-Pad1)") (class "Default")
      (node (ref "JP81") (pin "1") (pinfunction "1_1") (pintype "passive"))
      (node (ref "JP82") (pin "1") (pinfunction "1_1") (pintype "passive"))
    )
    (net (code "52") (name "Net-(JP83-Pad1)") (class "Default")
      (node (ref "JP83") (pin "1") (pinfunction "1_1") (pintype "passive"))
      (node (ref "JP84") (pin "1") (pinfunction "1_1") (pintype "passive"))
    )
    (net (code "53") (name "Net-(JP85-Pad1)") (class "Default")
      (node (ref "JP85") (pin "1") (pinfunction "1_1") (pintype "passive"))
      (node (ref "JP86") (pin "1") (pinfunction "1_1") (pintype "passive"))
    )
    (net (code "54") (name "Net-(JP88-Pad1)") (class "Default")
      (node (ref "JP88") (pin "1") (pinfunction "1_1") (pintype "passive"))
      (node (ref "JP89") (pin "1") (pinfunction "1_1") (pintype "passive"))
    )
    (net (code "55") (name "Net-(JP90-Pad1)") (class "Default")
      (node (ref "JP90") (pin "1") (pinfunction "1_1") (pintype "passive"))
      (node (ref "JP93") (pin "1") (pinfunction "1_1") (pintype "passive"))
    )
    (net (code "56") (name "Net-(JP91-Pad1)") (class "Default")
      (node (ref "JP91") (pin "1") (pinfunction "1_1") (pintype "passive"))
      (node (ref "JP92") (pin "1") (pinfunction "1_1") (pintype "passive"))
    )
    (net (code "57") (name "Net-(JP94-Pad1)") (class "Default")
      (node (ref "JP94") (pin "1") (pinfunction "1_1") (pintype "passive"))
      (node (ref "JP95") (pin "1") (pinfunction "1_1") (pintype "passive"))
    )
    (net (code "58") (name "Net-(JP96-Pad1)") (class "Default")
      (node (ref "JP96") (pin "1") (pinfunction "1_1") (pintype "passive"))
      (node (ref "JP97") (pin "1") (pinfunction "1_1") (pintype "passive"))
    )
    (net (code "59") (name "Net-(JP98-Pad1)") (class "Default")
      (node (ref "JP98") (pin "1") (pinfunction "1_1") (pintype "passive"))
      (node (ref "JP99") (pin "1") (pinfunction "1_1") (pintype "passive"))
    )
    (net (code "60") (name "Net-(JP100-Pad1)") (class "Default")
      (node (ref "JP100") (pin "1") (pinfunction "1_1") (pintype "passive"))
      (node (ref "JP101") (pin "1") (pinfunction "1_1") (pintype "passive"))
    )
    (net (code "61") (name "Net-(JP102-Pad1)") (class "Default")
      (node (ref "JP102") (pin "1") (pinfunction "1_1") (pintype "passive"))
      (node (ref "JP103") (pin "1") (pinfunction "1_1") (pintype "passive"))
      (node (ref "JP790") (pin "1") (pinfunction "1_1") (pintype "passive"))
    )
    (net (code "62") (name "Net-(JP104-Pad1)") (class "Default")
      (node (ref "JP104") (pin "1") (pinfunction "1_1") (pintype "passive"))
      (node (ref "JP105") (pin "1") (pinfunction "1_1") (pintype "passive"))
    )
    (net (code "63") (name "Net-(JP106-Pad1)") (class "Default")
      (node (ref "JP106") (pin "1") (pinfunction "1_1") (pintype "passive"))
      (node (ref "JP107") (pin "1") (pinfunction "1_1") (pintype "passive"))
    )
    (net (code "64") (name "Net-(JP108-Pad1)") (class "Default")
      (node (ref "JP108") (pin "1") (pinfunction "1_1") (pintype "passive"))
      (node (ref "JP109") (pin "1") (pinfunction "1_1") (pintype "passive"))
    )
    (net (code "65") (name "Net-(JP110-Pad1)") (class "Default")
      (node (ref "JP110") (pin "1") (pinfunction "1_1") (pintype "passive"))
      (node (ref "JP111") (pin "1") (pinfunction "1_1") (pintype "passive"))
    )
    (net (code "66") (name "Net-(JP112-Pad1)") (class "Default")
      (node (ref "JP112") (pin "1") (pinfunction "1_1") (pintype "passive"))
      (node (ref "JP113") (pin "1") (pinfunction "1_1") (pintype "passive"))
    )
    (net (code "67") (name "Net-(JP116-Pad1)") (class "Default")
      (node (ref "JP116") (pin "1") (pinfunction "1_1") (pintype "passive"))
      (node (ref "JP789") (pin "1") (pinfunction "1_1") (pintype "passive"))
      (node (ref "JP87") (pin "1") (pinfunction "1_1") (pintype "passive"))
    )
    (net (code "68") (name "Net-(JP193-Pad1)") (class "Default")
      (node (ref "JP193") (pin "1") (pinfunction "1_1") (pintype "passive"))
      (node (ref "JP194") (pin "1") (pinfunction "1_1") (pintype "passive"))
      (node (ref "JP195") (pin "1") (pinfunction "1_1") (pintype "passive"))
      (node (ref "JP196") (pin "1") (pinfunction "1_1") (pintype "passive"))
      (node (ref "JP197") (pin "1") (pinfunction "1_1") (pintype "passive"))
      (node (ref "JP198") (pin "1") (pinfunction "1_1") (pintype "passive"))
      (node (ref "JP199") (pin "1") (pinfunction "1_1") (pintype "passive"))
      (node (ref "JP200") (pin "1") (pinfunction "1_1") (pintype "passive"))
      (node (ref "JP201") (pin "1") (pinfunction "1_1") (pintype "passive"))
      (node (ref "JP202") (pin "1") (pinfunction "1_1") (pintype "passive"))
      (node (ref "JP203") (pin "1") (pinfunction "1_1") (pintype "passive"))
      (node (ref "JP204") (pin "1") (pinfunction "1_1") (pintype "passive"))
      (node (ref "JP205") (pin "1") (pinfunction "1_1") (pintype "passive"))
      (node (ref "JP206") (pin "1") (pinfunction "1_1") (pintype "passive"))
      (node (ref "JP207") (pin "1") (pinfunction "1_1") (pintype "passive"))
      (node (ref "JP208") (pin "1") (pinfunction "1_1") (pintype "passive"))
      (node (ref "JP209") (pin "1") (pinfunction "1_1") (pintype "passive"))
      (node (ref "JP210") (pin "1") (pinfunction "1_1") (pintype "passive"))
      (node (ref "JP211") (pin "1") (pinfunction "1_1") (pintype "passive"))
      (node (ref "JP212") (pin "1") (pinfunction "1_1") (pintype "passive"))
      (node (ref "JP213") (pin "1") (pinfunction "1_1") (pintype "passive"))
      (node (ref "JP214") (pin "1") (pinfunction "1_1") (pintype "passive"))
      (node (ref "JP215") (pin "1") (pinfunction "1_1") (pintype "passive"))
      (node (ref "JP216") (pin "1") (pinfunction "1_1") (pintype "passive"))
      (node (ref "JP217") (pin "1") (pinfunction "1_1") (pintype "passive"))
      (node (ref "JP218") (pin "1") (pinfunction "1_1") (pintype "passive"))
      (node (ref "JP219") (pin "1") (pinfunction "1_1") (pintype "passive"))
      (node (ref "JP220") (pin "1") (pinfunction "1_1") (pintype "passive"))
      (node (ref "JP221") (pin "1") (pinfunction "1_1") (pintype "passive"))
      (node (ref "JP222") (pin "1") (pinfunction "1_1") (pintype "passive"))
      (node (ref "JP223") (pin "1") (pinfunction "1_1") (pintype "passive"))
      (node (ref "JP224") (pin "1") (pinfunction "1_1") (pintype "passive"))
      (node (ref "JP225") (pin "1") (pinfunction "1_1") (pintype "passive"))
      (node (ref "JP226") (pin "1") (pinfunction "1_1") (pintype "passive"))
      (node (ref "JP227") (pin "1") (pinfunction "1_1") (pintype "passive"))
      (node (ref "JP228") (pin "1") (pinfunction "1_1") (pintype "passive"))
      (node (ref "JP724") (pin "1") (pinfunction "1_1") (pintype "passive"))
    )
    (net (code "69") (name "Net-(JP230-Pad1)") (class "Default")
      (node (ref "JP230") (pin "1") (pinfunction "1_1") (pintype "passive"))
      (node (ref "JP232") (pin "1") (pinfunction "1_1") (pintype "passive"))
      (node (ref "JP233") (pin "1") (pinfunction "1_1") (pintype "passive"))
      (node (ref "JP234") (pin "1") (pinfunction "1_1") (pintype "passive"))
      (node (ref "JP235") (pin "1") (pinfunction "1_1") (pintype "passive"))
      (node (ref "JP236") (pin "1") (pinfunction "1_1") (pintype "passive"))
      (node (ref "JP237") (pin "1") (pinfunction "1_1") (pintype "passive"))
      (node (ref "JP238") (pin "1") (pinfunction "1_1") (pintype "passive"))
      (node (ref "JP239") (pin "1") (pinfunction "1_1") (pintype "passive"))
      (node (ref "JP240") (pin "1") (pinfunction "1_1") (pintype "passive"))
      (node (ref "JP241") (pin "1") (pinfunction "1_1") (pintype "passive"))
      (node (ref "JP242") (pin "1") (pinfunction "1_1") (pintype "passive"))
      (node (ref "JP243") (pin "1") (pinfunction "1_1") (pintype "passive"))
      (node (ref "JP244") (pin "1") (pinfunction "1_1") (pintype "passive"))
      (node (ref "JP245") (pin "1") (pinfunction "1_1") (pintype "passive"))
      (node (ref "JP246") (pin "1") (pinfunction "1_1") (pintype "passive"))
      (node (ref "JP247") (pin "1") (pinfunction "1_1") (pintype "passive"))
      (node (ref "JP248") (pin "1") (pinfunction "1_1") (pintype "passive"))
      (node (ref "JP249") (pin "1") (pinfunction "1_1") (pintype "passive"))
      (node (ref "JP250") (pin "1") (pinfunction "1_1") (pintype "passive"))
      (node (ref "JP251") (pin "1") (pinfunction "1_1") (pintype "passive"))
      (node (ref "JP252") (pin "1") (pinfunction "1_1") (pintype "passive"))
      (node (ref "JP253") (pin "1") (pinfunction "1_1") (pintype "passive"))
      (node (ref "JP254") (pin "1") (pinfunction "1_1") (pintype "passive"))
      (node (ref "JP255") (pin "1") (pinfunction "1_1") (pintype "passive"))
      (node (ref "JP256") (pin "1") (pinfunction "1_1") (pintype "passive"))
      (node (ref "JP257") (pin "1") (pinfunction "1_1") (pintype "passive"))
      (node (ref "JP258") (pin "1") (pinfunction "1_1") (pintype "passive"))
      (node (ref "JP259") (pin "1") (pinfunction "1_1") (pintype "passive"))
      (node (ref "JP260") (pin "1") (pinfunction "1_1") (pintype "passive"))
      (node (ref "JP261") (pin "1") (pinfunction "1_1") (pintype "passive"))
      (node (ref "JP262") (pin "1") (pinfunction "1_1") (pintype "passive"))
      (node (ref "JP263") (pin "1") (pinfunction "1_1") (pintype "passive"))
      (node (ref "JP264") (pin "1") (pinfunction "1_1") (pintype "passive"))
      (node (ref "JP265") (pin "1") (pinfunction "1_1") (pintype "passive"))
      (node (ref "JP723") (pin "1") (pinfunction "1_1") (pintype "passive"))
    )
    (net (code "70") (name "Net-(JP742-Pad1)") (class "Default")
      (node (ref "JP742") (pin "1") (pinfunction "1_1") (pintype "passive"))
      (node (ref "JP743") (pin "1") (pinfunction "1_1") (pintype "passive"))
      (node (ref "JP744") (pin "1") (pinfunction "1_1") (pintype "passive"))
      (node (ref "JP745") (pin "1") (pinfunction "1_1") (pintype "passive"))
      (node (ref "JP746") (pin "1") (pinfunction "1_1") (pintype "passive"))
      (node (ref "JP747") (pin "1") (pinfunction "1_1") (pintype "passive"))
      (node (ref "JP748") (pin "1") (pinfunction "1_1") (pintype "passive"))
      (node (ref "JP749") (pin "1") (pinfunction "1_1") (pintype "passive"))
      (node (ref "JP750") (pin "1") (pinfunction "1_1") (pintype "passive"))
      (node (ref "JP751") (pin "1") (pinfunction "1_1") (pintype "passive"))
      (node (ref "JP752") (pin "1") (pinfunction "1_1") (pintype "passive"))
      (node (ref "JP753") (pin "1") (pinfunction "1_1") (pintype "passive"))
      (node (ref "JP754") (pin "1") (pinfunction "1_1") (pintype "passive"))
      (node (ref "JP755") (pin "1") (pinfunction "1_1") (pintype "passive"))
      (node (ref "JP756") (pin "1") (pinfunction "1_1") (pintype "passive"))
      (node (ref "JP757") (pin "1") (pinfunction "1_1") (pintype "passive"))
      (node (ref "JP758") (pin "1") (pinfunction "1_1") (pintype "passive"))
      (node (ref "JP759") (pin "1") (pinfunction "1_1") (pintype "passive"))
      (node (ref "JP760") (pin "1") (pinfunction "1_1") (pintype "passive"))
      (node (ref "JP761") (pin "1") (pinfunction "1_1") (pintype "passive"))
      (node (ref "JP762") (pin "1") (pinfunction "1_1") (pintype "passive"))
      (node (ref "JP763") (pin "1") (pinfunction "1_1") (pintype "passive"))
      (node (ref "JP764") (pin "1") (pinfunction "1_1") (pintype "passive"))
      (node (ref "JP765") (pin "1") (pinfunction "1_1") (pintype "passive"))
      (node (ref "JP766") (pin "1") (pinfunction "1_1") (pintype "passive"))
      (node (ref "JP767") (pin "1") (pinfunction "1_1") (pintype "passive"))
      (node (ref "JP768") (pin "1") (pinfunction "1_1") (pintype "passive"))
      (node (ref "JP769") (pin "1") (pinfunction "1_1") (pintype "passive"))
      (node (ref "JP770") (pin "1") (pinfunction "1_1") (pintype "passive"))
      (node (ref "JP771") (pin "1") (pinfunction "1_1") (pintype "passive"))
      (node (ref "JP772") (pin "1") (pinfunction "1_1") (pintype "passive"))
      (node (ref "JP773") (pin "1") (pinfunction "1_1") (pintype "passive"))
      (node (ref "JP774") (pin "1") (pinfunction "1_1") (pintype "passive"))
      (node (ref "JP775") (pin "1") (pinfunction "1_1") (pintype "passive"))
      (node (ref "JP776") (pin "1") (pinfunction "1_1") (pintype "passive"))
      (node (ref "JP777") (pin "1") (pinfunction "1_1") (pintype "passive"))
      (node (ref "JP780") (pin "1") (pinfunction "1_1") (pintype "passive"))
    )
    (net (code "71") (name "Net-(R1-A)") (class "Default")
      (node (ref "JP10") (pin "1") (pinfunction "1_1") (pintype "passive"))
      (node (ref "JP11") (pin "1") (pinfunction "1_1") (pintype "passive"))
      (node (ref "JP49") (pin "1") (pinfunction "1_1") (pintype "passive"))
      (node (ref "JP9") (pin "1") (pinfunction "1_1") (pintype "passive"))
      (node (ref "R1") (pin "1") (pinfunction "A_1") (pintype "passive"))
    )
    (net (code "72") (name "Net-(R1-E)") (class "Default")
      (node (ref "JP2") (pin "1") (pinfunction "1_1") (pintype "passive"))
      (node (ref "JP3") (pin "1") (pinfunction "1_1") (pintype "passive"))
      (node (ref "JP45") (pin "1") (pinfunction "1_1") (pintype "passive"))
      (node (ref "JP5") (pin "1") (pinfunction "1_1") (pintype "passive"))
      (node (ref "R1") (pin "3") (pinfunction "E_3") (pintype "passive"))
    )
    (net (code "73") (name "Net-(R1-S)") (class "Default")
      (node (ref "JP47") (pin "1") (pinfunction "1_1") (pintype "passive"))
      (node (ref "JP6") (pin "1") (pinfunction "1_1") (pintype "passive"))
      (node (ref "JP7") (pin "1") (pinfunction "1_1") (pintype "passive"))
      (node (ref "JP8") (pin "1") (pinfunction "1_1") (pintype "passive"))
      (node (ref "R1") (pin "2") (pinfunction "S_2") (pintype "passive"))
    )
    (net (code "74") (name "Net-(R2-A)") (class "Default")
      (node (ref "JP20") (pin "1") (pinfunction "1_1") (pintype "passive"))
      (node (ref "JP21") (pin "1") (pinfunction "1_1") (pintype "passive"))
      (node (ref "JP22") (pin "1") (pinfunction "1_1") (pintype "passive"))
      (node (ref "JP55") (pin "1") (pinfunction "1_1") (pintype "passive"))
      (node (ref "R2") (pin "1") (pinfunction "A_1") (pintype "passive"))
    )
    (net (code "75") (name "Net-(R2-E)") (class "Default")
      (node (ref "JP14") (pin "1") (pinfunction "1_1") (pintype "passive"))
      (node (ref "JP15") (pin "1") (pinfunction "1_1") (pintype "passive"))
      (node (ref "JP16") (pin "1") (pinfunction "1_1") (pintype "passive"))
      (node (ref "JP51") (pin "1") (pinfunction "1_1") (pintype "passive"))
      (node (ref "R2") (pin "3") (pinfunction "E_3") (pintype "passive"))
    )
    (net (code "76") (name "Net-(R2-S)") (class "Default")
      (node (ref "JP17") (pin "1") (pinfunction "1_1") (pintype "passive"))
      (node (ref "JP18") (pin "1") (pinfunction "1_1") (pintype "passive"))
      (node (ref "JP19") (pin "1") (pinfunction "1_1") (pintype "passive"))
      (node (ref "JP53") (pin "1") (pinfunction "1_1") (pintype "passive"))
      (node (ref "R2") (pin "2") (pinfunction "S_2") (pintype "passive"))
    )
    (net (code "77") (name "Net-(R3-A)") (class "Default")
      (node (ref "JP29") (pin "1") (pinfunction "1_1") (pintype "passive"))
      (node (ref "JP30") (pin "1") (pinfunction "1_1") (pintype "passive"))
      (node (ref "JP31") (pin "1") (pinfunction "1_1") (pintype "passive"))
      (node (ref "JP61") (pin "1") (pinfunction "1_1") (pintype "passive"))
      (node (ref "R3") (pin "1") (pinfunction "A_1") (pintype "passive"))
    )
    (net (code "78") (name "Net-(R3-E)") (class "Default")
      (node (ref "JP23") (pin "1") (pinfunction "1_1") (pintype "passive"))
      (node (ref "JP24") (pin "1") (pinfunction "1_1") (pintype "passive"))
      (node (ref "JP25") (pin "1") (pinfunction "1_1") (pintype "passive"))
      (node (ref "JP57") (pin "1") (pinfunction "1_1") (pintype "passive"))
      (node (ref "R3") (pin "3") (pinfunction "E_3") (pintype "passive"))
    )
    (net (code "79") (name "Net-(R3-S)") (class "Default")
      (node (ref "JP26") (pin "1") (pinfunction "1_1") (pintype "passive"))
      (node (ref "JP27") (pin "1") (pinfunction "1_1") (pintype "passive"))
      (node (ref "JP28") (pin "1") (pinfunction "1_1") (pintype "passive"))
      (node (ref "JP59") (pin "1") (pinfunction "1_1") (pintype "passive"))
      (node (ref "R3") (pin "2") (pinfunction "S_2") (pintype "passive"))
    )
    (net (code "80") (name "Net-(R4-A)") (class "Default")
      (node (ref "JP40") (pin "1") (pinfunction "1_1") (pintype "passive"))
      (node (ref "JP41") (pin "1") (pinfunction "1_1") (pintype "passive"))
      (node (ref "JP42") (pin "1") (pinfunction "1_1") (pintype "passive"))
      (node (ref "JP67") (pin "1") (pinfunction "1_1") (pintype "passive"))
      (node (ref "R4") (pin "1") (pinfunction "A_1") (pintype "passive"))
    )
    (net (code "81") (name "Net-(R4-E)") (class "Default")
      (node (ref "JP34") (pin "1") (pinfunction "1_1") (pintype "passive"))
      (node (ref "JP35") (pin "1") (pinfunction "1_1") (pintype "passive"))
      (node (ref "JP36") (pin "1") (pinfunction "1_1") (pintype "passive"))
      (node (ref "JP63") (pin "1") (pinfunction "1_1") (pintype "passive"))
      (node (ref "R4") (pin "3") (pinfunction "E_3") (pintype "passive"))
    )
    (net (code "82") (name "Net-(R4-S)") (class "Default")
      (node (ref "JP37") (pin "1") (pinfunction "1_1") (pintype "passive"))
      (node (ref "JP38") (pin "1") (pinfunction "1_1") (pintype "passive"))
      (node (ref "JP39") (pin "1") (pinfunction "1_1") (pintype "passive"))
      (node (ref "JP65") (pin "1") (pinfunction "1_1") (pintype "passive"))
      (node (ref "R4") (pin "2") (pinfunction "S_2") (pintype "passive"))
    )
    (net (code "83") (name "unconnected-(ARD2-Pad13)") (class "Default")
      (node (ref "ARD2") (pin "13") (pinfunction "13_13") (pintype "passive"))
    )
    (net (code "84") (name "unconnected-(ARD2-Pad15)") (class "Default")
      (node (ref "ARD2") (pin "15") (pinfunction "15_15") (pintype "passive"))
    )
    (net (code "85") (name "unconnected-(JP1-Pad1)") (class "Default")
      (node (ref "JP1") (pin "1") (pinfunction "1_1") (pintype "passive"))
    )
    (net (code "86") (name "unconnected-(JP4-Pad1)") (class "Default")
      (node (ref "JP4") (pin "1") (pinfunction "1_1") (pintype "passive"))
    )
    (net (code "87") (name "unconnected-(JP12-Pad1)") (class "Default")
      (node (ref "JP12") (pin "1") (pinfunction "1_1") (pintype "passive"))
    )
    (net (code "88") (name "unconnected-(JP13-Pad1)") (class "Default")
      (node (ref "JP13") (pin "1") (pinfunction "1_1") (pintype "passive"))
    )
    (net (code "89") (name "unconnected-(JP32-Pad1)") (class "Default")
      (node (ref "JP32") (pin "1") (pinfunction "1_1") (pintype "passive"))
    )
    (net (code "90") (name "unconnected-(JP33-Pad1)") (class "Default")
      (node (ref "JP33") (pin "1") (pinfunction "1_1") (pintype "passive"))
    )
    (net (code "91") (name "unconnected-(JP43-Pad1)") (class "Default")
      (node (ref "JP43") (pin "1") (pinfunction "1_1") (pintype "passive"))
    )
    (net (code "92") (name "unconnected-(JP44-Pad1)") (class "Default")
      (node (ref "JP44") (pin "1") (pinfunction "1_1") (pintype "passive"))
    )
    (net (code "93") (name "unconnected-(JP153-Pad1)") (class "Default")
      (node (ref "JP153") (pin "1") (pinfunction "1_1") (pintype "passive"))
    )
    (net (code "94") (name "unconnected-(JP191-Pad1)") (class "Default")
      (node (ref "JP191") (pin "1") (pinfunction "1_1") (pintype "passive"))
    )
    (net (code "95") (name "unconnected-(JP192-Pad1)") (class "Default")
      (node (ref "JP192") (pin "1") (pinfunction "1_1") (pintype "passive"))
    )
    (net (code "96") (name "unconnected-(JP229-Pad1)") (class "Default")
      (node (ref "JP229") (pin "1") (pinfunction "1_1") (pintype "passive"))
    )
    (net (code "97") (name "unconnected-(JP231-Pad1)") (class "Default")
      (node (ref "JP231") (pin "1") (pinfunction "1_1") (pintype "passive"))
    )
    (net (code "98") (name "unconnected-(JP266-Pad1)") (class "Default")
      (node (ref "JP266") (pin "1") (pinfunction "1_1") (pintype "passive"))
    )
    (net (code "99") (name "unconnected-(JP346-Pad1)") (class "Default")
      (node (ref "JP346") (pin "1") (pinfunction "1_1") (pintype "passive"))
    )
    (net (code "100") (name "unconnected-(JP347-Pad1)") (class "Default")
      (node (ref "JP347") (pin "1") (pinfunction "1_1") (pintype "passive"))
    )
    (net (code "101") (name "unconnected-(JP348-Pad1)") (class "Default")
      (node (ref "JP348") (pin "1") (pinfunction "1_1") (pintype "passive"))
    )
    (net (code "102") (name "unconnected-(JP349-Pad1)") (class "Default")
      (node (ref "JP349") (pin "1") (pinfunction "1_1") (pintype "passive"))
    )
    (net (code "103") (name "unconnected-(JP350-Pad1)") (class "Default")
      (node (ref "JP350") (pin "1") (pinfunction "1_1") (pintype "passive"))
    )
    (net (code "104") (name "unconnected-(JP351-Pad1)") (class "Default")
      (node (ref "JP351") (pin "1") (pinfunction "1_1") (pintype "passive"))
    )
    (net (code "105") (name "unconnected-(JP352-Pad1)") (class "Default")
      (node (ref "JP352") (pin "1") (pinfunction "1_1") (pintype "passive"))
    )
    (net (code "106") (name "unconnected-(JP353-Pad1)") (class "Default")
      (node (ref "JP353") (pin "1") (pinfunction "1_1") (pintype "passive"))
    )
    (net (code "107") (name "unconnected-(JP354-Pad1)") (class "Default")
      (node (ref "JP354") (pin "1") (pinfunction "1_1") (pintype "passive"))
    )
    (net (code "108") (name "unconnected-(JP355-Pad1)") (class "Default")
      (node (ref "JP355") (pin "1") (pinfunction "1_1") (pintype "passive"))
    )
    (net (code "109") (name "unconnected-(JP356-Pad1)") (class "Default")
      (node (ref "JP356") (pin "1") (pinfunction "1_1") (pintype "passive"))
    )
    (net (code "110") (name "unconnected-(JP357-Pad1)") (class "Default")
      (node (ref "JP357") (pin "1") (pinfunction "1_1") (pintype "passive"))
    )
    (net (code "111") (name "unconnected-(JP358-Pad1)") (class "Default")
      (node (ref "JP358") (pin "1") (pinfunction "1_1") (pintype "passive"))
    )
    (net (code "112") (name "unconnected-(JP359-Pad1)") (class "Default")
      (node (ref "JP359") (pin "1") (pinfunction "1_1") (pintype "passive"))
    )
    (net (code "113") (name "unconnected-(JP360-Pad1)") (class "Default")
      (node (ref "JP360") (pin "1") (pinfunction "1_1") (pintype "passive"))
    )
    (net (code "114") (name "unconnected-(JP361-Pad1)") (class "Default")
      (node (ref "JP361") (pin "1") (pinfunction "1_1") (pintype "passive"))
    )
    (net (code "115") (name "unconnected-(JP362-Pad1)") (class "Default")
      (node (ref "JP362") (pin "1") (pinfunction "1_1") (pintype "passive"))
    )
    (net (code "116") (name "unconnected-(JP363-Pad1)") (class "Default")
      (node (ref "JP363") (pin "1") (pinfunction "1_1") (pintype "passive"))
    )
    (net (code "117") (name "unconnected-(JP364-Pad1)") (class "Default")
      (node (ref "JP364") (pin "1") (pinfunction "1_1") (pintype "passive"))
    )
    (net (code "118") (name "unconnected-(JP365-Pad1)") (class "Default")
      (node (ref "JP365") (pin "1") (pinfunction "1_1") (pintype "passive"))
    )
    (net (code "119") (name "unconnected-(JP366-Pad1)") (class "Default")
      (node (ref "JP366") (pin "1") (pinfunction "1_1") (pintype "passive"))
    )
    (net (code "120") (name "unconnected-(JP367-Pad1)") (class "Default")
      (node (ref "JP367") (pin "1") (pinfunction "1_1") (pintype "passive"))
    )
    (net (code "121") (name "unconnected-(JP368-Pad1)") (class "Default")
      (node (ref "JP368") (pin "1") (pinfunction "1_1") (pintype "passive"))
    )
    (net (code "122") (name "unconnected-(JP369-Pad1)") (class "Default")
      (node (ref "JP369") (pin "1") (pinfunction "1_1") (pintype "passive"))
    )
    (net (code "123") (name "unconnected-(JP370-Pad1)") (class "Default")
      (node (ref "JP370") (pin "1") (pinfunction "1_1") (pintype "passive"))
    )
    (net (code "124") (name "unconnected-(JP371-Pad1)") (class "Default")
      (node (ref "JP371") (pin "1") (pinfunction "1_1") (pintype "passive"))
    )
    (net (code "125") (name "unconnected-(JP372-Pad1)") (class "Default")
      (node (ref "JP372") (pin "1") (pinfunction "1_1") (pintype "passive"))
    )
    (net (code "126") (name "unconnected-(JP373-Pad1)") (class "Default")
      (node (ref "JP373") (pin "1") (pinfunction "1_1") (pintype "passive"))
    )
    (net (code "127") (name "unconnected-(JP374-Pad1)") (class "Default")
      (node (ref "JP374") (pin "1") (pinfunction "1_1") (pintype "passive"))
    )
    (net (code "128") (name "unconnected-(JP375-Pad1)") (class "Default")
      (node (ref "JP375") (pin "1") (pinfunction "1_1") (pintype "passive"))
    )
    (net (code "129") (name "unconnected-(JP376-Pad1)") (class "Default")
      (node (ref "JP376") (pin "1") (pinfunction "1_1") (pintype "passive"))
    )
    (net (code "130") (name "unconnected-(JP377-Pad1)") (class "Default")
      (node (ref "JP377") (pin "1") (pinfunction "1_1") (pintype "passive"))
    )
    (net (code "131") (name "unconnected-(JP378-Pad1)") (class "Default")
      (node (ref "JP378") (pin "1") (pinfunction "1_1") (pintype "passive"))
    )
    (net (code "132") (name "unconnected-(JP379-Pad1)") (class "Default")
      (node (ref "JP379") (pin "1") (pinfunction "1_1") (pintype "passive"))
    )
    (net (code "133") (name "unconnected-(JP380-Pad1)") (class "Default")
      (node (ref "JP380") (pin "1") (pinfunction "1_1") (pintype "passive"))
    )
    (net (code "134") (name "unconnected-(JP381-Pad1)") (class "Default")
      (node (ref "JP381") (pin "1") (pinfunction "1_1") (pintype "passive"))
    )
    (net (code "135") (name "unconnected-(JP382-Pad1)") (class "Default")
      (node (ref "JP382") (pin "1") (pinfunction "1_1") (pintype "passive"))
    )
    (net (code "136") (name "unconnected-(JP383-Pad1)") (class "Default")
      (node (ref "JP383") (pin "1") (pinfunction "1_1") (pintype "passive"))
    )
    (net (code "137") (name "unconnected-(JP384-Pad1)") (class "Default")
      (node (ref "JP384") (pin "1") (pinfunction "1_1") (pintype "passive"))
    )
    (net (code "138") (name "unconnected-(JP385-Pad1)") (class "Default")
      (node (ref "JP385") (pin "1") (pinfunction "1_1") (pintype "passive"))
    )
    (net (code "139") (name "unconnected-(JP386-Pad1)") (class "Default")
      (node (ref "JP386") (pin "1") (pinfunction "1_1") (pintype "passive"))
    )
    (net (code "140") (name "unconnected-(JP387-Pad1)") (class "Default")
      (node (ref "JP387") (pin "1") (pinfunction "1_1") (pintype "passive"))
    )
    (net (code "141") (name "unconnected-(JP388-Pad1)") (class "Default")
      (node (ref "JP388") (pin "1") (pinfunction "1_1") (pintype "passive"))
    )
    (net (code "142") (name "unconnected-(JP389-Pad1)") (class "Default")
      (node (ref "JP389") (pin "1") (pinfunction "1_1") (pintype "passive"))
    )
    (net (code "143") (name "unconnected-(JP390-Pad1)") (class "Default")
      (node (ref "JP390") (pin "1") (pinfunction "1_1") (pintype "passive"))
    )
    (net (code "144") (name "unconnected-(JP391-Pad1)") (class "Default")
      (node (ref "JP391") (pin "1") (pinfunction "1_1") (pintype "passive"))
    )
    (net (code "145") (name "unconnected-(JP392-Pad1)") (class "Default")
      (node (ref "JP392") (pin "1") (pinfunction "1_1") (pintype "passive"))
    )
    (net (code "146") (name "unconnected-(JP393-Pad1)") (class "Default")
      (node (ref "JP393") (pin "1") (pinfunction "1_1") (pintype "passive"))
    )
    (net (code "147") (name "unconnected-(JP394-Pad1)") (class "Default")
      (node (ref "JP394") (pin "1") (pinfunction "1_1") (pintype "passive"))
    )
    (net (code "148") (name "unconnected-(JP395-Pad1)") (class "Default")
      (node (ref "JP395") (pin "1") (pinfunction "1_1") (pintype "passive"))
    )
    (net (code "149") (name "unconnected-(JP396-Pad1)") (class "Default")
      (node (ref "JP396") (pin "1") (pinfunction "1_1") (pintype "passive"))
    )
    (net (code "150") (name "unconnected-(JP397-Pad1)") (class "Default")
      (node (ref "JP397") (pin "1") (pinfunction "1_1") (pintype "passive"))
    )
    (net (code "151") (name "unconnected-(JP398-Pad1)") (class "Default")
      (node (ref "JP398") (pin "1") (pinfunction "1_1") (pintype "passive"))
    )
    (net (code "152") (name "unconnected-(JP399-Pad1)") (class "Default")
      (node (ref "JP399") (pin "1") (pinfunction "1_1") (pintype "passive"))
    )
    (net (code "153") (name "unconnected-(JP400-Pad1)") (class "Default")
      (node (ref "JP400") (pin "1") (pinfunction "1_1") (pintype "passive"))
    )
    (net (code "154") (name "unconnected-(JP401-Pad1)") (class "Default")
      (node (ref "JP401") (pin "1") (pinfunction "1_1") (pintype "passive"))
    )
    (net (code "155") (name "unconnected-(JP402-Pad1)") (class "Default")
      (node (ref "JP402") (pin "1") (pinfunction "1_1") (pintype "passive"))
    )
    (net (code "156") (name "unconnected-(JP403-Pad1)") (class "Default")
      (node (ref "JP403") (pin "1") (pinfunction "1_1") (pintype "passive"))
    )
    (net (code "157") (name "unconnected-(JP404-Pad1)") (class "Default")
      (node (ref "JP404") (pin "1") (pinfunction "1_1") (pintype "passive"))
    )
    (net (code "158") (name "unconnected-(JP405-Pad1)") (class "Default")
      (node (ref "JP405") (pin "1") (pinfunction "1_1") (pintype "passive"))
    )
    (net (code "159") (name "unconnected-(JP406-Pad1)") (class "Default")
      (node (ref "JP406") (pin "1") (pinfunction "1_1") (pintype "passive"))
    )
    (net (code "160") (name "unconnected-(JP407-Pad1)") (class "Default")
      (node (ref "JP407") (pin "1") (pinfunction "1_1") (pintype "passive"))
    )
    (net (code "161") (name "unconnected-(JP408-Pad1)") (class "Default")
      (node (ref "JP408") (pin "1") (pinfunction "1_1") (pintype "passive"))
    )
    (net (code "162") (name "unconnected-(JP409-Pad1)") (class "Default")
      (node (ref "JP409") (pin "1") (pinfunction "1_1") (pintype "passive"))
    )
    (net (code "163") (name "unconnected-(JP410-Pad1)") (class "Default")
      (node (ref "JP410") (pin "1") (pinfunction "1_1") (pintype "passive"))
    )
    (net (code "164") (name "unconnected-(JP411-Pad1)") (class "Default")
      (node (ref "JP411") (pin "1") (pinfunction "1_1") (pintype "passive"))
    )
    (net (code "165") (name "unconnected-(JP412-Pad1)") (class "Default")
      (node (ref "JP412") (pin "1") (pinfunction "1_1") (pintype "passive"))
    )
    (net (code "166") (name "unconnected-(JP413-Pad1)") (class "Default")
      (node (ref "JP413") (pin "1") (pinfunction "1_1") (pintype "passive"))
    )
    (net (code "167") (name "unconnected-(JP414-Pad1)") (class "Default")
      (node (ref "JP414") (pin "1") (pinfunction "1_1") (pintype "passive"))
    )
    (net (code "168") (name "unconnected-(JP415-Pad1)") (class "Default")
      (node (ref "JP415") (pin "1") (pinfunction "1_1") (pintype "passive"))
    )
    (net (code "169") (name "unconnected-(JP416-Pad1)") (class "Default")
      (node (ref "JP416") (pin "1") (pinfunction "1_1") (pintype "passive"))
    )
    (net (code "170") (name "unconnected-(JP417-Pad1)") (class "Default")
      (node (ref "JP417") (pin "1") (pinfunction "1_1") (pintype "passive"))
    )
    (net (code "171") (name "unconnected-(JP418-Pad1)") (class "Default")
      (node (ref "JP418") (pin "1") (pinfunction "1_1") (pintype "passive"))
    )
    (net (code "172") (name "unconnected-(JP419-Pad1)") (class "Default")
      (node (ref "JP419") (pin "1") (pinfunction "1_1") (pintype "passive"))
    )
    (net (code "173") (name "unconnected-(JP420-Pad1)") (class "Default")
      (node (ref "JP420") (pin "1") (pinfunction "1_1") (pintype "passive"))
    )
    (net (code "174") (name "unconnected-(JP421-Pad1)") (class "Default")
      (node (ref "JP421") (pin "1") (pinfunction "1_1") (pintype "passive"))
    )
    (net (code "175") (name "unconnected-(JP422-Pad1)") (class "Default")
      (node (ref "JP422") (pin "1") (pinfunction "1_1") (pintype "passive"))
    )
    (net (code "176") (name "unconnected-(JP423-Pad1)") (class "Default")
      (node (ref "JP423") (pin "1") (pinfunction "1_1") (pintype "passive"))
    )
    (net (code "177") (name "unconnected-(JP424-Pad1)") (class "Default")
      (node (ref "JP424") (pin "1") (pinfunction "1_1") (pintype "passive"))
    )
    (net (code "178") (name "unconnected-(JP425-Pad1)") (class "Default")
      (node (ref "JP425") (pin "1") (pinfunction "1_1") (pintype "passive"))
    )
    (net (code "179") (name "unconnected-(JP426-Pad1)") (class "Default")
      (node (ref "JP426") (pin "1") (pinfunction "1_1") (pintype "passive"))
    )
    (net (code "180") (name "unconnected-(JP427-Pad1)") (class "Default")
      (node (ref "JP427") (pin "1") (pinfunction "1_1") (pintype "passive"))
    )
    (net (code "181") (name "unconnected-(JP428-Pad1)") (class "Default")
      (node (ref "JP428") (pin "1") (pinfunction "1_1") (pintype "passive"))
    )
    (net (code "182") (name "unconnected-(JP429-Pad1)") (class "Default")
      (node (ref "JP429") (pin "1") (pinfunction "1_1") (pintype "passive"))
    )
    (net (code "183") (name "unconnected-(JP430-Pad1)") (class "Default")
      (node (ref "JP430") (pin "1") (pinfunction "1_1") (pintype "passive"))
    )
    (net (code "184") (name "unconnected-(JP431-Pad1)") (class "Default")
      (node (ref "JP431") (pin "1") (pinfunction "1_1") (pintype "passive"))
    )
    (net (code "185") (name "unconnected-(JP432-Pad1)") (class "Default")
      (node (ref "JP432") (pin "1") (pinfunction "1_1") (pintype "passive"))
    )
    (net (code "186") (name "unconnected-(JP433-Pad1)") (class "Default")
      (node (ref "JP433") (pin "1") (pinfunction "1_1") (pintype "passive"))
    )
    (net (code "187") (name "unconnected-(JP434-Pad1)") (class "Default")
      (node (ref "JP434") (pin "1") (pinfunction "1_1") (pintype "passive"))
    )
    (net (code "188") (name "unconnected-(JP435-Pad1)") (class "Default")
      (node (ref "JP435") (pin "1") (pinfunction "1_1") (pintype "passive"))
    )
    (net (code "189") (name "unconnected-(JP436-Pad1)") (class "Default")
      (node (ref "JP436") (pin "1") (pinfunction "1_1") (pintype "passive"))
    )
    (net (code "190") (name "unconnected-(JP437-Pad1)") (class "Default")
      (node (ref "JP437") (pin "1") (pinfunction "1_1") (pintype "passive"))
    )
    (net (code "191") (name "unconnected-(JP438-Pad1)") (class "Default")
      (node (ref "JP438") (pin "1") (pinfunction "1_1") (pintype "passive"))
    )
    (net (code "192") (name "unconnected-(JP439-Pad1)") (class "Default")
      (node (ref "JP439") (pin "1") (pinfunction "1_1") (pintype "passive"))
    )
    (net (code "193") (name "unconnected-(JP440-Pad1)") (class "Default")
      (node (ref "JP440") (pin "1") (pinfunction "1_1") (pintype "passive"))
    )
    (net (code "194") (name "unconnected-(JP441-Pad1)") (class "Default")
      (node (ref "JP441") (pin "1") (pinfunction "1_1") (pintype "passive"))
    )
    (net (code "195") (name "unconnected-(JP442-Pad1)") (class "Default")
      (node (ref "JP442") (pin "1") (pinfunction "1_1") (pintype "passive"))
    )
    (net (code "196") (name "unconnected-(JP443-Pad1)") (class "Default")
      (node (ref "JP443") (pin "1") (pinfunction "1_1") (pintype "passive"))
    )
    (net (code "197") (name "unconnected-(JP444-Pad1)") (class "Default")
      (node (ref "JP444") (pin "1") (pinfunction "1_1") (pintype "passive"))
    )
    (net (code "198") (name "unconnected-(JP445-Pad1)") (class "Default")
      (node (ref "JP445") (pin "1") (pinfunction "1_1") (pintype "passive"))
    )
    (net (code "199") (name "unconnected-(JP446-Pad1)") (class "Default")
      (node (ref "JP446") (pin "1") (pinfunction "1_1") (pintype "passive"))
    )
    (net (code "200") (name "unconnected-(JP447-Pad1)") (class "Default")
      (node (ref "JP447") (pin "1") (pinfunction "1_1") (pintype "passive"))
    )
    (net (code "201") (name "unconnected-(JP448-Pad1)") (class "Default")
      (node (ref "JP448") (pin "1") (pinfunction "1_1") (pintype "passive"))
    )
    (net (code "202") (name "unconnected-(JP449-Pad1)") (class "Default")
      (node (ref "JP449") (pin "1") (pinfunction "1_1") (pintype "passive"))
    )
    (net (code "203") (name "unconnected-(JP450-Pad1)") (class "Default")
      (node (ref "JP450") (pin "1") (pinfunction "1_1") (pintype "passive"))
    )
    (net (code "204") (name "unconnected-(JP451-Pad1)") (class "Default")
      (node (ref "JP451") (pin "1") (pinfunction "1_1") (pintype "passive"))
    )
    (net (code "205") (name "unconnected-(JP452-Pad1)") (class "Default")
      (node (ref "JP452") (pin "1") (pinfunction "1_1") (pintype "passive"))
    )
    (net (code "206") (name "unconnected-(JP453-Pad1)") (class "Default")
      (node (ref "JP453") (pin "1") (pinfunction "1_1") (pintype "passive"))
    )
    (net (code "207") (name "unconnected-(JP454-Pad1)") (class "Default")
      (node (ref "JP454") (pin "1") (pinfunction "1_1") (pintype "passive"))
    )
    (net (code "208") (name "unconnected-(JP455-Pad1)") (class "Default")
      (node (ref "JP455") (pin "1") (pinfunction "1_1") (pintype "passive"))
    )
    (net (code "209") (name "unconnected-(JP456-Pad1)") (class "Default")
      (node (ref "JP456") (pin "1") (pinfunction "1_1") (pintype "passive"))
    )
    (net (code "210") (name "unconnected-(JP457-Pad1)") (class "Default")
      (node (ref "JP457") (pin "1") (pinfunction "1_1") (pintype "passive"))
    )
    (net (code "211") (name "unconnected-(JP458-Pad1)") (class "Default")
      (node (ref "JP458") (pin "1") (pinfunction "1_1") (pintype "passive"))
    )
    (net (code "212") (name "unconnected-(JP459-Pad1)") (class "Default")
      (node (ref "JP459") (pin "1") (pinfunction "1_1") (pintype "passive"))
    )
    (net (code "213") (name "unconnected-(JP460-Pad1)") (class "Default")
      (node (ref "JP460") (pin "1") (pinfunction "1_1") (pintype "passive"))
    )
    (net (code "214") (name "unconnected-(JP461-Pad1)") (class "Default")
      (node (ref "JP461") (pin "1") (pinfunction "1_1") (pintype "passive"))
    )
    (net (code "215") (name "unconnected-(JP462-Pad1)") (class "Default")
      (node (ref "JP462") (pin "1") (pinfunction "1_1") (pintype "passive"))
    )
    (net (code "216") (name "unconnected-(JP463-Pad1)") (class "Default")
      (node (ref "JP463") (pin "1") (pinfunction "1_1") (pintype "passive"))
    )
    (net (code "217") (name "unconnected-(JP464-Pad1)") (class "Default")
      (node (ref "JP464") (pin "1") (pinfunction "1_1") (pintype "passive"))
    )
    (net (code "218") (name "unconnected-(JP465-Pad1)") (class "Default")
      (node (ref "JP465") (pin "1") (pinfunction "1_1") (pintype "passive"))
    )
    (net (code "219") (name "unconnected-(JP466-Pad1)") (class "Default")
      (node (ref "JP466") (pin "1") (pinfunction "1_1") (pintype "passive"))
    )
    (net (code "220") (name "unconnected-(JP467-Pad1)") (class "Default")
      (node (ref "JP467") (pin "1") (pinfunction "1_1") (pintype "passive"))
    )
    (net (code "221") (name "unconnected-(JP468-Pad1)") (class "Default")
      (node (ref "JP468") (pin "1") (pinfunction "1_1") (pintype "passive"))
    )
    (net (code "222") (name "unconnected-(JP469-Pad1)") (class "Default")
      (node (ref "JP469") (pin "1") (pinfunction "1_1") (pintype "passive"))
    )
    (net (code "223") (name "unconnected-(JP470-Pad1)") (class "Default")
      (node (ref "JP470") (pin "1") (pinfunction "1_1") (pintype "passive"))
    )
    (net (code "224") (name "unconnected-(JP471-Pad1)") (class "Default")
      (node (ref "JP471") (pin "1") (pinfunction "1_1") (pintype "passive"))
    )
    (net (code "225") (name "unconnected-(JP472-Pad1)") (class "Default")
      (node (ref "JP472") (pin "1") (pinfunction "1_1") (pintype "passive"))
    )
    (net (code "226") (name "unconnected-(JP473-Pad1)") (class "Default")
      (node (ref "JP473") (pin "1") (pinfunction "1_1") (pintype "passive"))
    )
    (net (code "227") (name "unconnected-(JP474-Pad1)") (class "Default")
      (node (ref "JP474") (pin "1") (pinfunction "1_1") (pintype "passive"))
    )
    (net (code "228") (name "unconnected-(JP475-Pad1)") (class "Default")
      (node (ref "JP475") (pin "1") (pinfunction "1_1") (pintype "passive"))
    )
    (net (code "229") (name "unconnected-(JP476-Pad1)") (class "Default")
      (node (ref "JP476") (pin "1") (pinfunction "1_1") (pintype "passive"))
    )
    (net (code "230") (name "unconnected-(JP477-Pad1)") (class "Default")
      (node (ref "JP477") (pin "1") (pinfunction "1_1") (pintype "passive"))
    )
    (net (code "231") (name "unconnected-(JP478-Pad1)") (class "Default")
      (node (ref "JP478") (pin "1") (pinfunction "1_1") (pintype "passive"))
    )
    (net (code "232") (name "unconnected-(JP479-Pad1)") (class "Default")
      (node (ref "JP479") (pin "1") (pinfunction "1_1") (pintype "passive"))
    )
    (net (code "233") (name "unconnected-(JP480-Pad1)") (class "Default")
      (node (ref "JP480") (pin "1") (pinfunction "1_1") (pintype "passive"))
    )
    (net (code "234") (name "unconnected-(JP481-Pad1)") (class "Default")
      (node (ref "JP481") (pin "1") (pinfunction "1_1") (pintype "passive"))
    )
    (net (code "235") (name "unconnected-(JP482-Pad1)") (class "Default")
      (node (ref "JP482") (pin "1") (pinfunction "1_1") (pintype "passive"))
    )
    (net (code "236") (name "unconnected-(JP483-Pad1)") (class "Default")
      (node (ref "JP483") (pin "1") (pinfunction "1_1") (pintype "passive"))
    )
    (net (code "237") (name "unconnected-(JP484-Pad1)") (class "Default")
      (node (ref "JP484") (pin "1") (pinfunction "1_1") (pintype "passive"))
    )
    (net (code "238") (name "unconnected-(JP485-Pad1)") (class "Default")
      (node (ref "JP485") (pin "1") (pinfunction "1_1") (pintype "passive"))
    )
    (net (code "239") (name "unconnected-(JP486-Pad1)") (class "Default")
      (node (ref "JP486") (pin "1") (pinfunction "1_1") (pintype "passive"))
    )
    (net (code "240") (name "unconnected-(JP487-Pad1)") (class "Default")
      (node (ref "JP487") (pin "1") (pinfunction "1_1") (pintype "passive"))
    )
    (net (code "241") (name "unconnected-(JP488-Pad1)") (class "Default")
      (node (ref "JP488") (pin "1") (pinfunction "1_1") (pintype "passive"))
    )
    (net (code "242") (name "unconnected-(JP489-Pad1)") (class "Default")
      (node (ref "JP489") (pin "1") (pinfunction "1_1") (pintype "passive"))
    )
    (net (code "243") (name "unconnected-(JP490-Pad1)") (class "Default")
      (node (ref "JP490") (pin "1") (pinfunction "1_1") (pintype "passive"))
    )
    (net (code "244") (name "unconnected-(JP491-Pad1)") (class "Default")
      (node (ref "JP491") (pin "1") (pinfunction "1_1") (pintype "passive"))
    )
    (net (code "245") (name "unconnected-(JP492-Pad1)") (class "Default")
      (node (ref "JP492") (pin "1") (pinfunction "1_1") (pintype "passive"))
    )
    (net (code "246") (name "unconnected-(JP493-Pad1)") (class "Default")
      (node (ref "JP493") (pin "1") (pinfunction "1_1") (pintype "passive"))
    )
    (net (code "247") (name "unconnected-(JP494-Pad1)") (class "Default")
      (node (ref "JP494") (pin "1") (pinfunction "1_1") (pintype "passive"))
    )
    (net (code "248") (name "unconnected-(JP495-Pad1)") (class "Default")
      (node (ref "JP495") (pin "1") (pinfunction "1_1") (pintype "passive"))
    )
    (net (code "249") (name "unconnected-(JP496-Pad1)") (class "Default")
      (node (ref "JP496") (pin "1") (pinfunction "1_1") (pintype "passive"))
    )
    (net (code "250") (name "unconnected-(JP497-Pad1)") (class "Default")
      (node (ref "JP497") (pin "1") (pinfunction "1_1") (pintype "passive"))
    )
    (net (code "251") (name "unconnected-(JP498-Pad1)") (class "Default")
      (node (ref "JP498") (pin "1") (pinfunction "1_1") (pintype "passive"))
    )
    (net (code "252") (name "unconnected-(JP499-Pad1)") (class "Default")
      (node (ref "JP499") (pin "1") (pinfunction "1_1") (pintype "passive"))
    )
    (net (code "253") (name "unconnected-(JP500-Pad1)") (class "Default")
      (node (ref "JP500") (pin "1") (pinfunction "1_1") (pintype "passive"))
    )
    (net (code "254") (name "unconnected-(JP501-Pad1)") (class "Default")
      (node (ref "JP501") (pin "1") (pinfunction "1_1") (pintype "passive"))
    )
    (net (code "255") (name "unconnected-(JP502-Pad1)") (class "Default")
      (node (ref "JP502") (pin "1") (pinfunction "1_1") (pintype "passive"))
    )
    (net (code "256") (name "unconnected-(JP503-Pad1)") (class "Default")
      (node (ref "JP503") (pin "1") (pinfunction "1_1") (pintype "passive"))
    )
    (net (code "257") (name "unconnected-(JP504-Pad1)") (class "Default")
      (node (ref "JP504") (pin "1") (pinfunction "1_1") (pintype "passive"))
    )
    (net (code "258") (name "unconnected-(JP505-Pad1)") (class "Default")
      (node (ref "JP505") (pin "1") (pinfunction "1_1") (pintype "passive"))
    )
    (net (code "259") (name "unconnected-(JP506-Pad1)") (class "Default")
      (node (ref "JP506") (pin "1") (pinfunction "1_1") (pintype "passive"))
    )
    (net (code "260") (name "unconnected-(JP507-Pad1)") (class "Default")
      (node (ref "JP507") (pin "1") (pinfunction "1_1") (pintype "passive"))
    )
    (net (code "261") (name "unconnected-(JP508-Pad1)") (class "Default")
      (node (ref "JP508") (pin "1") (pinfunction "1_1") (pintype "passive"))
    )
    (net (code "262") (name "unconnected-(JP509-Pad1)") (class "Default")
      (node (ref "JP509") (pin "1") (pinfunction "1_1") (pintype "passive"))
    )
    (net (code "263") (name "unconnected-(JP510-Pad1)") (class "Default")
      (node (ref "JP510") (pin "1") (pinfunction "1_1") (pintype "passive"))
    )
    (net (code "264") (name "unconnected-(JP511-Pad1)") (class "Default")
      (node (ref "JP511") (pin "1") (pinfunction "1_1") (pintype "passive"))
    )
    (net (code "265") (name "unconnected-(JP512-Pad1)") (class "Default")
      (node (ref "JP512") (pin "1") (pinfunction "1_1") (pintype "passive"))
    )
    (net (code "266") (name "unconnected-(JP513-Pad1)") (class "Default")
      (node (ref "JP513") (pin "1") (pinfunction "1_1") (pintype "passive"))
    )
    (net (code "267") (name "unconnected-(JP514-Pad1)") (class "Default")
      (node (ref "JP514") (pin "1") (pinfunction "1_1") (pintype "passive"))
    )
    (net (code "268") (name "unconnected-(JP515-Pad1)") (class "Default")
      (node (ref "JP515") (pin "1") (pinfunction "1_1") (pintype "passive"))
    )
    (net (code "269") (name "unconnected-(JP516-Pad1)") (class "Default")
      (node (ref "JP516") (pin "1") (pinfunction "1_1") (pintype "passive"))
    )
    (net (code "270") (name "unconnected-(JP517-Pad1)") (class "Default")
      (node (ref "JP517") (pin "1") (pinfunction "1_1") (pintype "passive"))
    )
    (net (code "271") (name "unconnected-(JP518-Pad1)") (class "Default")
      (node (ref "JP518") (pin "1") (pinfunction "1_1") (pintype "passive"))
    )
    (net (code "272") (name "unconnected-(JP519-Pad1)") (class "Default")
      (node (ref "JP519") (pin "1") (pinfunction "1_1") (pintype "passive"))
    )
    (net (code "273") (name "unconnected-(JP520-Pad1)") (class "Default")
      (node (ref "JP520") (pin "1") (pinfunction "1_1") (pintype "passive"))
    )
    (net (code "274") (name "unconnected-(JP521-Pad1)") (class "Default")
      (node (ref "JP521") (pin "1") (pinfunction "1_1") (pintype "passive"))
    )
    (net (code "275") (name "unconnected-(JP522-Pad1)") (class "Default")
      (node (ref "JP522") (pin "1") (pinfunction "1_1") (pintype "passive"))
    )
    (net (code "276") (name "unconnected-(JP523-Pad1)") (class "Default")
      (node (ref "JP523") (pin "1") (pinfunction "1_1") (pintype "passive"))
    )
    (net (code "277") (name "unconnected-(JP524-Pad1)") (class "Default")
      (node (ref "JP524") (pin "1") (pinfunction "1_1") (pintype "passive"))
    )
    (net (code "278") (name "unconnected-(JP525-Pad1)") (class "Default")
      (node (ref "JP525") (pin "1") (pinfunction "1_1") (pintype "passive"))
    )
    (net (code "279") (name "unconnected-(JP526-Pad1)") (class "Default")
      (node (ref "JP526") (pin "1") (pinfunction "1_1") (pintype "passive"))
    )
    (net (code "280") (name "unconnected-(JP527-Pad1)") (class "Default")
      (node (ref "JP527") (pin "1") (pinfunction "1_1") (pintype "passive"))
    )
    (net (code "281") (name "unconnected-(JP528-Pad1)") (class "Default")
      (node (ref "JP528") (pin "1") (pinfunction "1_1") (pintype "passive"))
    )
    (net (code "282") (name "unconnected-(JP529-Pad1)") (class "Default")
      (node (ref "JP529") (pin "1") (pinfunction "1_1") (pintype "passive"))
    )
    (net (code "283") (name "unconnected-(JP530-Pad1)") (class "Default")
      (node (ref "JP530") (pin "1") (pinfunction "1_1") (pintype "passive"))
    )
    (net (code "284") (name "unconnected-(JP531-Pad1)") (class "Default")
      (node (ref "JP531") (pin "1") (pinfunction "1_1") (pintype "passive"))
    )
    (net (code "285") (name "unconnected-(JP532-Pad1)") (class "Default")
      (node (ref "JP532") (pin "1") (pinfunction "1_1") (pintype "passive"))
    )
    (net (code "286") (name "unconnected-(JP533-Pad1)") (class "Default")
      (node (ref "JP533") (pin "1") (pinfunction "1_1") (pintype "passive"))
    )
    (net (code "287") (name "unconnected-(JP534-Pad1)") (class "Default")
      (node (ref "JP534") (pin "1") (pinfunction "1_1") (pintype "passive"))
    )
    (net (code "288") (name "unconnected-(JP535-Pad1)") (class "Default")
      (node (ref "JP535") (pin "1") (pinfunction "1_1") (pintype "passive"))
    )
    (net (code "289") (name "unconnected-(JP536-Pad1)") (class "Default")
      (node (ref "JP536") (pin "1") (pinfunction "1_1") (pintype "passive"))
    )
    (net (code "290") (name "unconnected-(JP537-Pad1)") (class "Default")
      (node (ref "JP537") (pin "1") (pinfunction "1_1") (pintype "passive"))
    )
    (net (code "291") (name "unconnected-(JP538-Pad1)") (class "Default")
      (node (ref "JP538") (pin "1") (pinfunction "1_1") (pintype "passive"))
    )
    (net (code "292") (name "unconnected-(JP539-Pad1)") (class "Default")
      (node (ref "JP539") (pin "1") (pinfunction "1_1") (pintype "passive"))
    )
    (net (code "293") (name "unconnected-(JP540-Pad1)") (class "Default")
      (node (ref "JP540") (pin "1") (pinfunction "1_1") (pintype "passive"))
    )
    (net (code "294") (name "unconnected-(JP541-Pad1)") (class "Default")
      (node (ref "JP541") (pin "1") (pinfunction "1_1") (pintype "passive"))
    )
    (net (code "295") (name "unconnected-(JP542-Pad1)") (class "Default")
      (node (ref "JP542") (pin "1") (pinfunction "1_1") (pintype "passive"))
    )
    (net (code "296") (name "unconnected-(JP543-Pad1)") (class "Default")
      (node (ref "JP543") (pin "1") (pinfunction "1_1") (pintype "passive"))
    )
    (net (code "297") (name "unconnected-(JP544-Pad1)") (class "Default")
      (node (ref "JP544") (pin "1") (pinfunction "1_1") (pintype "passive"))
    )
    (net (code "298") (name "unconnected-(JP545-Pad1)") (class "Default")
      (node (ref "JP545") (pin "1") (pinfunction "1_1") (pintype "passive"))
    )
    (net (code "299") (name "unconnected-(JP546-Pad1)") (class "Default")
      (node (ref "JP546") (pin "1") (pinfunction "1_1") (pintype "passive"))
    )
    (net (code "300") (name "unconnected-(JP547-Pad1)") (class "Default")
      (node (ref "JP547") (pin "1") (pinfunction "1_1") (pintype "passive"))
    )
    (net (code "301") (name "unconnected-(JP548-Pad1)") (class "Default")
      (node (ref "JP548") (pin "1") (pinfunction "1_1") (pintype "passive"))
    )
    (net (code "302") (name "unconnected-(JP549-Pad1)") (class "Default")
      (node (ref "JP549") (pin "1") (pinfunction "1_1") (pintype "passive"))
    )
    (net (code "303") (name "unconnected-(JP550-Pad1)") (class "Default")
      (node (ref "JP550") (pin "1") (pinfunction "1_1") (pintype "passive"))
    )
    (net (code "304") (name "unconnected-(JP551-Pad1)") (class "Default")
      (node (ref "JP551") (pin "1") (pinfunction "1_1") (pintype "passive"))
    )
    (net (code "305") (name "unconnected-(JP552-Pad1)") (class "Default")
      (node (ref "JP552") (pin "1") (pinfunction "1_1") (pintype "passive"))
    )
    (net (code "306") (name "unconnected-(JP553-Pad1)") (class "Default")
      (node (ref "JP553") (pin "1") (pinfunction "1_1") (pintype "passive"))
    )
    (net (code "307") (name "unconnected-(JP554-Pad1)") (class "Default")
      (node (ref "JP554") (pin "1") (pinfunction "1_1") (pintype "passive"))
    )
    (net (code "308") (name "unconnected-(JP555-Pad1)") (class "Default")
      (node (ref "JP555") (pin "1") (pinfunction "1_1") (pintype "passive"))
    )
    (net (code "309") (name "unconnected-(JP556-Pad1)") (class "Default")
      (node (ref "JP556") (pin "1") (pinfunction "1_1") (pintype "passive"))
    )
    (net (code "310") (name "unconnected-(JP557-Pad1)") (class "Default")
      (node (ref "JP557") (pin "1") (pinfunction "1_1") (pintype "passive"))
    )
    (net (code "311") (name "unconnected-(JP558-Pad1)") (class "Default")
      (node (ref "JP558") (pin "1") (pinfunction "1_1") (pintype "passive"))
    )
    (net (code "312") (name "unconnected-(JP559-Pad1)") (class "Default")
      (node (ref "JP559") (pin "1") (pinfunction "1_1") (pintype "passive"))
    )
    (net (code "313") (name "unconnected-(JP560-Pad1)") (class "Default")
      (node (ref "JP560") (pin "1") (pinfunction "1_1") (pintype "passive"))
    )
    (net (code "314") (name "unconnected-(JP561-Pad1)") (class "Default")
      (node (ref "JP561") (pin "1") (pinfunction "1_1") (pintype "passive"))
    )
    (net (code "315") (name "unconnected-(JP562-Pad1)") (class "Default")
      (node (ref "JP562") (pin "1") (pinfunction "1_1") (pintype "passive"))
    )
    (net (code "316") (name "unconnected-(JP563-Pad1)") (class "Default")
      (node (ref "JP563") (pin "1") (pinfunction "1_1") (pintype "passive"))
    )
    (net (code "317") (name "unconnected-(JP564-Pad1)") (class "Default")
      (node (ref "JP564") (pin "1") (pinfunction "1_1") (pintype "passive"))
    )
    (net (code "318") (name "unconnected-(JP565-Pad1)") (class "Default")
      (node (ref "JP565") (pin "1") (pinfunction "1_1") (pintype "passive"))
    )
    (net (code "319") (name "unconnected-(JP566-Pad1)") (class "Default")
      (node (ref "JP566") (pin "1") (pinfunction "1_1") (pintype "passive"))
    )
    (net (code "320") (name "unconnected-(JP567-Pad1)") (class "Default")
      (node (ref "JP567") (pin "1") (pinfunction "1_1") (pintype "passive"))
    )
    (net (code "321") (name "unconnected-(JP568-Pad1)") (class "Default")
      (node (ref "JP568") (pin "1") (pinfunction "1_1") (pintype "passive"))
    )
    (net (code "322") (name "unconnected-(JP569-Pad1)") (class "Default")
      (node (ref "JP569") (pin "1") (pinfunction "1_1") (pintype "passive"))
    )
    (net (code "323") (name "unconnected-(JP570-Pad1)") (class "Default")
      (node (ref "JP570") (pin "1") (pinfunction "1_1") (pintype "passive"))
    )
    (net (code "324") (name "unconnected-(JP571-Pad1)") (class "Default")
      (node (ref "JP571") (pin "1") (pinfunction "1_1") (pintype "passive"))
    )
    (net (code "325") (name "unconnected-(JP572-Pad1)") (class "Default")
      (node (ref "JP572") (pin "1") (pinfunction "1_1") (pintype "passive"))
    )
    (net (code "326") (name "unconnected-(JP573-Pad1)") (class "Default")
      (node (ref "JP573") (pin "1") (pinfunction "1_1") (pintype "passive"))
    )
    (net (code "327") (name "unconnected-(JP574-Pad1)") (class "Default")
      (node (ref "JP574") (pin "1") (pinfunction "1_1") (pintype "passive"))
    )
    (net (code "328") (name "unconnected-(JP575-Pad1)") (class "Default")
      (node (ref "JP575") (pin "1") (pinfunction "1_1") (pintype "passive"))
    )
    (net (code "329") (name "unconnected-(JP576-Pad1)") (class "Default")
      (node (ref "JP576") (pin "1") (pinfunction "1_1") (pintype "passive"))
    )
    (net (code "330") (name "unconnected-(JP577-Pad1)") (class "Default")
      (node (ref "JP577") (pin "1") (pinfunction "1_1") (pintype "passive"))
    )
    (net (code "331") (name "unconnected-(JP578-Pad1)") (class "Default")
      (node (ref "JP578") (pin "1") (pinfunction "1_1") (pintype "passive"))
    )
    (net (code "332") (name "unconnected-(JP579-Pad1)") (class "Default")
      (node (ref "JP579") (pin "1") (pinfunction "1_1") (pintype "passive"))
    )
    (net (code "333") (name "unconnected-(JP580-Pad1)") (class "Default")
      (node (ref "JP580") (pin "1") (pinfunction "1_1") (pintype "passive"))
    )
    (net (code "334") (name "unconnected-(JP581-Pad1)") (class "Default")
      (node (ref "JP581") (pin "1") (pinfunction "1_1") (pintype "passive"))
    )
    (net (code "335") (name "unconnected-(JP582-Pad1)") (class "Default")
      (node (ref "JP582") (pin "1") (pinfunction "1_1") (pintype "passive"))
    )
    (net (code "336") (name "unconnected-(JP583-Pad1)") (class "Default")
      (node (ref "JP583") (pin "1") (pinfunction "1_1") (pintype "passive"))
    )
    (net (code "337") (name "unconnected-(JP584-Pad1)") (class "Default")
      (node (ref "JP584") (pin "1") (pinfunction "1_1") (pintype "passive"))
    )
    (net (code "338") (name "unconnected-(JP585-Pad1)") (class "Default")
      (node (ref "JP585") (pin "1") (pinfunction "1_1") (pintype "passive"))
    )
    (net (code "339") (name "unconnected-(JP586-Pad1)") (class "Default")
      (node (ref "JP586") (pin "1") (pinfunction "1_1") (pintype "passive"))
    )
    (net (code "340") (name "unconnected-(JP587-Pad1)") (class "Default")
      (node (ref "JP587") (pin "1") (pinfunction "1_1") (pintype "passive"))
    )
    (net (code "341") (name "unconnected-(JP588-Pad1)") (class "Default")
      (node (ref "JP588") (pin "1") (pinfunction "1_1") (pintype "passive"))
    )
    (net (code "342") (name "unconnected-(JP589-Pad1)") (class "Default")
      (node (ref "JP589") (pin "1") (pinfunction "1_1") (pintype "passive"))
    )
    (net (code "343") (name "unconnected-(JP590-Pad1)") (class "Default")
      (node (ref "JP590") (pin "1") (pinfunction "1_1") (pintype "passive"))
    )
    (net (code "344") (name "unconnected-(JP591-Pad1)") (class "Default")
      (node (ref "JP591") (pin "1") (pinfunction "1_1") (pintype "passive"))
    )
    (net (code "345") (name "unconnected-(JP592-Pad1)") (class "Default")
      (node (ref "JP592") (pin "1") (pinfunction "1_1") (pintype "passive"))
    )
    (net (code "346") (name "unconnected-(JP593-Pad1)") (class "Default")
      (node (ref "JP593") (pin "1") (pinfunction "1_1") (pintype "passive"))
    )
    (net (code "347") (name "unconnected-(JP594-Pad1)") (class "Default")
      (node (ref "JP594") (pin "1") (pinfunction "1_1") (pintype "passive"))
    )
    (net (code "348") (name "unconnected-(JP595-Pad1)") (class "Default")
      (node (ref "JP595") (pin "1") (pinfunction "1_1") (pintype "passive"))
    )
    (net (code "349") (name "unconnected-(JP596-Pad1)") (class "Default")
      (node (ref "JP596") (pin "1") (pinfunction "1_1") (pintype "passive"))
    )
    (net (code "350") (name "unconnected-(JP597-Pad1)") (class "Default")
      (node (ref "JP597") (pin "1") (pinfunction "1_1") (pintype "passive"))
    )
    (net (code "351") (name "unconnected-(JP598-Pad1)") (class "Default")
      (node (ref "JP598") (pin "1") (pinfunction "1_1") (pintype "passive"))
    )
    (net (code "352") (name "unconnected-(JP599-Pad1)") (class "Default")
      (node (ref "JP599") (pin "1") (pinfunction "1_1") (pintype "passive"))
    )
    (net (code "353") (name "unconnected-(JP600-Pad1)") (class "Default")
      (node (ref "JP600") (pin "1") (pinfunction "1_1") (pintype "passive"))
    )
    (net (code "354") (name "unconnected-(JP601-Pad1)") (class "Default")
      (node (ref "JP601") (pin "1") (pinfunction "1_1") (pintype "passive"))
    )
    (net (code "355") (name "unconnected-(JP602-Pad1)") (class "Default")
      (node (ref "JP602") (pin "1") (pinfunction "1_1") (pintype "passive"))
    )
    (net (code "356") (name "unconnected-(JP603-Pad1)") (class "Default")
      (node (ref "JP603") (pin "1") (pinfunction "1_1") (pintype "passive"))
    )
    (net (code "357") (name "unconnected-(JP604-Pad1)") (class "Default")
      (node (ref "JP604") (pin "1") (pinfunction "1_1") (pintype "passive"))
    )
    (net (code "358") (name "unconnected-(JP605-Pad1)") (class "Default")
      (node (ref "JP605") (pin "1") (pinfunction "1_1") (pintype "passive"))
    )
    (net (code "359") (name "unconnected-(JP606-Pad1)") (class "Default")
      (node (ref "JP606") (pin "1") (pinfunction "1_1") (pintype "passive"))
    )
    (net (code "360") (name "unconnected-(JP607-Pad1)") (class "Default")
      (node (ref "JP607") (pin "1") (pinfunction "1_1") (pintype "passive"))
    )
    (net (code "361") (name "unconnected-(JP608-Pad1)") (class "Default")
      (node (ref "JP608") (pin "1") (pinfunction "1_1") (pintype "passive"))
    )
    (net (code "362") (name "unconnected-(JP609-Pad1)") (class "Default")
      (node (ref "JP609") (pin "1") (pinfunction "1_1") (pintype "passive"))
    )
    (net (code "363") (name "unconnected-(JP610-Pad1)") (class "Default")
      (node (ref "JP610") (pin "1") (pinfunction "1_1") (pintype "passive"))
    )
    (net (code "364") (name "unconnected-(JP611-Pad1)") (class "Default")
      (node (ref "JP611") (pin "1") (pinfunction "1_1") (pintype "passive"))
    )
    (net (code "365") (name "unconnected-(JP612-Pad1)") (class "Default")
      (node (ref "JP612") (pin "1") (pinfunction "1_1") (pintype "passive"))
    )
    (net (code "366") (name "unconnected-(JP613-Pad1)") (class "Default")
      (node (ref "JP613") (pin "1") (pinfunction "1_1") (pintype "passive"))
    )
    (net (code "367") (name "unconnected-(JP614-Pad1)") (class "Default")
      (node (ref "JP614") (pin "1") (pinfunction "1_1") (pintype "passive"))
    )
    (net (code "368") (name "unconnected-(JP615-Pad1)") (class "Default")
      (node (ref "JP615") (pin "1") (pinfunction "1_1") (pintype "passive"))
    )
    (net (code "369") (name "unconnected-(JP616-Pad1)") (class "Default")
      (node (ref "JP616") (pin "1") (pinfunction "1_1") (pintype "passive"))
    )
    (net (code "370") (name "unconnected-(JP617-Pad1)") (class "Default")
      (node (ref "JP617") (pin "1") (pinfunction "1_1") (pintype "passive"))
    )
    (net (code "371") (name "unconnected-(JP618-Pad1)") (class "Default")
      (node (ref "JP618") (pin "1") (pinfunction "1_1") (pintype "passive"))
    )
    (net (code "372") (name "unconnected-(JP619-Pad1)") (class "Default")
      (node (ref "JP619") (pin "1") (pinfunction "1_1") (pintype "passive"))
    )
    (net (code "373") (name "unconnected-(JP620-Pad1)") (class "Default")
      (node (ref "JP620") (pin "1") (pinfunction "1_1") (pintype "passive"))
    )
    (net (code "374") (name "unconnected-(JP621-Pad1)") (class "Default")
      (node (ref "JP621") (pin "1") (pinfunction "1_1") (pintype "passive"))
    )
    (net (code "375") (name "unconnected-(JP622-Pad1)") (class "Default")
      (node (ref "JP622") (pin "1") (pinfunction "1_1") (pintype "passive"))
    )
    (net (code "376") (name "unconnected-(JP623-Pad1)") (class "Default")
      (node (ref "JP623") (pin "1") (pinfunction "1_1") (pintype "passive"))
    )
    (net (code "377") (name "unconnected-(JP624-Pad1)") (class "Default")
      (node (ref "JP624") (pin "1") (pinfunction "1_1") (pintype "passive"))
    )
    (net (code "378") (name "unconnected-(JP625-Pad1)") (class "Default")
      (node (ref "JP625") (pin "1") (pinfunction "1_1") (pintype "passive"))
    )
    (net (code "379") (name "unconnected-(JP626-Pad1)") (class "Default")
      (node (ref "JP626") (pin "1") (pinfunction "1_1") (pintype "passive"))
    )
    (net (code "380") (name "unconnected-(JP627-Pad1)") (class "Default")
      (node (ref "JP627") (pin "1") (pinfunction "1_1") (pintype "passive"))
    )
    (net (code "381") (name "unconnected-(JP628-Pad1)") (class "Default")
      (node (ref "JP628") (pin "1") (pinfunction "1_1") (pintype "passive"))
    )
    (net (code "382") (name "unconnected-(JP629-Pad1)") (class "Default")
      (node (ref "JP629") (pin "1") (pinfunction "1_1") (pintype "passive"))
    )
    (net (code "383") (name "unconnected-(JP630-Pad1)") (class "Default")
      (node (ref "JP630") (pin "1") (pinfunction "1_1") (pintype "passive"))
    )
    (net (code "384") (name "unconnected-(JP631-Pad1)") (class "Default")
      (node (ref "JP631") (pin "1") (pinfunction "1_1") (pintype "passive"))
    )
    (net (code "385") (name "unconnected-(JP632-Pad1)") (class "Default")
      (node (ref "JP632") (pin "1") (pinfunction "1_1") (pintype "passive"))
    )
    (net (code "386") (name "unconnected-(JP633-Pad1)") (class "Default")
      (node (ref "JP633") (pin "1") (pinfunction "1_1") (pintype "passive"))
    )
    (net (code "387") (name "unconnected-(JP634-Pad1)") (class "Default")
      (node (ref "JP634") (pin "1") (pinfunction "1_1") (pintype "passive"))
    )
    (net (code "388") (name "unconnected-(JP635-Pad1)") (class "Default")
      (node (ref "JP635") (pin "1") (pinfunction "1_1") (pintype "passive"))
    )
    (net (code "389") (name "unconnected-(JP636-Pad1)") (class "Default")
      (node (ref "JP636") (pin "1") (pinfunction "1_1") (pintype "passive"))
    )
    (net (code "390") (name "unconnected-(JP637-Pad1)") (class "Default")
      (node (ref "JP637") (pin "1") (pinfunction "1_1") (pintype "passive"))
    )
    (net (code "391") (name "unconnected-(JP638-Pad1)") (class "Default")
      (node (ref "JP638") (pin "1") (pinfunction "1_1") (pintype "passive"))
    )
    (net (code "392") (name "unconnected-(JP639-Pad1)") (class "Default")
      (node (ref "JP639") (pin "1") (pinfunction "1_1") (pintype "passive"))
    )
    (net (code "393") (name "unconnected-(JP640-Pad1)") (class "Default")
      (node (ref "JP640") (pin "1") (pinfunction "1_1") (pintype "passive"))
    )
    (net (code "394") (name "unconnected-(JP641-Pad1)") (class "Default")
      (node (ref "JP641") (pin "1") (pinfunction "1_1") (pintype "passive"))
    )
    (net (code "395") (name "unconnected-(JP642-Pad1)") (class "Default")
      (node (ref "JP642") (pin "1") (pinfunction "1_1") (pintype "passive"))
    )
    (net (code "396") (name "unconnected-(JP643-Pad1)") (class "Default")
      (node (ref "JP643") (pin "1") (pinfunction "1_1") (pintype "passive"))
    )
    (net (code "397") (name "unconnected-(JP644-Pad1)") (class "Default")
      (node (ref "JP644") (pin "1") (pinfunction "1_1") (pintype "passive"))
    )
    (net (code "398") (name "unconnected-(JP645-Pad1)") (class "Default")
      (node (ref "JP645") (pin "1") (pinfunction "1_1") (pintype "passive"))
    )
    (net (code "399") (name "unconnected-(JP646-Pad1)") (class "Default")
      (node (ref "JP646") (pin "1") (pinfunction "1_1") (pintype "passive"))
    )
    (net (code "400") (name "unconnected-(JP647-Pad1)") (class "Default")
      (node (ref "JP647") (pin "1") (pinfunction "1_1") (pintype "passive"))
    )
    (net (code "401") (name "unconnected-(JP648-Pad1)") (class "Default")
      (node (ref "JP648") (pin "1") (pinfunction "1_1") (pintype "passive"))
    )
    (net (code "402") (name "unconnected-(JP649-Pad1)") (class "Default")
      (node (ref "JP649") (pin "1") (pinfunction "1_1") (pintype "passive"))
    )
    (net (code "403") (name "unconnected-(JP650-Pad1)") (class "Default")
      (node (ref "JP650") (pin "1") (pinfunction "1_1") (pintype "passive"))
    )
    (net (code "404") (name "unconnected-(JP651-Pad1)") (class "Default")
      (node (ref "JP651") (pin "1") (pinfunction "1_1") (pintype "passive"))
    )
    (net (code "405") (name "unconnected-(JP652-Pad1)") (class "Default")
      (node (ref "JP652") (pin "1") (pinfunction "1_1") (pintype "passive"))
    )
    (net (code "406") (name "unconnected-(JP653-Pad1)") (class "Default")
      (node (ref "JP653") (pin "1") (pinfunction "1_1") (pintype "passive"))
    )
    (net (code "407") (name "unconnected-(JP654-Pad1)") (class "Default")
      (node (ref "JP654") (pin "1") (pinfunction "1_1") (pintype "passive"))
    )
    (net (code "408") (name "unconnected-(JP655-Pad1)") (class "Default")
      (node (ref "JP655") (pin "1") (pinfunction "1_1") (pintype "passive"))
    )
    (net (code "409") (name "unconnected-(JP656-Pad1)") (class "Default")
      (node (ref "JP656") (pin "1") (pinfunction "1_1") (pintype "passive"))
    )
    (net (code "410") (name "unconnected-(JP657-Pad1)") (class "Default")
      (node (ref "JP657") (pin "1") (pinfunction "1_1") (pintype "passive"))
    )
    (net (code "411") (name "unconnected-(JP658-Pad1)") (class "Default")
      (node (ref "JP658") (pin "1") (pinfunction "1_1") (pintype "passive"))
    )
    (net (code "412") (name "unconnected-(JP659-Pad1)") (class "Default")
      (node (ref "JP659") (pin "1") (pinfunction "1_1") (pintype "passive"))
    )
    (net (code "413") (name "unconnected-(JP660-Pad1)") (class "Default")
      (node (ref "JP660") (pin "1") (pinfunction "1_1") (pintype "passive"))
    )
    (net (code "414") (name "unconnected-(JP661-Pad1)") (class "Default")
      (node (ref "JP661") (pin "1") (pinfunction "1_1") (pintype "passive"))
    )
    (net (code "415") (name "unconnected-(JP662-Pad1)") (class "Default")
      (node (ref "JP662") (pin "1") (pinfunction "1_1") (pintype "passive"))
    )
    (net (code "416") (name "unconnected-(JP663-Pad1)") (class "Default")
      (node (ref "JP663") (pin "1") (pinfunction "1_1") (pintype "passive"))
    )
    (net (code "417") (name "unconnected-(JP664-Pad1)") (class "Default")
      (node (ref "JP664") (pin "1") (pinfunction "1_1") (pintype "passive"))
    )
    (net (code "418") (name "unconnected-(JP665-Pad1)") (class "Default")
      (node (ref "JP665") (pin "1") (pinfunction "1_1") (pintype "passive"))
    )
    (net (code "419") (name "unconnected-(JP666-Pad1)") (class "Default")
      (node (ref "JP666") (pin "1") (pinfunction "1_1") (pintype "passive"))
    )
    (net (code "420") (name "unconnected-(JP667-Pad1)") (class "Default")
      (node (ref "JP667") (pin "1") (pinfunction "1_1") (pintype "passive"))
    )
    (net (code "421") (name "unconnected-(JP668-Pad1)") (class "Default")
      (node (ref "JP668") (pin "1") (pinfunction "1_1") (pintype "passive"))
    )
    (net (code "422") (name "unconnected-(JP669-Pad1)") (class "Default")
      (node (ref "JP669") (pin "1") (pinfunction "1_1") (pintype "passive"))
    )
    (net (code "423") (name "unconnected-(JP670-Pad1)") (class "Default")
      (node (ref "JP670") (pin "1") (pinfunction "1_1") (pintype "passive"))
    )
    (net (code "424") (name "unconnected-(JP671-Pad1)") (class "Default")
      (node (ref "JP671") (pin "1") (pinfunction "1_1") (pintype "passive"))
    )
    (net (code "425") (name "unconnected-(JP672-Pad1)") (class "Default")
      (node (ref "JP672") (pin "1") (pinfunction "1_1") (pintype "passive"))
    )
    (net (code "426") (name "unconnected-(JP673-Pad1)") (class "Default")
      (node (ref "JP673") (pin "1") (pinfunction "1_1") (pintype "passive"))
    )
    (net (code "427") (name "unconnected-(JP674-Pad1)") (class "Default")
      (node (ref "JP674") (pin "1") (pinfunction "1_1") (pintype "passive"))
    )
    (net (code "428") (name "unconnected-(JP675-Pad1)") (class "Default")
      (node (ref "JP675") (pin "1") (pinfunction "1_1") (pintype "passive"))
    )
    (net (code "429") (name "unconnected-(JP676-Pad1)") (class "Default")
      (node (ref "JP676") (pin "1") (pinfunction "1_1") (pintype "passive"))
    )
    (net (code "430") (name "unconnected-(JP677-Pad1)") (class "Default")
      (node (ref "JP677") (pin "1") (pinfunction "1_1") (pintype "passive"))
    )
    (net (code "431") (name "unconnected-(JP678-Pad1)") (class "Default")
      (node (ref "JP678") (pin "1") (pinfunction "1_1") (pintype "passive"))
    )
    (net (code "432") (name "unconnected-(JP679-Pad1)") (class "Default")
      (node (ref "JP679") (pin "1") (pinfunction "1_1") (pintype "passive"))
    )
    (net (code "433") (name "unconnected-(JP680-Pad1)") (class "Default")
      (node (ref "JP680") (pin "1") (pinfunction "1_1") (pintype "passive"))
    )
    (net (code "434") (name "unconnected-(JP681-Pad1)") (class "Default")
      (node (ref "JP681") (pin "1") (pinfunction "1_1") (pintype "passive"))
    )
    (net (code "435") (name "unconnected-(JP682-Pad1)") (class "Default")
      (node (ref "JP682") (pin "1") (pinfunction "1_1") (pintype "passive"))
    )
    (net (code "436") (name "unconnected-(JP683-Pad1)") (class "Default")
      (node (ref "JP683") (pin "1") (pinfunction "1_1") (pintype "passive"))
    )
    (net (code "437") (name "unconnected-(JP684-Pad1)") (class "Default")
      (node (ref "JP684") (pin "1") (pinfunction "1_1") (pintype "passive"))
    )
    (net (code "438") (name "unconnected-(JP685-Pad1)") (class "Default")
      (node (ref "JP685") (pin "1") (pinfunction "1_1") (pintype "passive"))
    )
    (net (code "439") (name "unconnected-(JP686-Pad1)") (class "Default")
      (node (ref "JP686") (pin "1") (pinfunction "1_1") (pintype "passive"))
    )
    (net (code "440") (name "unconnected-(JP687-Pad1)") (class "Default")
      (node (ref "JP687") (pin "1") (pinfunction "1_1") (pintype "passive"))
    )
    (net (code "441") (name "unconnected-(JP688-Pad1)") (class "Default")
      (node (ref "JP688") (pin "1") (pinfunction "1_1") (pintype "passive"))
    )
    (net (code "442") (name "unconnected-(JP689-Pad1)") (class "Default")
      (node (ref "JP689") (pin "1") (pinfunction "1_1") (pintype "passive"))
    )
    (net (code "443") (name "unconnected-(JP690-Pad1)") (class "Default")
      (node (ref "JP690") (pin "1") (pinfunction "1_1") (pintype "passive"))
    )
    (net (code "444") (name "unconnected-(JP691-Pad1)") (class "Default")
      (node (ref "JP691") (pin "1") (pinfunction "1_1") (pintype "passive"))
    )
    (net (code "445") (name "unconnected-(JP692-Pad1)") (class "Default")
      (node (ref "JP692") (pin "1") (pinfunction "1_1") (pintype "passive"))
    )
    (net (code "446") (name "unconnected-(JP693-Pad1)") (class "Default")
      (node (ref "JP693") (pin "1") (pinfunction "1_1") (pintype "passive"))
    )
    (net (code "447") (name "unconnected-(JP694-Pad1)") (class "Default")
      (node (ref "JP694") (pin "1") (pinfunction "1_1") (pintype "passive"))
    )
    (net (code "448") (name "unconnected-(JP695-Pad1)") (class "Default")
      (node (ref "JP695") (pin "1") (pinfunction "1_1") (pintype "passive"))
    )
    (net (code "449") (name "unconnected-(JP696-Pad1)") (class "Default")
      (node (ref "JP696") (pin "1") (pinfunction "1_1") (pintype "passive"))
    )
    (net (code "450") (name "unconnected-(JP697-Pad1)") (class "Default")
      (node (ref "JP697") (pin "1") (pinfunction "1_1") (pintype "passive"))
    )
    (net (code "451") (name "unconnected-(JP698-Pad1)") (class "Default")
      (node (ref "JP698") (pin "1") (pinfunction "1_1") (pintype "passive"))
    )
    (net (code "452") (name "unconnected-(JP699-Pad1)") (class "Default")
      (node (ref "JP699") (pin "1") (pinfunction "1_1") (pintype "passive"))
    )
    (net (code "453") (name "unconnected-(JP700-Pad1)") (class "Default")
      (node (ref "JP700") (pin "1") (pinfunction "1_1") (pintype "passive"))
    )
    (net (code "454") (name "unconnected-(JP701-Pad1)") (class "Default")
      (node (ref "JP701") (pin "1") (pinfunction "1_1") (pintype "passive"))
    )
    (net (code "455") (name "unconnected-(JP702-Pad1)") (class "Default")
      (node (ref "JP702") (pin "1") (pinfunction "1_1") (pintype "passive"))
    )
    (net (code "456") (name "unconnected-(JP703-Pad1)") (class "Default")
      (node (ref "JP703") (pin "1") (pinfunction "1_1") (pintype "passive"))
    )
    (net (code "457") (name "unconnected-(JP704-Pad1)") (class "Default")
      (node (ref "JP704") (pin "1") (pinfunction "1_1") (pintype "passive"))
    )
    (net (code "458") (name "unconnected-(JP705-Pad1)") (class "Default")
      (node (ref "JP705") (pin "1") (pinfunction "1_1") (pintype "passive"))
    )
    (net (code "459") (name "unconnected-(JP706-Pad1)") (class "Default")
      (node (ref "JP706") (pin "1") (pinfunction "1_1") (pintype "passive"))
    )
    (net (code "460") (name "unconnected-(JP707-Pad1)") (class "Default")
      (node (ref "JP707") (pin "1") (pinfunction "1_1") (pintype "passive"))
    )
    (net (code "461") (name "unconnected-(JP708-Pad1)") (class "Default")
      (node (ref "JP708") (pin "1") (pinfunction "1_1") (pintype "passive"))
    )
    (net (code "462") (name "unconnected-(JP709-Pad1)") (class "Default")
      (node (ref "JP709") (pin "1") (pinfunction "1_1") (pintype "passive"))
    )
    (net (code "463") (name "unconnected-(JP710-Pad1)") (class "Default")
      (node (ref "JP710") (pin "1") (pinfunction "1_1") (pintype "passive"))
    )
    (net (code "464") (name "unconnected-(JP711-Pad1)") (class "Default")
      (node (ref "JP711") (pin "1") (pinfunction "1_1") (pintype "passive"))
    )
    (net (code "465") (name "unconnected-(JP712-Pad1)") (class "Default")
      (node (ref "JP712") (pin "1") (pinfunction "1_1") (pintype "passive"))
    )
    (net (code "466") (name "unconnected-(JP713-Pad1)") (class "Default")
      (node (ref "JP713") (pin "1") (pinfunction "1_1") (pintype "passive"))
    )
    (net (code "467") (name "unconnected-(JP714-Pad1)") (class "Default")
      (node (ref "JP714") (pin "1") (pinfunction "1_1") (pintype "passive"))
    )
    (net (code "468") (name "unconnected-(JP715-Pad1)") (class "Default")
      (node (ref "JP715") (pin "1") (pinfunction "1_1") (pintype "passive"))
    )
    (net (code "469") (name "unconnected-(JP716-Pad1)") (class "Default")
      (node (ref "JP716") (pin "1") (pinfunction "1_1") (pintype "passive"))
    )
    (net (code "470") (name "unconnected-(JP717-Pad1)") (class "Default")
      (node (ref "JP717") (pin "1") (pinfunction "1_1") (pintype "passive"))
    )
    (net (code "471") (name "unconnected-(JP718-Pad1)") (class "Default")
      (node (ref "JP718") (pin "1") (pinfunction "1_1") (pintype "passive"))
    )
    (net (code "472") (name "unconnected-(JP719-Pad1)") (class "Default")
      (node (ref "JP719") (pin "1") (pinfunction "1_1") (pintype "passive"))
    )
    (net (code "473") (name "unconnected-(JP720-Pad1)") (class "Default")
      (node (ref "JP720") (pin "1") (pinfunction "1_1") (pintype "passive"))
    )
    (net (code "474") (name "unconnected-(JP721-Pad1)") (class "Default")
      (node (ref "JP721") (pin "1") (pinfunction "1_1") (pintype "passive"))
    )
    (net (code "475") (name "unconnected-(JP722-Pad1)") (class "Default")
      (node (ref "JP722") (pin "1") (pinfunction "1_1") (pintype "passive"))
    )
    (net (code "476") (name "unconnected-(JP741-Pad1)") (class "Default")
      (node (ref "JP741") (pin "1") (pinfunction "1_1") (pintype "passive"))
    )
    (net (code "477") (name "unconnected-(JP785-Pad1)") (class "Default")
      (node (ref "JP785") (pin "1") (pinfunction "1_1") (pintype "passive"))
    )
    (net (code "478") (name "unconnected-(JP786-Pad1)") (class "Default")
      (node (ref "JP786") (pin "1") (pinfunction "1_1") (pintype "passive"))
    )
    (net (code "479") (name "unconnected-(JP787-Pad1)") (class "Default")
      (node (ref "JP787") (pin "1") (pinfunction "1_1") (pintype "passive"))
    )
    (net (code "480") (name "unconnected-(JP791-Pad1)") (class "Default")
      (node (ref "JP791") (pin "1") (pinfunction "1_1") (pintype "passive"))
    )
    (net (code "481") (name "unconnected-(JP792-Pad1)") (class "Default")
      (node (ref "JP792") (pin "1") (pinfunction "1_1") (pintype "passive"))
    )
    (net (code "482") (name "unconnected-(JP793-Pad1)") (class "Default")
      (node (ref "JP793") (pin "1") (pinfunction "1_1") (pintype "passive"))
    )
    (net (code "483") (name "unconnected-(JP794-Pad1)") (class "Default")
      (node (ref "JP794") (pin "1") (pinfunction "1_1") (pintype "passive"))
    )
    (net (code "484") (name "unconnected-(JP843-Pad1)") (class "Default")
      (node (ref "JP843") (pin "1") (pinfunction "1_1") (pintype "passive"))
    )
    (net (code "485") (name "unconnected-(JP844-Pad1)") (class "Default")
      (node (ref "JP844") (pin "1") (pinfunction "1_1") (pintype "passive"))
    )
    (net (code "486") (name "unconnected-(JP845-Pad1)") (class "Default")
      (node (ref "JP845") (pin "1") (pinfunction "1_1") (pintype "passive"))
    )
    (net (code "487") (name "unconnected-(JP846-Pad1)") (class "Default")
      (node (ref "JP846") (pin "1") (pinfunction "1_1") (pintype "passive"))
    )
    (net (code "488") (name "unconnected-(JP847-Pad1)") (class "Default")
      (node (ref "JP847") (pin "1") (pinfunction "1_1") (pintype "passive"))
    )
    (net (code "489") (name "unconnected-(JP848-Pad1)") (class "Default")
      (node (ref "JP848") (pin "1") (pinfunction "1_1") (pintype "passive"))
    )
    (net (code "490") (name "unconnected-(JP849-Pad1)") (class "Default")
      (node (ref "JP849") (pin "1") (pinfunction "1_1") (pintype "passive"))
    )
    (net (code "491") (name "unconnected-(JP850-Pad1)") (class "Default")
      (node (ref "JP850") (pin "1") (pinfunction "1_1") (pintype "passive"))
    )
    (net (code "492") (name "unconnected-(JP851-Pad1)") (class "Default")
      (node (ref "JP851") (pin "1") (pinfunction "1_1") (pintype "passive"))
    )
    (net (code "493") (name "unconnected-(JP852-Pad1)") (class "Default")
      (node (ref "JP852") (pin "1") (pinfunction "1_1") (pintype "passive"))
    )
    (net (code "494") (name "unconnected-(JP853-Pad1)") (class "Default")
      (node (ref "JP853") (pin "1") (pinfunction "1_1") (pintype "passive"))
    )
    (net (code "495") (name "unconnected-(JP854-Pad1)") (class "Default")
      (node (ref "JP854") (pin "1") (pinfunction "1_1") (pintype "passive"))
    )
    (net (code "496") (name "unconnected-(JP855-Pad1)") (class "Default")
      (node (ref "JP855") (pin "1") (pinfunction "1_1") (pintype "passive"))
    )
    (net (code "497") (name "unconnected-(JP856-Pad1)") (class "Default")
      (node (ref "JP856") (pin "1") (pinfunction "1_1") (pintype "passive"))
    )
    (net (code "498") (name "unconnected-(JP857-Pad1)") (class "Default")
      (node (ref "JP857") (pin "1") (pinfunction "1_1") (pintype "passive"))
    )
    (net (code "499") (name "unconnected-(JP858-Pad1)") (class "Default")
      (node (ref "JP858") (pin "1") (pinfunction "1_1") (pintype "passive"))
    )
    (net (code "500") (name "unconnected-(JP859-Pad1)") (class "Default")
      (node (ref "JP859") (pin "1") (pinfunction "1_1") (pintype "passive"))
    )
    (net (code "501") (name "unconnected-(JP860-Pad1)") (class "Default")
      (node (ref "JP860") (pin "1") (pinfunction "1_1") (pintype "passive"))
    )
    (net (code "502") (name "unconnected-(JP861-Pad1)") (class "Default")
      (node (ref "JP861") (pin "1") (pinfunction "1_1") (pintype "passive"))
    )
    (net (code "503") (name "unconnected-(JP862-Pad1)") (class "Default")
      (node (ref "JP862") (pin "1") (pinfunction "1_1") (pintype "passive"))
    )
    (net (code "504") (name "unconnected-(JP863-Pad1)") (class "Default")
      (node (ref "JP863") (pin "1") (pinfunction "1_1") (pintype "passive"))
    )
    (net (code "505") (name "unconnected-(JP864-Pad1)") (class "Default")
      (node (ref "JP864") (pin "1") (pinfunction "1_1") (pintype "passive"))
    )
    (net (code "506") (name "unconnected-(JP865-Pad1)") (class "Default")
      (node (ref "JP865") (pin "1") (pinfunction "1_1") (pintype "passive"))
    )
    (net (code "507") (name "unconnected-(JP866-Pad1)") (class "Default")
      (node (ref "JP866") (pin "1") (pinfunction "1_1") (pintype "passive"))
    )
    (net (code "508") (name "unconnected-(JP867-Pad1)") (class "Default")
      (node (ref "JP867") (pin "1") (pinfunction "1_1") (pintype "passive"))
    )
    (net (code "509") (name "unconnected-(JP868-Pad1)") (class "Default")
      (node (ref "JP868") (pin "1") (pinfunction "1_1") (pintype "passive"))
    )
    (net (code "510") (name "unconnected-(JP869-Pad1)") (class "Default")
      (node (ref "JP869") (pin "1") (pinfunction "1_1") (pintype "passive"))
    )
    (net (code "511") (name "unconnected-(JP870-Pad1)") (class "Default")
      (node (ref "JP870") (pin "1") (pinfunction "1_1") (pintype "passive"))
    )
    (net (code "512") (name "unconnected-(JP871-Pad1)") (class "Default")
      (node (ref "JP871") (pin "1") (pinfunction "1_1") (pintype "passive"))
    )
    (net (code "513") (name "unconnected-(JP872-Pad1)") (class "Default")
      (node (ref "JP872") (pin "1") (pinfunction "1_1") (pintype "passive"))
    )
    (net (code "514") (name "unconnected-(JP873-Pad1)") (class "Default")
      (node (ref "JP873") (pin "1") (pinfunction "1_1") (pintype "passive"))
    )
    (net (code "515") (name "unconnected-(JP874-Pad1)") (class "Default")
      (node (ref "JP874") (pin "1") (pinfunction "1_1") (pintype "passive"))
    )
    (net (code "516") (name "unconnected-(JP875-Pad1)") (class "Default")
      (node (ref "JP875") (pin "1") (pinfunction "1_1") (pintype "passive"))
    )
    (net (code "517") (name "unconnected-(JP876-Pad1)") (class "Default")
      (node (ref "JP876") (pin "1") (pinfunction "1_1") (pintype "passive"))
    )
    (net (code "518") (name "unconnected-(JP877-Pad1)") (class "Default")
      (node (ref "JP877") (pin "1") (pinfunction "1_1") (pintype "passive"))
    )
    (net (code "519") (name "unconnected-(JP878-Pad1)") (class "Default")
      (node (ref "JP878") (pin "1") (pinfunction "1_1") (pintype "passive"))
    )
    (net (code "520") (name "unconnected-(JP879-Pad1)") (class "Default")
      (node (ref "JP879") (pin "1") (pinfunction "1_1") (pintype "passive"))
    )
    (net (code "521") (name "unconnected-(JP880-Pad1)") (class "Default")
      (node (ref "JP880") (pin "1") (pinfunction "1_1") (pintype "passive"))
    )
    (net (code "522") (name "unconnected-(JP881-Pad1)") (class "Default")
      (node (ref "JP881") (pin "1") (pinfunction "1_1") (pintype "passive"))
    )
    (net (code "523") (name "unconnected-(JP882-Pad1)") (class "Default")
      (node (ref "JP882") (pin "1") (pinfunction "1_1") (pintype "passive"))
    )
    (net (code "524") (name "unconnected-(JP883-Pad1)") (class "Default")
      (node (ref "JP883") (pin "1") (pinfunction "1_1") (pintype "passive"))
    )
    (net (code "525") (name "unconnected-(JP884-Pad1)") (class "Default")
      (node (ref "JP884") (pin "1") (pinfunction "1_1") (pintype "passive"))
    )
    (net (code "526") (name "unconnected-(JP885-Pad1)") (class "Default")
      (node (ref "JP885") (pin "1") (pinfunction "1_1") (pintype "passive"))
    )
    (net (code "527") (name "unconnected-(JP886-Pad1)") (class "Default")
      (node (ref "JP886") (pin "1") (pinfunction "1_1") (pintype "passive"))
    )
    (net (code "528") (name "unconnected-(JP887-Pad1)") (class "Default")
      (node (ref "JP887") (pin "1") (pinfunction "1_1") (pintype "passive"))
    )
    (net (code "529") (name "unconnected-(JP888-Pad1)") (class "Default")
      (node (ref "JP888") (pin "1") (pinfunction "1_1") (pintype "passive"))
    )
    (net (code "530") (name "unconnected-(JP889-Pad1)") (class "Default")
      (node (ref "JP889") (pin "1") (pinfunction "1_1") (pintype "passive"))
    )
    (net (code "531") (name "unconnected-(JP890-Pad1)") (class "Default")
      (node (ref "JP890") (pin "1") (pinfunction "1_1") (pintype "passive"))
    )
    (net (code "532") (name "unconnected-(JP891-Pad1)") (class "Default")
      (node (ref "JP891") (pin "1") (pinfunction "1_1") (pintype "passive"))
    )
    (net (code "533") (name "unconnected-(JP892-Pad1)") (class "Default")
      (node (ref "JP892") (pin "1") (pinfunction "1_1") (pintype "passive"))
    )
    (net (code "534") (name "unconnected-(JP893-Pad1)") (class "Default")
      (node (ref "JP893") (pin "1") (pinfunction "1_1") (pintype "passive"))
    )
    (net (code "535") (name "unconnected-(JP894-Pad1)") (class "Default")
      (node (ref "JP894") (pin "1") (pinfunction "1_1") (pintype "passive"))
    )
    (net (code "536") (name "unconnected-(JP895-Pad1)") (class "Default")
      (node (ref "JP895") (pin "1") (pinfunction "1_1") (pintype "passive"))
    )
    (net (code "537") (name "unconnected-(JP896-Pad1)") (class "Default")
      (node (ref "JP896") (pin "1") (pinfunction "1_1") (pintype "passive"))
    )
    (net (code "538") (name "unconnected-(JP897-Pad1)") (class "Default")
      (node (ref "JP897") (pin "1") (pinfunction "1_1") (pintype "passive"))
    )
    (net (code "539") (name "unconnected-(JP898-Pad1)") (class "Default")
      (node (ref "JP898") (pin "1") (pinfunction "1_1") (pintype "passive"))
    )
    (net (code "540") (name "unconnected-(JP899-Pad1)") (class "Default")
      (node (ref "JP899") (pin "1") (pinfunction "1_1") (pintype "passive"))
    )
    (net (code "541") (name "unconnected-(JP900-Pad1)") (class "Default")
      (node (ref "JP900") (pin "1") (pinfunction "1_1") (pintype "passive"))
    )
    (net (code "542") (name "unconnected-(JP901-Pad1)") (class "Default")
      (node (ref "JP901") (pin "1") (pinfunction "1_1") (pintype "passive"))
    )
    (net (code "543") (name "unconnected-(JP902-Pad1)") (class "Default")
      (node (ref "JP902") (pin "1") (pinfunction "1_1") (pintype "passive"))
    )
    (net (code "544") (name "unconnected-(U$1A-1-PadP$1)") (class "Default")
      (node (ref "U$1") (pin "P$1") (pinfunction "1_P$1") (pintype "passive"))
    )
    (net (code "545") (name "unconnected-(U$1B-1-PadP$2)") (class "Default")
      (node (ref "U$1") (pin "P$2") (pinfunction "1_P$2") (pintype "passive"))
    )
    (net (code "546") (name "unconnected-(U$1C-1-PadP$3)") (class "Default")
      (node (ref "U$1") (pin "P$3") (pinfunction "1_P$3") (pintype "passive"))
    )
    (net (code "547") (name "unconnected-(U$1D-1-PadP$4)") (class "Default")
      (node (ref "U$1") (pin "P$4") (pinfunction "1_P$4") (pintype "passive"))
    )
    (net (code "548") (name "unconnected-(U$2A-1-PadP$1)") (class "Default")
      (node (ref "U$2") (pin "P$1") (pinfunction "1_P$1") (pintype "passive"))
    )
    (net (code "549") (name "unconnected-(U$2D-1-PadP$4)") (class "Default")
      (node (ref "U$2") (pin "P$4") (pinfunction "1_P$4") (pintype "passive"))
    )
  )
)
